# senior_board_rev1.net
KiCad netlist of a schematic drawn in Altium Designer
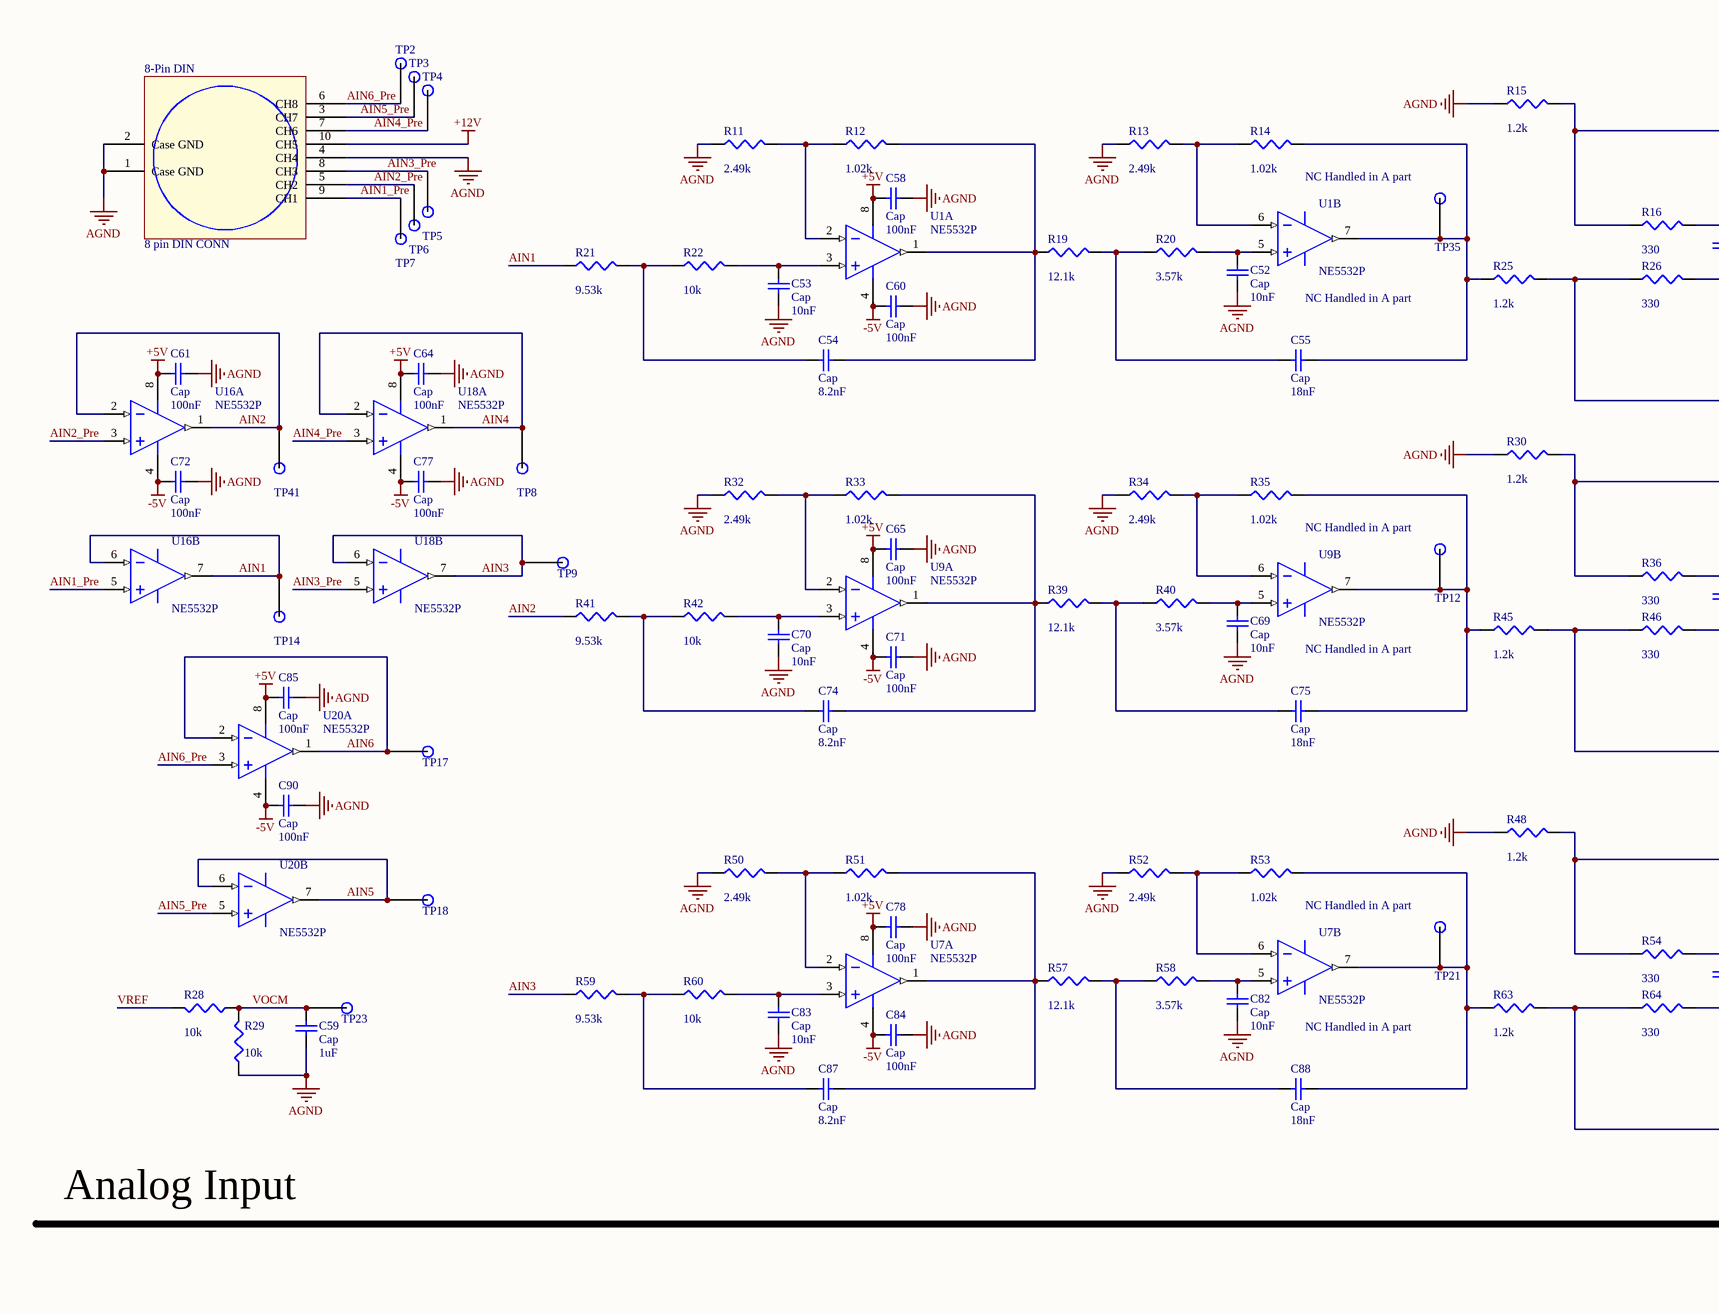
[diagram p0: senior_board_rev1.SchDoc, top left]
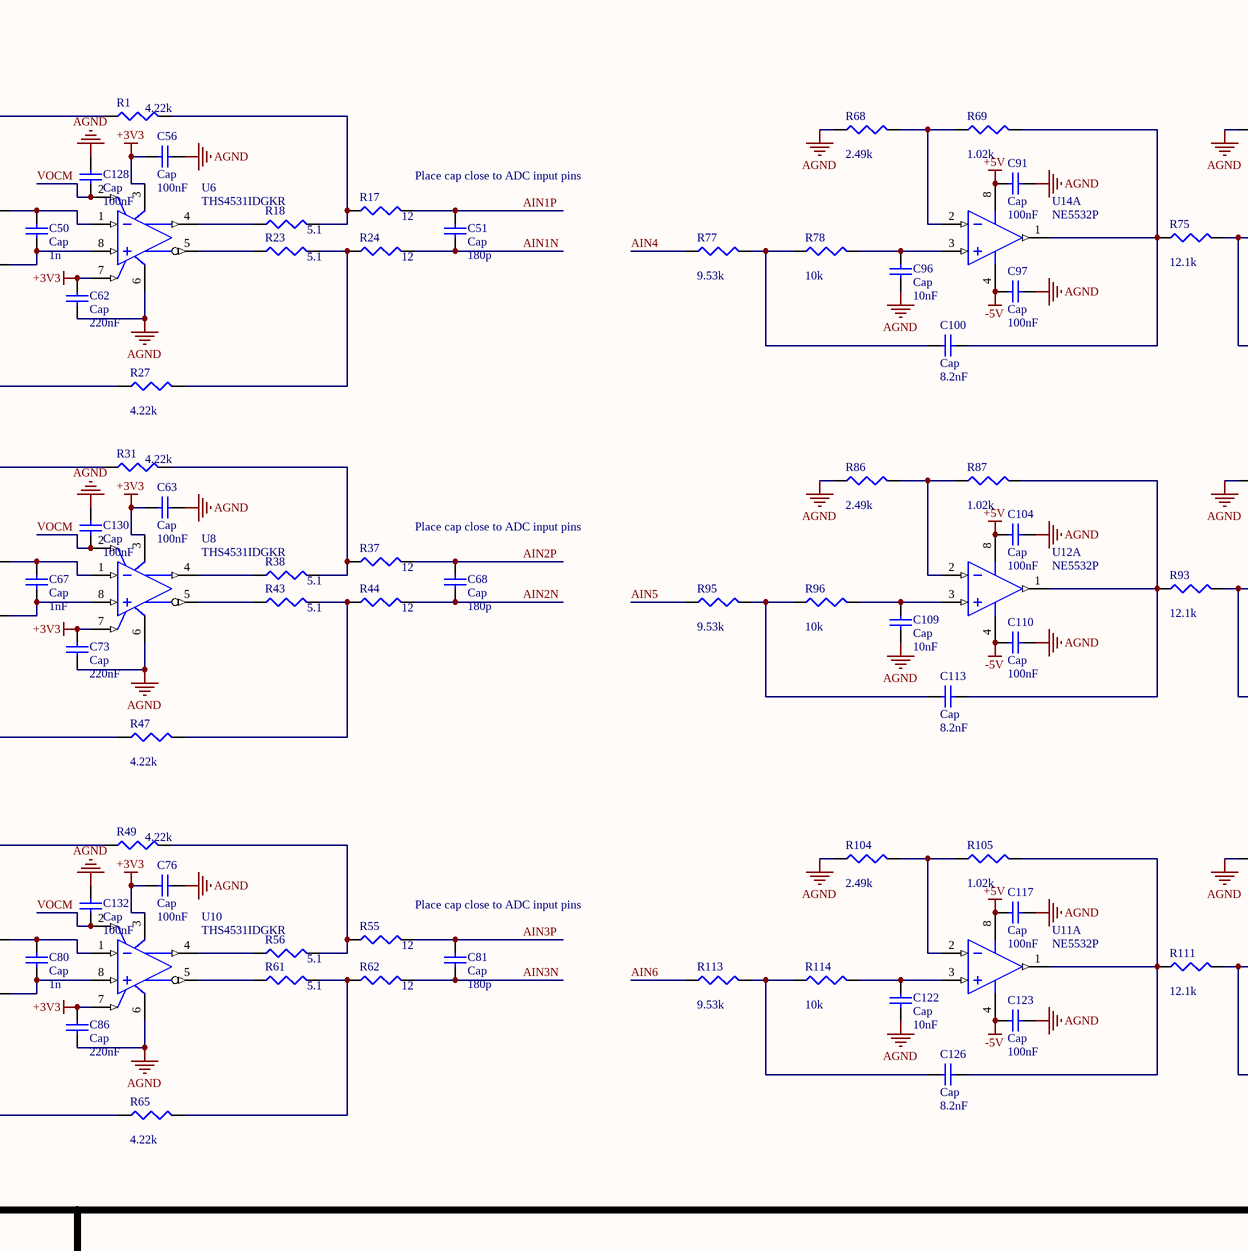
[diagram p1: senior_board_rev1.SchDoc, top middle]
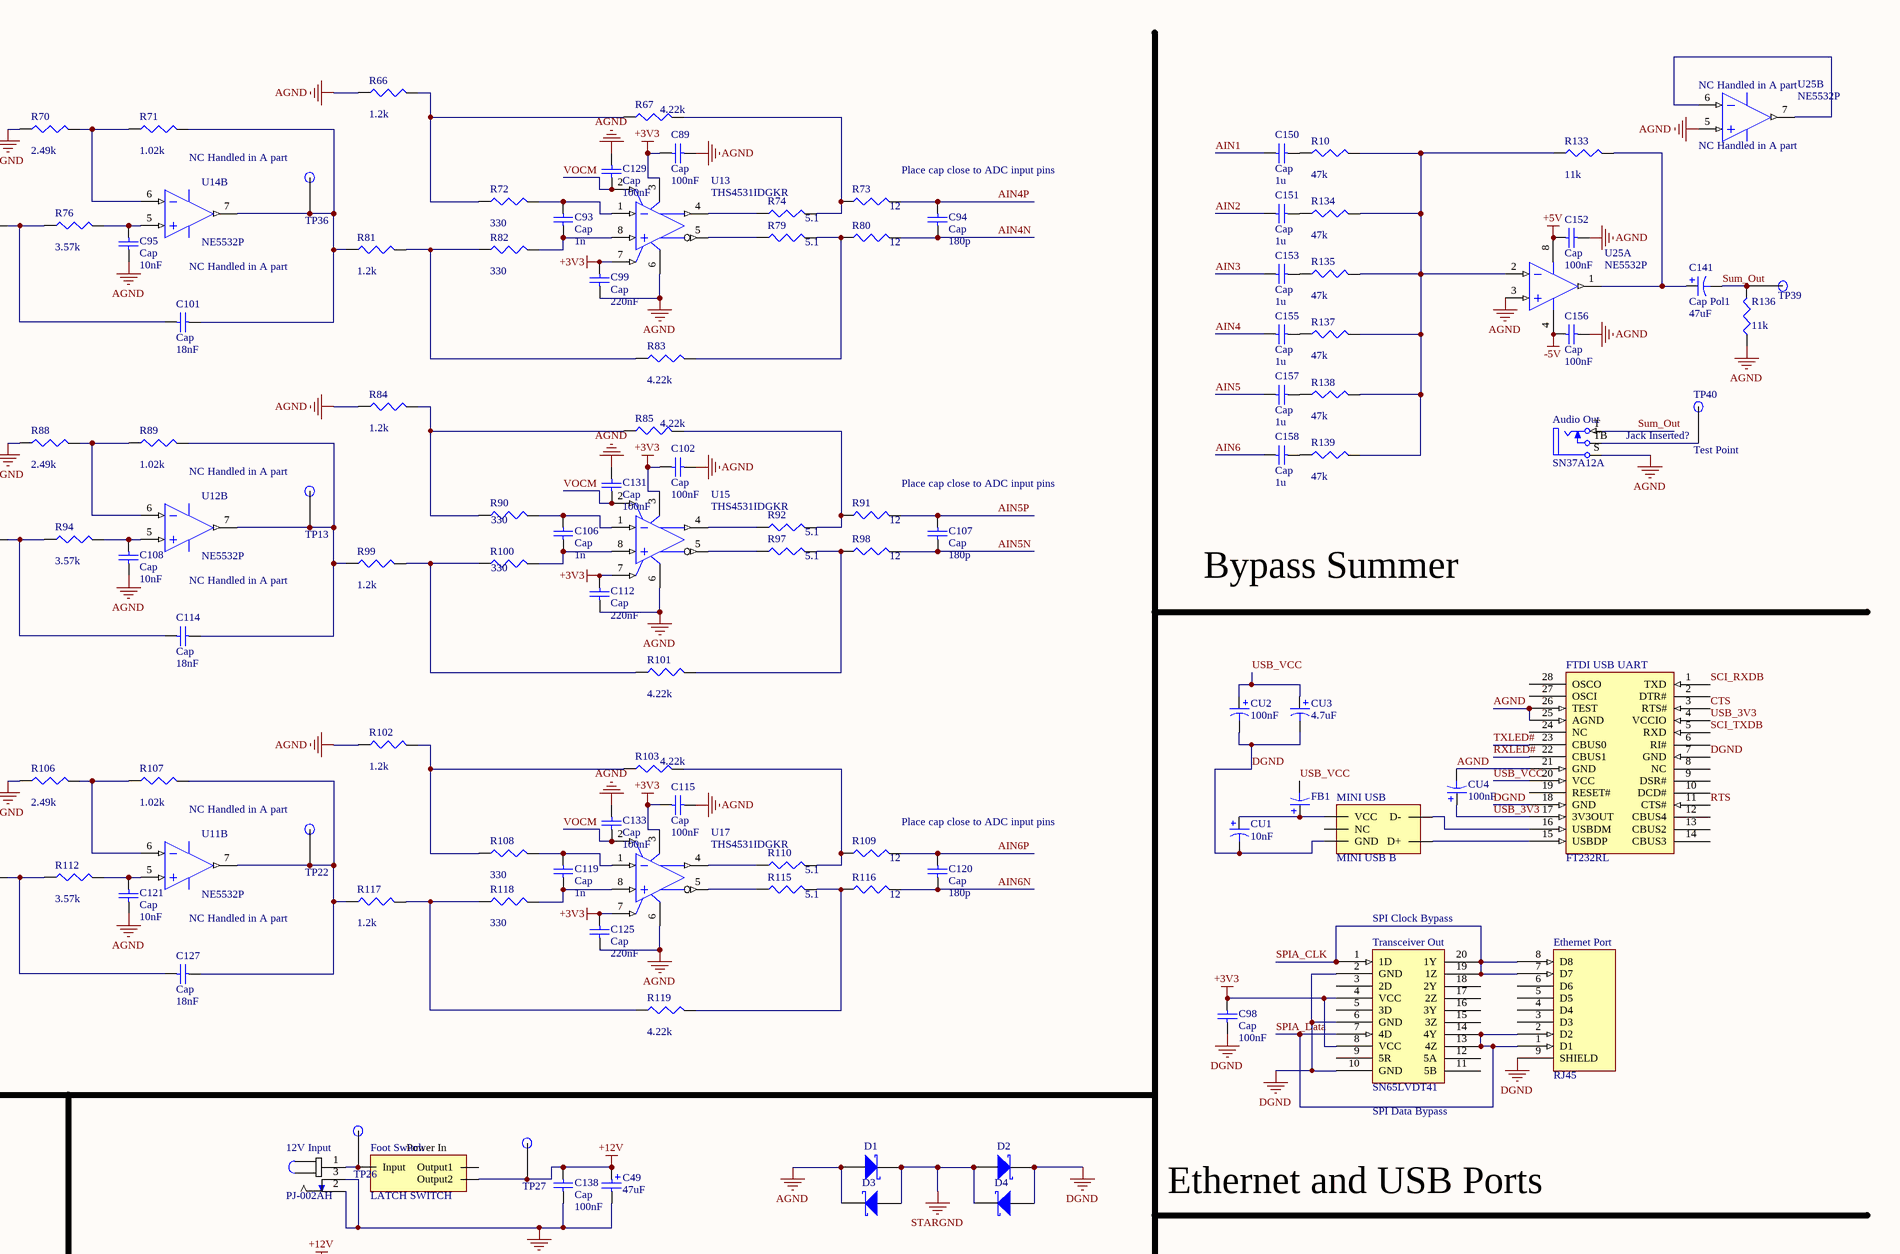
[diagram p2: senior_board_rev1.SchDoc, top right]
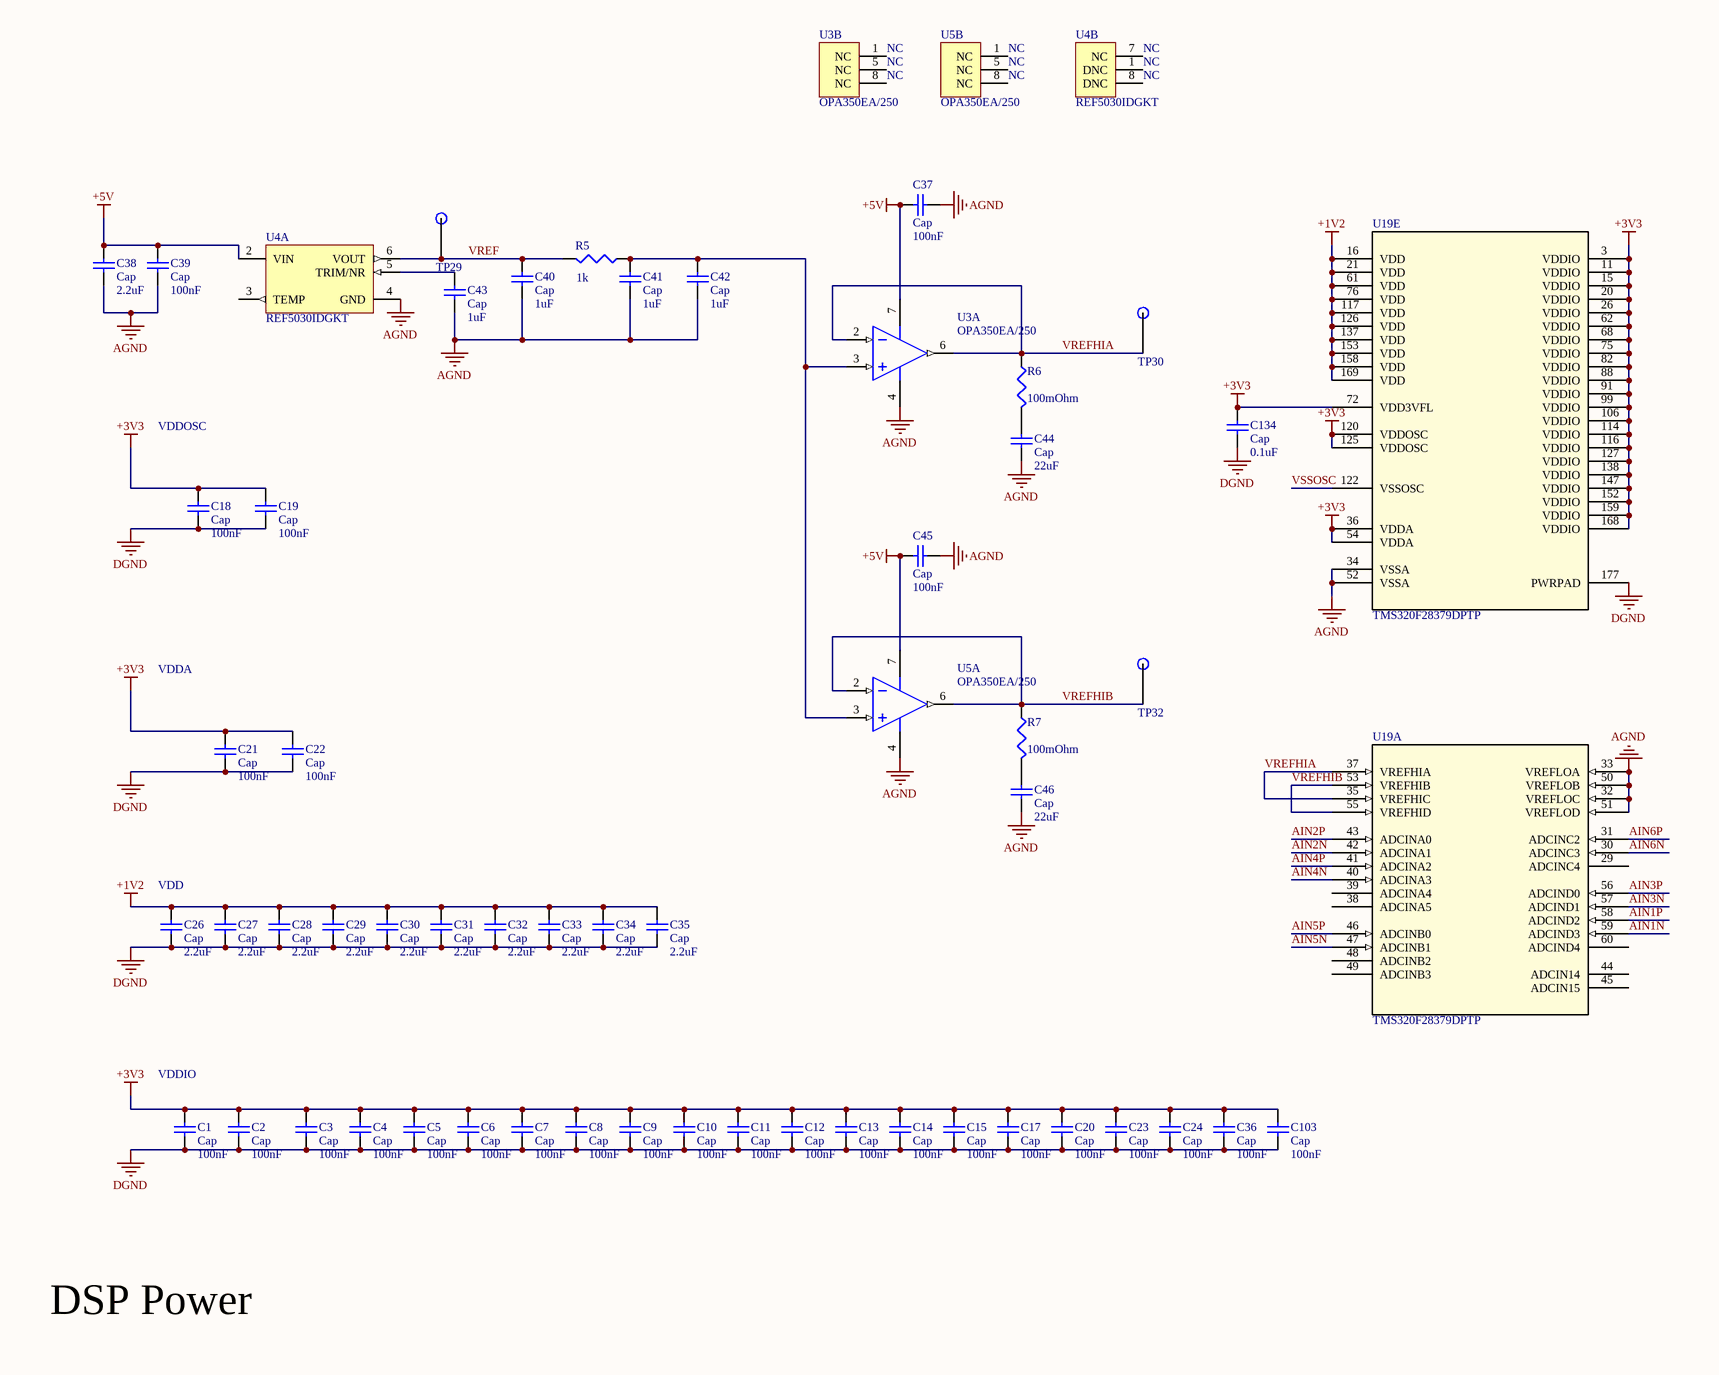
[diagram p3: senior_board_rev1.SchDoc, bottom left]
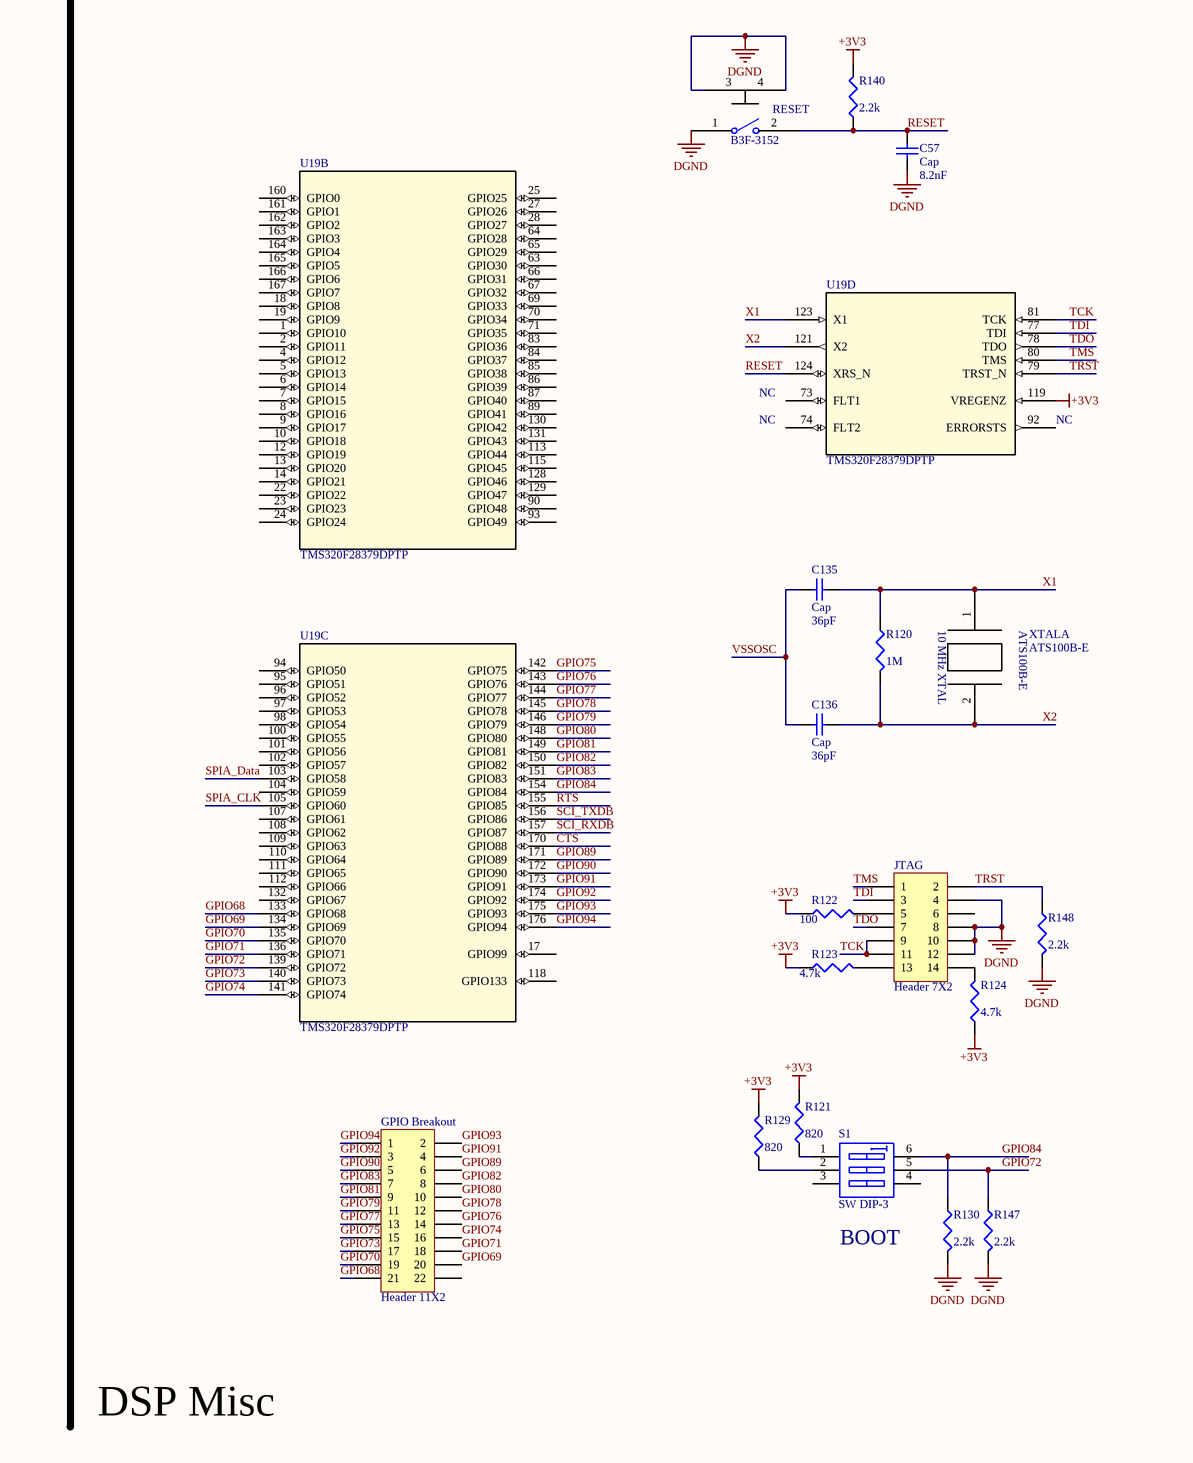
[diagram p4: senior_board_rev1.SchDoc, bottom middle]
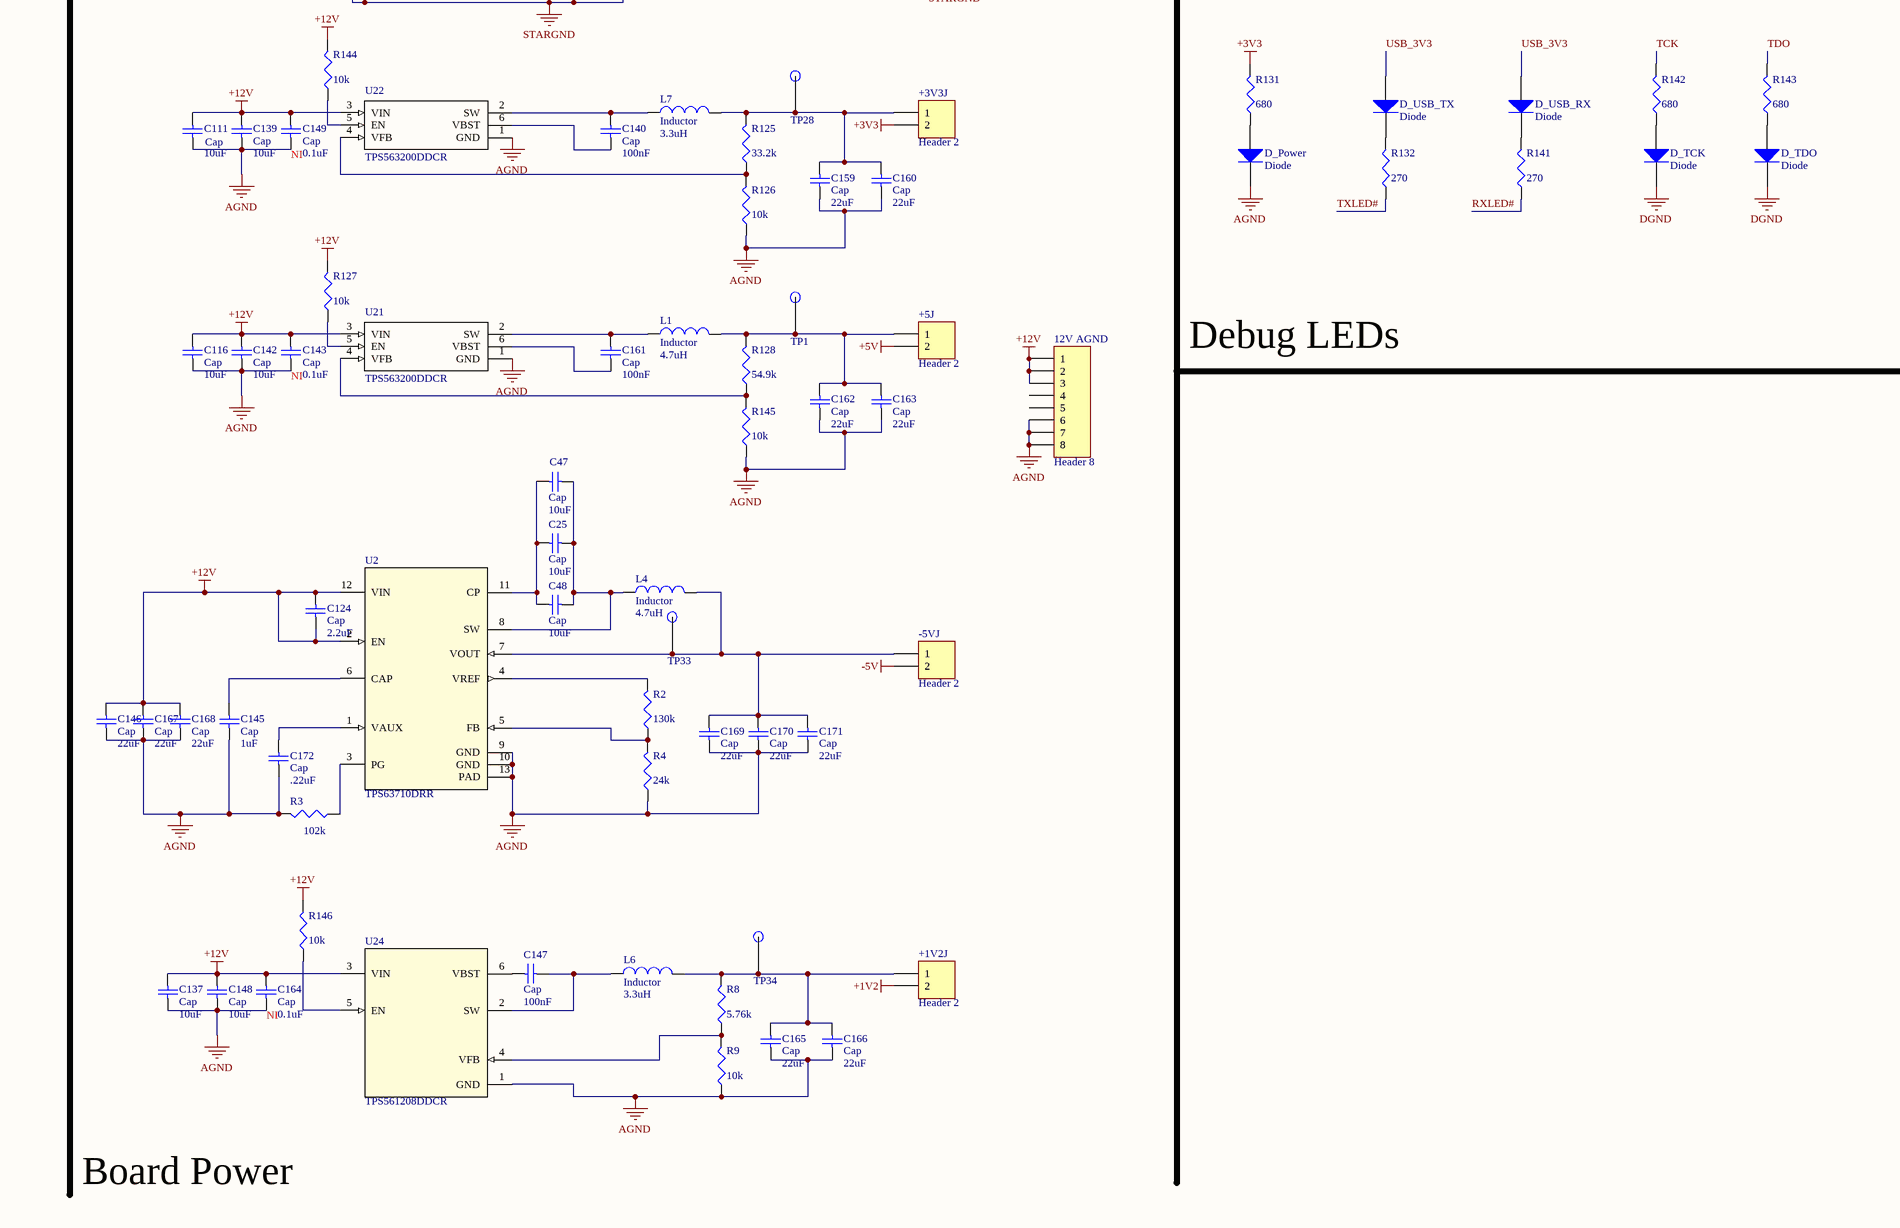
[diagram p5: senior_board_rev1.SchDoc, bottom right]

(export (version "E")
  (design (tool "Eeschema 10.0.6"))
  (components
    (comp (ref "+1V2J")
      (value "Header 2")
      (footprint "HDR1X2")
      (description "Header, 2-Pin")
      (fields (field (name "PUBLISHER") "Altium Limited"))
      (libsource (lib "Miscellaneous Connectors") (part "Header 2"))
    )
    (comp (ref "+3V3J")
      (value "Header 2")
      (footprint "HDR1X2")
      (description "Header, 2-Pin")
      (fields (field (name "PUBLISHER") "Altium Limited"))
      (libsource (lib "Miscellaneous Connectors") (part "Header 2"))
    )
    (comp (ref "+5J")
      (value "Header 2")
      (footprint "HDR1X2")
      (description "Header, 2-Pin")
      (fields (field (name "PUBLISHER") "Altium Limited"))
      (libsource (lib "Miscellaneous Connectors") (part "Header 2"))
    )
    (comp (ref "-5VJ")
      (value "Header 2")
      (footprint "HDR1X2")
      (description "Header, 2-Pin")
      (fields (field (name "PUBLISHER") "Altium Limited"))
      (libsource (lib "Miscellaneous Connectors") (part "Header 2"))
    )
    (comp (ref "8-Pin DIN")
      (value "8 pin DIN CONN")
      (footprint "8 Pin DIN Conn")
      (libsource (lib "Senior_SCH_Lib") (part "8 pin DIN CONN"))
    )
    (comp (ref "12V AGND")
      (value "Header 8")
      (footprint "HDR1X8")
      (description "Header, 8-Pin")
      (fields (field (name "PUBLISHER") "Altium Limited"))
      (libsource (lib "Miscellaneous Connectors") (part "Header 8"))
    )
    (comp (ref "12V Input")
      (value "PJ-002AH")
      (footprint "PJ-002AH")
      (libsource (lib "PJ-002AH") (part "PJ-002AH"))
    )
    (comp (ref "Audio Out")
      (value "SN37A12A")
      (footprint "SN37A12A")
      (libsource (lib "Senior_SCH_Lib") (part "SN37A12A"))
    )
    (comp (ref "C1")
      (value "Cap")
      (footprint "6-0805_N")
      (description "Capacitor")
      (fields (field (name "ALTIUM_VALUE") "100nF") (field (name "PUBLISHER") "Altium Limited"))
      (libsource (lib "Miscellaneous Devices") (part "Cap"))
    )
    (comp (ref "C2")
      (value "Cap")
      (footprint "6-0805_N")
      (description "Capacitor")
      (fields (field (name "ALTIUM_VALUE") "100nF") (field (name "PUBLISHER") "Altium Limited"))
      (libsource (lib "Miscellaneous Devices") (part "Cap"))
    )
    (comp (ref "C3")
      (value "Cap")
      (footprint "6-0805_N")
      (description "Capacitor")
      (fields (field (name "ALTIUM_VALUE") "100nF") (field (name "PUBLISHER") "Altium Limited"))
      (libsource (lib "Miscellaneous Devices") (part "Cap"))
    )
    (comp (ref "C4")
      (value "Cap")
      (footprint "6-0805_N")
      (description "Capacitor")
      (fields (field (name "ALTIUM_VALUE") "100nF") (field (name "PUBLISHER") "Altium Limited"))
      (libsource (lib "Miscellaneous Devices") (part "Cap"))
    )
    (comp (ref "C5")
      (value "Cap")
      (footprint "6-0805_N")
      (description "Capacitor")
      (fields (field (name "ALTIUM_VALUE") "100nF") (field (name "PUBLISHER") "Altium Limited"))
      (libsource (lib "Miscellaneous Devices") (part "Cap"))
    )
    (comp (ref "C6")
      (value "Cap")
      (footprint "6-0805_N")
      (description "Capacitor")
      (fields (field (name "ALTIUM_VALUE") "100nF") (field (name "PUBLISHER") "Altium Limited"))
      (libsource (lib "Miscellaneous Devices") (part "Cap"))
    )
    (comp (ref "C7")
      (value "Cap")
      (footprint "6-0805_N")
      (description "Capacitor")
      (fields (field (name "ALTIUM_VALUE") "100nF") (field (name "PUBLISHER") "Altium Limited"))
      (libsource (lib "Miscellaneous Devices") (part "Cap"))
    )
    (comp (ref "C8")
      (value "Cap")
      (footprint "6-0805_N")
      (description "Capacitor")
      (fields (field (name "ALTIUM_VALUE") "100nF") (field (name "PUBLISHER") "Altium Limited"))
      (libsource (lib "Miscellaneous Devices") (part "Cap"))
    )
    (comp (ref "C9")
      (value "Cap")
      (footprint "6-0805_N")
      (description "Capacitor")
      (fields (field (name "ALTIUM_VALUE") "100nF") (field (name "PUBLISHER") "Altium Limited"))
      (libsource (lib "Miscellaneous Devices") (part "Cap"))
    )
    (comp (ref "C10")
      (value "Cap")
      (footprint "6-0805_N")
      (description "Capacitor")
      (fields (field (name "ALTIUM_VALUE") "100nF") (field (name "PUBLISHER") "Altium Limited"))
      (libsource (lib "Miscellaneous Devices") (part "Cap"))
    )
    (comp (ref "C11")
      (value "Cap")
      (footprint "6-0805_N")
      (description "Capacitor")
      (fields (field (name "ALTIUM_VALUE") "100nF") (field (name "PUBLISHER") "Altium Limited"))
      (libsource (lib "Miscellaneous Devices") (part "Cap"))
    )
    (comp (ref "C12")
      (value "Cap")
      (footprint "6-0805_N")
      (description "Capacitor")
      (fields (field (name "ALTIUM_VALUE") "100nF") (field (name "PUBLISHER") "Altium Limited"))
      (libsource (lib "Miscellaneous Devices") (part "Cap"))
    )
    (comp (ref "C13")
      (value "Cap")
      (footprint "6-0805_N")
      (description "Capacitor")
      (fields (field (name "ALTIUM_VALUE") "100nF") (field (name "PUBLISHER") "Altium Limited"))
      (libsource (lib "Miscellaneous Devices") (part "Cap"))
    )
    (comp (ref "C14")
      (value "Cap")
      (footprint "6-0805_N")
      (description "Capacitor")
      (fields (field (name "ALTIUM_VALUE") "100nF") (field (name "PUBLISHER") "Altium Limited"))
      (libsource (lib "Miscellaneous Devices") (part "Cap"))
    )
    (comp (ref "C15")
      (value "Cap")
      (footprint "6-0805_N")
      (description "Capacitor")
      (fields (field (name "ALTIUM_VALUE") "100nF") (field (name "PUBLISHER") "Altium Limited"))
      (libsource (lib "Miscellaneous Devices") (part "Cap"))
    )
    (comp (ref "C17")
      (value "Cap")
      (footprint "6-0805_N")
      (description "Capacitor")
      (fields (field (name "ALTIUM_VALUE") "100nF") (field (name "PUBLISHER") "Altium Limited"))
      (libsource (lib "Miscellaneous Devices") (part "Cap"))
    )
    (comp (ref "C18")
      (value "Cap")
      (footprint "6-0805_N")
      (description "Capacitor")
      (fields (field (name "ALTIUM_VALUE") "100nF") (field (name "PUBLISHER") "Altium Limited"))
      (libsource (lib "Miscellaneous Devices") (part "Cap"))
    )
    (comp (ref "C19")
      (value "Cap")
      (footprint "6-0805_N")
      (description "Capacitor")
      (fields (field (name "ALTIUM_VALUE") "100nF") (field (name "PUBLISHER") "Altium Limited"))
      (libsource (lib "Miscellaneous Devices") (part "Cap"))
    )
    (comp (ref "C20")
      (value "Cap")
      (footprint "6-0805_N")
      (description "Capacitor")
      (fields (field (name "ALTIUM_VALUE") "100nF") (field (name "PUBLISHER") "Altium Limited"))
      (libsource (lib "Miscellaneous Devices") (part "Cap"))
    )
    (comp (ref "C21")
      (value "Cap")
      (footprint "6-0805_N")
      (description "Capacitor")
      (fields (field (name "ALTIUM_VALUE") "100nF") (field (name "PUBLISHER") "Altium Limited"))
      (libsource (lib "Miscellaneous Devices") (part "Cap"))
    )
    (comp (ref "C22")
      (value "Cap")
      (footprint "6-0805_N")
      (description "Capacitor")
      (fields (field (name "ALTIUM_VALUE") "100nF") (field (name "PUBLISHER") "Altium Limited"))
      (libsource (lib "Miscellaneous Devices") (part "Cap"))
    )
    (comp (ref "C23")
      (value "Cap")
      (footprint "6-0805_N")
      (description "Capacitor")
      (fields (field (name "ALTIUM_VALUE") "100nF") (field (name "PUBLISHER") "Altium Limited"))
      (libsource (lib "Miscellaneous Devices") (part "Cap"))
    )
    (comp (ref "C24")
      (value "Cap")
      (footprint "6-0805_N")
      (description "Capacitor")
      (fields (field (name "ALTIUM_VALUE") "100nF") (field (name "PUBLISHER") "Altium Limited"))
      (libsource (lib "Miscellaneous Devices") (part "Cap"))
    )
    (comp (ref "C25")
      (value "Cap")
      (footprint "6-0805_N")
      (description "Capacitor")
      (fields (field (name "ALTIUM_VALUE") "10uF") (field (name "PUBLISHER") "Altium Limited"))
      (libsource (lib "Miscellaneous Devices") (part "Cap"))
    )
    (comp (ref "C26")
      (value "Cap")
      (footprint "6-0805_N")
      (description "Capacitor")
      (fields (field (name "ALTIUM_VALUE") "2.2uF") (field (name "PUBLISHER") "Altium Limited"))
      (libsource (lib "Miscellaneous Devices") (part "Cap"))
    )
    (comp (ref "C27")
      (value "Cap")
      (footprint "6-0805_N")
      (description "Capacitor")
      (fields (field (name "ALTIUM_VALUE") "2.2uF") (field (name "PUBLISHER") "Altium Limited"))
      (libsource (lib "Miscellaneous Devices") (part "Cap"))
    )
    (comp (ref "C28")
      (value "Cap")
      (footprint "6-0805_N")
      (description "Capacitor")
      (fields (field (name "ALTIUM_VALUE") "2.2uF") (field (name "PUBLISHER") "Altium Limited"))
      (libsource (lib "Miscellaneous Devices") (part "Cap"))
    )
    (comp (ref "C29")
      (value "Cap")
      (footprint "6-0805_N")
      (description "Capacitor")
      (fields (field (name "ALTIUM_VALUE") "2.2uF") (field (name "PUBLISHER") "Altium Limited"))
      (libsource (lib "Miscellaneous Devices") (part "Cap"))
    )
    (comp (ref "C30")
      (value "Cap")
      (footprint "6-0805_N")
      (description "Capacitor")
      (fields (field (name "ALTIUM_VALUE") "2.2uF") (field (name "PUBLISHER") "Altium Limited"))
      (libsource (lib "Miscellaneous Devices") (part "Cap"))
    )
    (comp (ref "C31")
      (value "Cap")
      (footprint "6-0805_N")
      (description "Capacitor")
      (fields (field (name "ALTIUM_VALUE") "2.2uF") (field (name "PUBLISHER") "Altium Limited"))
      (libsource (lib "Miscellaneous Devices") (part "Cap"))
    )
    (comp (ref "C32")
      (value "Cap")
      (footprint "6-0805_N")
      (description "Capacitor")
      (fields (field (name "ALTIUM_VALUE") "2.2uF") (field (name "PUBLISHER") "Altium Limited"))
      (libsource (lib "Miscellaneous Devices") (part "Cap"))
    )
    (comp (ref "C33")
      (value "Cap")
      (footprint "6-0805_N")
      (description "Capacitor")
      (fields (field (name "ALTIUM_VALUE") "2.2uF") (field (name "PUBLISHER") "Altium Limited"))
      (libsource (lib "Miscellaneous Devices") (part "Cap"))
    )
    (comp (ref "C34")
      (value "Cap")
      (footprint "6-0805_N")
      (description "Capacitor")
      (fields (field (name "ALTIUM_VALUE") "2.2uF") (field (name "PUBLISHER") "Altium Limited"))
      (libsource (lib "Miscellaneous Devices") (part "Cap"))
    )
    (comp (ref "C35")
      (value "Cap")
      (footprint "6-0805_N")
      (description "Capacitor")
      (fields (field (name "ALTIUM_VALUE") "2.2uF") (field (name "PUBLISHER") "Altium Limited"))
      (libsource (lib "Miscellaneous Devices") (part "Cap"))
    )
    (comp (ref "C36")
      (value "Cap")
      (footprint "6-0805_N")
      (description "Capacitor")
      (fields (field (name "ALTIUM_VALUE") "100nF") (field (name "PUBLISHER") "Altium Limited"))
      (libsource (lib "Miscellaneous Devices") (part "Cap"))
    )
    (comp (ref "C37")
      (value "Cap")
      (footprint "6-0805_N")
      (description "Capacitor")
      (fields (field (name "ALTIUM_VALUE") "100nF") (field (name "PUBLISHER") "Altium Limited"))
      (libsource (lib "Miscellaneous Devices") (part "Cap"))
    )
    (comp (ref "C38")
      (value "Cap")
      (footprint "6-0805_N")
      (description "Capacitor")
      (fields (field (name "ALTIUM_VALUE") "2.2uF") (field (name "PUBLISHER") "Altium Limited"))
      (libsource (lib "Miscellaneous Devices") (part "Cap"))
    )
    (comp (ref "C39")
      (value "Cap")
      (footprint "6-0805_N")
      (description "Capacitor")
      (fields (field (name "ALTIUM_VALUE") "100nF") (field (name "PUBLISHER") "Altium Limited"))
      (libsource (lib "Miscellaneous Devices") (part "Cap"))
    )
    (comp (ref "C40")
      (value "Cap")
      (footprint "6-0805_N")
      (description "Capacitor")
      (fields (field (name "ALTIUM_VALUE") "1uF") (field (name "PUBLISHER") "Altium Limited"))
      (libsource (lib "Miscellaneous Devices") (part "Cap"))
    )
    (comp (ref "C41")
      (value "Cap")
      (footprint "6-0805_N")
      (description "Capacitor")
      (fields (field (name "ALTIUM_VALUE") "1uF") (field (name "PUBLISHER") "Altium Limited"))
      (libsource (lib "Miscellaneous Devices") (part "Cap"))
    )
    (comp (ref "C42")
      (value "Cap")
      (footprint "6-0805_N")
      (description "Capacitor")
      (fields (field (name "ALTIUM_VALUE") "1uF") (field (name "PUBLISHER") "Altium Limited"))
      (libsource (lib "Miscellaneous Devices") (part "Cap"))
    )
    (comp (ref "C43")
      (value "Cap")
      (footprint "6-0805_N")
      (description "Capacitor")
      (fields (field (name "ALTIUM_VALUE") "1uF") (field (name "PUBLISHER") "Altium Limited"))
      (libsource (lib "Miscellaneous Devices") (part "Cap"))
    )
    (comp (ref "C44")
      (value "Cap")
      (footprint "6-0805_N")
      (description "Capacitor")
      (fields (field (name "ALTIUM_VALUE") "22uF") (field (name "PUBLISHER") "Altium Limited"))
      (libsource (lib "Miscellaneous Devices") (part "Cap"))
    )
    (comp (ref "C45")
      (value "Cap")
      (footprint "6-0805_N")
      (description "Capacitor")
      (fields (field (name "ALTIUM_VALUE") "100nF") (field (name "PUBLISHER") "Altium Limited"))
      (libsource (lib "Miscellaneous Devices") (part "Cap"))
    )
    (comp (ref "C46")
      (value "Cap")
      (footprint "6-0805_N")
      (description "Capacitor")
      (fields (field (name "ALTIUM_VALUE") "22uF") (field (name "PUBLISHER") "Altium Limited"))
      (libsource (lib "Miscellaneous Devices") (part "Cap"))
    )
    (comp (ref "C47")
      (value "Cap")
      (footprint "6-0805_N")
      (description "Capacitor")
      (fields (field (name "ALTIUM_VALUE") "10uF") (field (name "PUBLISHER") "Altium Limited"))
      (libsource (lib "Miscellaneous Devices") (part "Cap"))
    )
    (comp (ref "C48")
      (value "Cap")
      (footprint "6-0805_N")
      (description "Capacitor")
      (fields (field (name "ALTIUM_VALUE") "10uF") (field (name "PUBLISHER") "Altium Limited"))
      (libsource (lib "Miscellaneous Devices") (part "Cap"))
    )
    (comp (ref "C49")
      (value "47uF")
      (footprint "UUQ1C470MCL1GB")
      (description "UUQ1C470MCL1GB")
      (libsource (lib "Senior_SCH_Lib") (part "UUQ1C470MCL1GB"))
    )
    (comp (ref "C50")
      (value "Cap")
      (footprint "6-0805_N")
      (description "Capacitor")
      (fields (field (name "ALTIUM_VALUE") "1n") (field (name "PUBLISHER") "Altium Limited"))
      (libsource (lib "Miscellaneous Devices") (part "Cap"))
    )
    (comp (ref "C51")
      (value "Cap")
      (footprint "6-0805_N")
      (description "Capacitor")
      (fields (field (name "ALTIUM_VALUE") "180p") (field (name "PUBLISHER") "Altium Limited"))
      (libsource (lib "Miscellaneous Devices") (part "Cap"))
    )
    (comp (ref "C52")
      (value "Cap")
      (footprint "6-0805_N")
      (description "Capacitor")
      (fields (field (name "ALTIUM_VALUE") "10nF") (field (name "PUBLISHER") "Altium Limited"))
      (libsource (lib "Miscellaneous Devices") (part "Cap"))
    )
    (comp (ref "C53")
      (value "Cap")
      (footprint "6-0805_N")
      (description "Capacitor")
      (fields (field (name "ALTIUM_VALUE") "10nF") (field (name "PUBLISHER") "Altium Limited"))
      (libsource (lib "Miscellaneous Devices") (part "Cap"))
    )
    (comp (ref "C54")
      (value "Cap")
      (footprint "6-0805_N")
      (description "Capacitor")
      (fields (field (name "ALTIUM_VALUE") "8.2nF") (field (name "PUBLISHER") "Altium Limited"))
      (libsource (lib "Miscellaneous Devices") (part "Cap"))
    )
    (comp (ref "C55")
      (value "Cap")
      (footprint "6-0805_N")
      (description "Capacitor")
      (fields (field (name "ALTIUM_VALUE") "18nF") (field (name "PUBLISHER") "Altium Limited"))
      (libsource (lib "Miscellaneous Devices") (part "Cap"))
    )
    (comp (ref "C56")
      (value "Cap")
      (footprint "6-0805_N")
      (description "Capacitor")
      (fields (field (name "ALTIUM_VALUE") "100nF") (field (name "PUBLISHER") "Altium Limited"))
      (libsource (lib "Miscellaneous Devices") (part "Cap"))
    )
    (comp (ref "C57")
      (value "Cap")
      (footprint "6-0805_N")
      (description "Capacitor")
      (fields (field (name "ALTIUM_VALUE") "8.2nF") (field (name "PUBLISHER") "Altium Limited"))
      (libsource (lib "Miscellaneous Devices") (part "Cap"))
    )
    (comp (ref "C58")
      (value "Cap")
      (footprint "6-0805_N")
      (description "Capacitor")
      (fields (field (name "ALTIUM_VALUE") "100nF") (field (name "PUBLISHER") "Altium Limited"))
      (libsource (lib "Miscellaneous Devices") (part "Cap"))
    )
    (comp (ref "C59")
      (value "Cap")
      (footprint "6-0805_N")
      (description "Capacitor")
      (fields (field (name "ALTIUM_VALUE") "1uF") (field (name "PUBLISHER") "Altium Limited"))
      (libsource (lib "Miscellaneous Devices") (part "Cap"))
    )
    (comp (ref "C60")
      (value "Cap")
      (footprint "6-0805_N")
      (description "Capacitor")
      (fields (field (name "ALTIUM_VALUE") "100nF") (field (name "PUBLISHER") "Altium Limited"))
      (libsource (lib "Miscellaneous Devices") (part "Cap"))
    )
    (comp (ref "C61")
      (value "Cap")
      (footprint "6-0805_N")
      (description "Capacitor")
      (fields (field (name "ALTIUM_VALUE") "100nF") (field (name "PUBLISHER") "Altium Limited"))
      (libsource (lib "Miscellaneous Devices") (part "Cap"))
    )
    (comp (ref "C62")
      (value "Cap")
      (footprint "6-0805_N")
      (description "Capacitor")
      (fields (field (name "ALTIUM_VALUE") "220nF") (field (name "PUBLISHER") "Altium Limited"))
      (libsource (lib "Miscellaneous Devices") (part "Cap"))
    )
    (comp (ref "C63")
      (value "Cap")
      (footprint "6-0805_N")
      (description "Capacitor")
      (fields (field (name "ALTIUM_VALUE") "100nF") (field (name "PUBLISHER") "Altium Limited"))
      (libsource (lib "Miscellaneous Devices") (part "Cap"))
    )
    (comp (ref "C64")
      (value "Cap")
      (footprint "6-0805_N")
      (description "Capacitor")
      (fields (field (name "ALTIUM_VALUE") "100nF") (field (name "PUBLISHER") "Altium Limited"))
      (libsource (lib "Miscellaneous Devices") (part "Cap"))
    )
    (comp (ref "C65")
      (value "Cap")
      (footprint "6-0805_N")
      (description "Capacitor")
      (fields (field (name "ALTIUM_VALUE") "100nF") (field (name "PUBLISHER") "Altium Limited"))
      (libsource (lib "Miscellaneous Devices") (part "Cap"))
    )
    (comp (ref "C67")
      (value "Cap")
      (footprint "6-0805_N")
      (description "Capacitor")
      (fields (field (name "ALTIUM_VALUE") "1nF") (field (name "PUBLISHER") "Altium Limited"))
      (libsource (lib "Miscellaneous Devices") (part "Cap"))
    )
    (comp (ref "C68")
      (value "Cap")
      (footprint "6-0805_N")
      (description "Capacitor")
      (fields (field (name "ALTIUM_VALUE") "180p") (field (name "PUBLISHER") "Altium Limited"))
      (libsource (lib "Miscellaneous Devices") (part "Cap"))
    )
    (comp (ref "C69")
      (value "Cap")
      (footprint "6-0805_N")
      (description "Capacitor")
      (fields (field (name "ALTIUM_VALUE") "10nF") (field (name "PUBLISHER") "Altium Limited"))
      (libsource (lib "Miscellaneous Devices") (part "Cap"))
    )
    (comp (ref "C70")
      (value "Cap")
      (footprint "6-0805_N")
      (description "Capacitor")
      (fields (field (name "ALTIUM_VALUE") "10nF") (field (name "PUBLISHER") "Altium Limited"))
      (libsource (lib "Miscellaneous Devices") (part "Cap"))
    )
    (comp (ref "C71")
      (value "Cap")
      (footprint "6-0805_N")
      (description "Capacitor")
      (fields (field (name "ALTIUM_VALUE") "100nF") (field (name "PUBLISHER") "Altium Limited"))
      (libsource (lib "Miscellaneous Devices") (part "Cap"))
    )
    (comp (ref "C72")
      (value "Cap")
      (footprint "6-0805_N")
      (description "Capacitor")
      (fields (field (name "ALTIUM_VALUE") "100nF") (field (name "PUBLISHER") "Altium Limited"))
      (libsource (lib "Miscellaneous Devices") (part "Cap"))
    )
    (comp (ref "C73")
      (value "Cap")
      (footprint "6-0805_N")
      (description "Capacitor")
      (fields (field (name "ALTIUM_VALUE") "220nF") (field (name "PUBLISHER") "Altium Limited"))
      (libsource (lib "Miscellaneous Devices") (part "Cap"))
    )
    (comp (ref "C74")
      (value "Cap")
      (footprint "6-0805_N")
      (description "Capacitor")
      (fields (field (name "ALTIUM_VALUE") "8.2nF") (field (name "PUBLISHER") "Altium Limited"))
      (libsource (lib "Miscellaneous Devices") (part "Cap"))
    )
    (comp (ref "C75")
      (value "Cap")
      (footprint "6-0805_N")
      (description "Capacitor")
      (fields (field (name "ALTIUM_VALUE") "18nF") (field (name "PUBLISHER") "Altium Limited"))
      (libsource (lib "Miscellaneous Devices") (part "Cap"))
    )
    (comp (ref "C76")
      (value "Cap")
      (footprint "6-0805_N")
      (description "Capacitor")
      (fields (field (name "ALTIUM_VALUE") "100nF") (field (name "PUBLISHER") "Altium Limited"))
      (libsource (lib "Miscellaneous Devices") (part "Cap"))
    )
    (comp (ref "C77")
      (value "Cap")
      (footprint "6-0805_N")
      (description "Capacitor")
      (fields (field (name "ALTIUM_VALUE") "100nF") (field (name "PUBLISHER") "Altium Limited"))
      (libsource (lib "Miscellaneous Devices") (part "Cap"))
    )
    (comp (ref "C78")
      (value "Cap")
      (footprint "6-0805_N")
      (description "Capacitor")
      (fields (field (name "ALTIUM_VALUE") "100nF") (field (name "PUBLISHER") "Altium Limited"))
      (libsource (lib "Miscellaneous Devices") (part "Cap"))
    )
    (comp (ref "C80")
      (value "Cap")
      (footprint "6-0805_N")
      (description "Capacitor")
      (fields (field (name "ALTIUM_VALUE") "1n") (field (name "PUBLISHER") "Altium Limited"))
      (libsource (lib "Miscellaneous Devices") (part "Cap"))
    )
    (comp (ref "C81")
      (value "Cap")
      (footprint "6-0805_N")
      (description "Capacitor")
      (fields (field (name "ALTIUM_VALUE") "180p") (field (name "PUBLISHER") "Altium Limited"))
      (libsource (lib "Miscellaneous Devices") (part "Cap"))
    )
    (comp (ref "C82")
      (value "Cap")
      (footprint "6-0805_N")
      (description "Capacitor")
      (fields (field (name "ALTIUM_VALUE") "10nF") (field (name "PUBLISHER") "Altium Limited"))
      (libsource (lib "Miscellaneous Devices") (part "Cap"))
    )
    (comp (ref "C83")
      (value "Cap")
      (footprint "6-0805_N")
      (description "Capacitor")
      (fields (field (name "ALTIUM_VALUE") "10nF") (field (name "PUBLISHER") "Altium Limited"))
      (libsource (lib "Miscellaneous Devices") (part "Cap"))
    )
    (comp (ref "C84")
      (value "Cap")
      (footprint "6-0805_N")
      (description "Capacitor")
      (fields (field (name "ALTIUM_VALUE") "100nF") (field (name "PUBLISHER") "Altium Limited"))
      (libsource (lib "Miscellaneous Devices") (part "Cap"))
    )
    (comp (ref "C85")
      (value "Cap")
      (footprint "6-0805_N")
      (description "Capacitor")
      (fields (field (name "ALTIUM_VALUE") "100nF") (field (name "PUBLISHER") "Altium Limited"))
      (libsource (lib "Miscellaneous Devices") (part "Cap"))
    )
    (comp (ref "C86")
      (value "Cap")
      (footprint "6-0805_N")
      (description "Capacitor")
      (fields (field (name "ALTIUM_VALUE") "220nF") (field (name "PUBLISHER") "Altium Limited"))
      (libsource (lib "Miscellaneous Devices") (part "Cap"))
    )
    (comp (ref "C87")
      (value "Cap")
      (footprint "6-0805_N")
      (description "Capacitor")
      (fields (field (name "ALTIUM_VALUE") "8.2nF") (field (name "PUBLISHER") "Altium Limited"))
      (libsource (lib "Miscellaneous Devices") (part "Cap"))
    )
    (comp (ref "C88")
      (value "Cap")
      (footprint "6-0805_N")
      (description "Capacitor")
      (fields (field (name "ALTIUM_VALUE") "18nF") (field (name "PUBLISHER") "Altium Limited"))
      (libsource (lib "Miscellaneous Devices") (part "Cap"))
    )
    (comp (ref "C89")
      (value "Cap")
      (footprint "6-0805_N")
      (description "Capacitor")
      (fields (field (name "ALTIUM_VALUE") "100nF") (field (name "PUBLISHER") "Altium Limited"))
      (libsource (lib "Miscellaneous Devices") (part "Cap"))
    )
    (comp (ref "C90")
      (value "Cap")
      (footprint "6-0805_N")
      (description "Capacitor")
      (fields (field (name "ALTIUM_VALUE") "100nF") (field (name "PUBLISHER") "Altium Limited"))
      (libsource (lib "Miscellaneous Devices") (part "Cap"))
    )
    (comp (ref "C91")
      (value "Cap")
      (footprint "6-0805_N")
      (description "Capacitor")
      (fields (field (name "ALTIUM_VALUE") "100nF") (field (name "PUBLISHER") "Altium Limited"))
      (libsource (lib "Miscellaneous Devices") (part "Cap"))
    )
    (comp (ref "C93")
      (value "Cap")
      (footprint "6-0805_N")
      (description "Capacitor")
      (fields (field (name "ALTIUM_VALUE") "1n") (field (name "PUBLISHER") "Altium Limited"))
      (libsource (lib "Miscellaneous Devices") (part "Cap"))
    )
    (comp (ref "C94")
      (value "Cap")
      (footprint "6-0805_N")
      (description "Capacitor")
      (fields (field (name "ALTIUM_VALUE") "180p") (field (name "PUBLISHER") "Altium Limited"))
      (libsource (lib "Miscellaneous Devices") (part "Cap"))
    )
    (comp (ref "C95")
      (value "Cap")
      (footprint "6-0805_N")
      (description "Capacitor")
      (fields (field (name "ALTIUM_VALUE") "10nF") (field (name "PUBLISHER") "Altium Limited"))
      (libsource (lib "Miscellaneous Devices") (part "Cap"))
    )
    (comp (ref "C96")
      (value "Cap")
      (footprint "6-0805_N")
      (description "Capacitor")
      (fields (field (name "ALTIUM_VALUE") "10nF") (field (name "PUBLISHER") "Altium Limited"))
      (libsource (lib "Miscellaneous Devices") (part "Cap"))
    )
    (comp (ref "C97")
      (value "Cap")
      (footprint "6-0805_N")
      (description "Capacitor")
      (fields (field (name "ALTIUM_VALUE") "100nF") (field (name "PUBLISHER") "Altium Limited"))
      (libsource (lib "Miscellaneous Devices") (part "Cap"))
    )
    (comp (ref "C98")
      (value "Cap")
      (footprint "6-0805_N")
      (description "Capacitor")
      (fields (field (name "ALTIUM_VALUE") "100nF") (field (name "PUBLISHER") "Altium Limited"))
      (libsource (lib "Miscellaneous Devices") (part "Cap"))
    )
    (comp (ref "C99")
      (value "Cap")
      (footprint "6-0805_N")
      (description "Capacitor")
      (fields (field (name "ALTIUM_VALUE") "220nF") (field (name "PUBLISHER") "Altium Limited"))
      (libsource (lib "Miscellaneous Devices") (part "Cap"))
    )
    (comp (ref "C100")
      (value "Cap")
      (footprint "6-0805_N")
      (description "Capacitor")
      (fields (field (name "ALTIUM_VALUE") "8.2nF") (field (name "PUBLISHER") "Altium Limited"))
      (libsource (lib "Miscellaneous Devices") (part "Cap"))
    )
    (comp (ref "C101")
      (value "Cap")
      (footprint "6-0805_N")
      (description "Capacitor")
      (fields (field (name "ALTIUM_VALUE") "18nF") (field (name "PUBLISHER") "Altium Limited"))
      (libsource (lib "Miscellaneous Devices") (part "Cap"))
    )
    (comp (ref "C102")
      (value "Cap")
      (footprint "6-0805_N")
      (description "Capacitor")
      (fields (field (name "ALTIUM_VALUE") "100nF") (field (name "PUBLISHER") "Altium Limited"))
      (libsource (lib "Miscellaneous Devices") (part "Cap"))
    )
    (comp (ref "C103")
      (value "Cap")
      (footprint "6-0805_N")
      (description "Capacitor")
      (fields (field (name "ALTIUM_VALUE") "100nF") (field (name "PUBLISHER") "Altium Limited"))
      (libsource (lib "Miscellaneous Devices") (part "Cap"))
    )
    (comp (ref "C104")
      (value "Cap")
      (footprint "6-0805_N")
      (description "Capacitor")
      (fields (field (name "ALTIUM_VALUE") "100nF") (field (name "PUBLISHER") "Altium Limited"))
      (libsource (lib "Miscellaneous Devices") (part "Cap"))
    )
    (comp (ref "C106")
      (value "Cap")
      (footprint "6-0805_N")
      (description "Capacitor")
      (fields (field (name "ALTIUM_VALUE") "1n") (field (name "PUBLISHER") "Altium Limited"))
      (libsource (lib "Miscellaneous Devices") (part "Cap"))
    )
    (comp (ref "C107")
      (value "Cap")
      (footprint "6-0805_N")
      (description "Capacitor")
      (fields (field (name "ALTIUM_VALUE") "180p") (field (name "PUBLISHER") "Altium Limited"))
      (libsource (lib "Miscellaneous Devices") (part "Cap"))
    )
    (comp (ref "C108")
      (value "Cap")
      (footprint "6-0805_N")
      (description "Capacitor")
      (fields (field (name "ALTIUM_VALUE") "10nF") (field (name "PUBLISHER") "Altium Limited"))
      (libsource (lib "Miscellaneous Devices") (part "Cap"))
    )
    (comp (ref "C109")
      (value "Cap")
      (footprint "6-0805_N")
      (description "Capacitor")
      (fields (field (name "ALTIUM_VALUE") "10nF") (field (name "PUBLISHER") "Altium Limited"))
      (libsource (lib "Miscellaneous Devices") (part "Cap"))
    )
    (comp (ref "C110")
      (value "Cap")
      (footprint "6-0805_N")
      (description "Capacitor")
      (fields (field (name "ALTIUM_VALUE") "100nF") (field (name "PUBLISHER") "Altium Limited"))
      (libsource (lib "Miscellaneous Devices") (part "Cap"))
    )
    (comp (ref "C111")
      (value "Cap")
      (footprint "6-0805_N")
      (description "Capacitor")
      (fields (field (name "ALTIUM_VALUE") "10uF") (field (name "PUBLISHER") "Altium Limited"))
      (libsource (lib "Miscellaneous Devices") (part "Cap"))
    )
    (comp (ref "C112")
      (value "Cap")
      (footprint "6-0805_N")
      (description "Capacitor")
      (fields (field (name "ALTIUM_VALUE") "220nF") (field (name "PUBLISHER") "Altium Limited"))
      (libsource (lib "Miscellaneous Devices") (part "Cap"))
    )
    (comp (ref "C113")
      (value "Cap")
      (footprint "6-0805_N")
      (description "Capacitor")
      (fields (field (name "ALTIUM_VALUE") "8.2nF") (field (name "PUBLISHER") "Altium Limited"))
      (libsource (lib "Miscellaneous Devices") (part "Cap"))
    )
    (comp (ref "C114")
      (value "Cap")
      (footprint "6-0805_N")
      (description "Capacitor")
      (fields (field (name "ALTIUM_VALUE") "18nF") (field (name "PUBLISHER") "Altium Limited"))
      (libsource (lib "Miscellaneous Devices") (part "Cap"))
    )
    (comp (ref "C115")
      (value "Cap")
      (footprint "6-0805_N")
      (description "Capacitor")
      (fields (field (name "ALTIUM_VALUE") "100nF") (field (name "PUBLISHER") "Altium Limited"))
      (libsource (lib "Miscellaneous Devices") (part "Cap"))
    )
    (comp (ref "C116")
      (value "Cap")
      (footprint "6-0805_N")
      (description "Capacitor")
      (fields (field (name "ALTIUM_VALUE") "10uF") (field (name "PUBLISHER") "Altium Limited"))
      (libsource (lib "Miscellaneous Devices") (part "Cap"))
    )
    (comp (ref "C117")
      (value "Cap")
      (footprint "6-0805_N")
      (description "Capacitor")
      (fields (field (name "ALTIUM_VALUE") "100nF") (field (name "PUBLISHER") "Altium Limited"))
      (libsource (lib "Miscellaneous Devices") (part "Cap"))
    )
    (comp (ref "C119")
      (value "Cap")
      (footprint "6-0805_N")
      (description "Capacitor")
      (fields (field (name "ALTIUM_VALUE") "1n") (field (name "PUBLISHER") "Altium Limited"))
      (libsource (lib "Miscellaneous Devices") (part "Cap"))
    )
    (comp (ref "C120")
      (value "Cap")
      (footprint "6-0805_N")
      (description "Capacitor")
      (fields (field (name "ALTIUM_VALUE") "180p") (field (name "PUBLISHER") "Altium Limited"))
      (libsource (lib "Miscellaneous Devices") (part "Cap"))
    )
    (comp (ref "C121")
      (value "Cap")
      (footprint "6-0805_N")
      (description "Capacitor")
      (fields (field (name "ALTIUM_VALUE") "10nF") (field (name "PUBLISHER") "Altium Limited"))
      (libsource (lib "Miscellaneous Devices") (part "Cap"))
    )
    (comp (ref "C122")
      (value "Cap")
      (footprint "6-0805_N")
      (description "Capacitor")
      (fields (field (name "ALTIUM_VALUE") "10nF") (field (name "PUBLISHER") "Altium Limited"))
      (libsource (lib "Miscellaneous Devices") (part "Cap"))
    )
    (comp (ref "C123")
      (value "Cap")
      (footprint "6-0805_N")
      (description "Capacitor")
      (fields (field (name "ALTIUM_VALUE") "100nF") (field (name "PUBLISHER") "Altium Limited"))
      (libsource (lib "Miscellaneous Devices") (part "Cap"))
    )
    (comp (ref "C124")
      (value "Cap")
      (footprint "6-0805_N")
      (description "Capacitor")
      (fields (field (name "ALTIUM_VALUE") "2.2uF") (field (name "PUBLISHER") "Altium Limited"))
      (libsource (lib "Miscellaneous Devices") (part "Cap"))
    )
    (comp (ref "C125")
      (value "Cap")
      (footprint "6-0805_N")
      (description "Capacitor")
      (fields (field (name "ALTIUM_VALUE") "220nF") (field (name "PUBLISHER") "Altium Limited"))
      (libsource (lib "Miscellaneous Devices") (part "Cap"))
    )
    (comp (ref "C126")
      (value "Cap")
      (footprint "6-0805_N")
      (description "Capacitor")
      (fields (field (name "ALTIUM_VALUE") "8.2nF") (field (name "PUBLISHER") "Altium Limited"))
      (libsource (lib "Miscellaneous Devices") (part "Cap"))
    )
    (comp (ref "C127")
      (value "Cap")
      (footprint "6-0805_N")
      (description "Capacitor")
      (fields (field (name "ALTIUM_VALUE") "18nF") (field (name "PUBLISHER") "Altium Limited"))
      (libsource (lib "Miscellaneous Devices") (part "Cap"))
    )
    (comp (ref "C128")
      (value "Cap")
      (footprint "6-0805_N")
      (description "Capacitor")
      (fields (field (name "ALTIUM_VALUE") "100nF") (field (name "PUBLISHER") "Altium Limited"))
      (libsource (lib "Miscellaneous Devices") (part "Cap"))
    )
    (comp (ref "C129")
      (value "Cap")
      (footprint "6-0805_N")
      (description "Capacitor")
      (fields (field (name "ALTIUM_VALUE") "100nF") (field (name "PUBLISHER") "Altium Limited"))
      (libsource (lib "Miscellaneous Devices") (part "Cap"))
    )
    (comp (ref "C130")
      (value "Cap")
      (footprint "6-0805_N")
      (description "Capacitor")
      (fields (field (name "ALTIUM_VALUE") "100nF") (field (name "PUBLISHER") "Altium Limited"))
      (libsource (lib "Miscellaneous Devices") (part "Cap"))
    )
    (comp (ref "C131")
      (value "Cap")
      (footprint "6-0805_N")
      (description "Capacitor")
      (fields (field (name "ALTIUM_VALUE") "100nF") (field (name "PUBLISHER") "Altium Limited"))
      (libsource (lib "Miscellaneous Devices") (part "Cap"))
    )
    (comp (ref "C132")
      (value "Cap")
      (footprint "6-0805_N")
      (description "Capacitor")
      (fields (field (name "ALTIUM_VALUE") "100nF") (field (name "PUBLISHER") "Altium Limited"))
      (libsource (lib "Miscellaneous Devices") (part "Cap"))
    )
    (comp (ref "C133")
      (value "Cap")
      (footprint "6-0805_N")
      (description "Capacitor")
      (fields (field (name "ALTIUM_VALUE") "100nF") (field (name "PUBLISHER") "Altium Limited"))
      (libsource (lib "Miscellaneous Devices") (part "Cap"))
    )
    (comp (ref "C134")
      (value "Cap")
      (footprint "6-0805_N")
      (description "Capacitor")
      (fields (field (name "ALTIUM_VALUE") "0.1uF") (field (name "PUBLISHER") "Altium Limited"))
      (libsource (lib "Miscellaneous Devices") (part "Cap"))
    )
    (comp (ref "C135")
      (value "Cap")
      (footprint "6-0805_N")
      (description "Capacitor")
      (fields (field (name "ALTIUM_VALUE") "36pF") (field (name "PUBLISHER") "Altium Limited"))
      (libsource (lib "Miscellaneous Devices") (part "Cap"))
    )
    (comp (ref "C136")
      (value "Cap")
      (footprint "6-0805_N")
      (description "Capacitor")
      (fields (field (name "ALTIUM_VALUE") "36pF") (field (name "PUBLISHER") "Altium Limited"))
      (libsource (lib "Miscellaneous Devices") (part "Cap"))
    )
    (comp (ref "C137")
      (value "Cap")
      (footprint "6-0805_N")
      (description "Capacitor")
      (fields (field (name "ALTIUM_VALUE") "10uF") (field (name "PUBLISHER") "Altium Limited"))
      (libsource (lib "Miscellaneous Devices") (part "Cap"))
    )
    (comp (ref "C138")
      (value "Cap")
      (footprint "6-0805_N")
      (description "Capacitor")
      (fields (field (name "ALTIUM_VALUE") "100nF") (field (name "PUBLISHER") "Altium Limited"))
      (libsource (lib "Miscellaneous Devices") (part "Cap"))
    )
    (comp (ref "C139")
      (value "Cap")
      (footprint "6-0805_N")
      (description "Capacitor")
      (fields (field (name "ALTIUM_VALUE") "10uF") (field (name "PUBLISHER") "Altium Limited"))
      (libsource (lib "Miscellaneous Devices") (part "Cap"))
    )
    (comp (ref "C140")
      (value "Cap")
      (footprint "6-0805_N")
      (description "Capacitor")
      (fields (field (name "ALTIUM_VALUE") "100nF") (field (name "PUBLISHER") "Altium Limited"))
      (libsource (lib "Miscellaneous Devices") (part "Cap"))
    )
    (comp (ref "C141")
      (value "Cap Pol1")
      (footprint "UUQ1C470MCL1GB")
      (description "Polarized Capacitor (Radial)")
      (fields (field (name "ALTIUM_VALUE") "47uF") (field (name "PUBLISHER") "Altium Limited"))
      (libsource (lib "Miscellaneous Devices") (part "Cap Pol1"))
    )
    (comp (ref "C142")
      (value "Cap")
      (footprint "6-0805_N")
      (description "Capacitor")
      (fields (field (name "ALTIUM_VALUE") "10uF") (field (name "PUBLISHER") "Altium Limited"))
      (libsource (lib "Miscellaneous Devices") (part "Cap"))
    )
    (comp (ref "C143")
      (value "Cap")
      (footprint "6-0805_N")
      (description "Capacitor")
      (fields (field (name "ALTIUM_VALUE") "0.1uF") (field (name "PUBLISHER") "Altium Limited"))
      (libsource (lib "Miscellaneous Devices") (part "Cap"))
    )
    (comp (ref "C145")
      (value "Cap")
      (footprint "6-0805_N")
      (description "Capacitor")
      (fields (field (name "ALTIUM_VALUE") "1uF") (field (name "PUBLISHER") "Altium Limited"))
      (libsource (lib "Miscellaneous Devices") (part "Cap"))
    )
    (comp (ref "C146")
      (value "Cap")
      (footprint "6-0805_N")
      (description "Capacitor")
      (fields (field (name "ALTIUM_VALUE") "22uF") (field (name "PUBLISHER") "Altium Limited"))
      (libsource (lib "Miscellaneous Devices") (part "Cap"))
    )
    (comp (ref "C147")
      (value "Cap")
      (footprint "6-0805_N")
      (description "Capacitor")
      (fields (field (name "ALTIUM_VALUE") "100nF") (field (name "PUBLISHER") "Altium Limited"))
      (libsource (lib "Miscellaneous Devices") (part "Cap"))
    )
    (comp (ref "C148")
      (value "Cap")
      (footprint "6-0805_N")
      (description "Capacitor")
      (fields (field (name "ALTIUM_VALUE") "10uF") (field (name "PUBLISHER") "Altium Limited"))
      (libsource (lib "Miscellaneous Devices") (part "Cap"))
    )
    (comp (ref "C149")
      (value "Cap")
      (footprint "6-0805_N")
      (description "Capacitor")
      (fields (field (name "ALTIUM_VALUE") "0.1uF") (field (name "PUBLISHER") "Altium Limited"))
      (libsource (lib "Miscellaneous Devices") (part "Cap"))
    )
    (comp (ref "C150")
      (value "Cap")
      (footprint "6-0805_N")
      (description "Capacitor")
      (fields (field (name "ALTIUM_VALUE") "1u") (field (name "PUBLISHER") "Altium Limited"))
      (libsource (lib "Miscellaneous Devices") (part "Cap"))
    )
    (comp (ref "C151")
      (value "Cap")
      (footprint "6-0805_N")
      (description "Capacitor")
      (fields (field (name "ALTIUM_VALUE") "1u") (field (name "PUBLISHER") "Altium Limited"))
      (libsource (lib "Miscellaneous Devices") (part "Cap"))
    )
    (comp (ref "C152")
      (value "Cap")
      (footprint "6-0805_N")
      (description "Capacitor")
      (fields (field (name "ALTIUM_VALUE") "100nF") (field (name "PUBLISHER") "Altium Limited"))
      (libsource (lib "Miscellaneous Devices") (part "Cap"))
    )
    (comp (ref "C153")
      (value "Cap")
      (footprint "6-0805_N")
      (description "Capacitor")
      (fields (field (name "ALTIUM_VALUE") "1u") (field (name "PUBLISHER") "Altium Limited"))
      (libsource (lib "Miscellaneous Devices") (part "Cap"))
    )
    (comp (ref "C155")
      (value "Cap")
      (footprint "6-0805_N")
      (description "Capacitor")
      (fields (field (name "ALTIUM_VALUE") "1u") (field (name "PUBLISHER") "Altium Limited"))
      (libsource (lib "Miscellaneous Devices") (part "Cap"))
    )
    (comp (ref "C156")
      (value "Cap")
      (footprint "6-0805_N")
      (description "Capacitor")
      (fields (field (name "ALTIUM_VALUE") "100nF") (field (name "PUBLISHER") "Altium Limited"))
      (libsource (lib "Miscellaneous Devices") (part "Cap"))
    )
    (comp (ref "C157")
      (value "Cap")
      (footprint "6-0805_N")
      (description "Capacitor")
      (fields (field (name "ALTIUM_VALUE") "1u") (field (name "PUBLISHER") "Altium Limited"))
      (libsource (lib "Miscellaneous Devices") (part "Cap"))
    )
    (comp (ref "C158")
      (value "Cap")
      (footprint "6-0805_N")
      (description "Capacitor")
      (fields (field (name "ALTIUM_VALUE") "1u") (field (name "PUBLISHER") "Altium Limited"))
      (libsource (lib "Miscellaneous Devices") (part "Cap"))
    )
    (comp (ref "C159")
      (value "Cap")
      (footprint "6-0805_N")
      (description "Capacitor")
      (fields (field (name "ALTIUM_VALUE") "22uF") (field (name "PUBLISHER") "Altium Limited"))
      (libsource (lib "Miscellaneous Devices") (part "Cap"))
    )
    (comp (ref "C160")
      (value "Cap")
      (footprint "6-0805_N")
      (description "Capacitor")
      (fields (field (name "ALTIUM_VALUE") "22uF") (field (name "PUBLISHER") "Altium Limited"))
      (libsource (lib "Miscellaneous Devices") (part "Cap"))
    )
    (comp (ref "C161")
      (value "Cap")
      (footprint "6-0805_N")
      (description "Capacitor")
      (fields (field (name "ALTIUM_VALUE") "100nF") (field (name "PUBLISHER") "Altium Limited"))
      (libsource (lib "Miscellaneous Devices") (part "Cap"))
    )
    (comp (ref "C162")
      (value "Cap")
      (footprint "6-0805_N")
      (description "Capacitor")
      (fields (field (name "ALTIUM_VALUE") "22uF") (field (name "PUBLISHER") "Altium Limited"))
      (libsource (lib "Miscellaneous Devices") (part "Cap"))
    )
    (comp (ref "C163")
      (value "Cap")
      (footprint "6-0805_N")
      (description "Capacitor")
      (fields (field (name "ALTIUM_VALUE") "22uF") (field (name "PUBLISHER") "Altium Limited"))
      (libsource (lib "Miscellaneous Devices") (part "Cap"))
    )
    (comp (ref "C164")
      (value "Cap")
      (footprint "6-0805_N")
      (description "Capacitor")
      (fields (field (name "ALTIUM_VALUE") "0.1uF") (field (name "PUBLISHER") "Altium Limited"))
      (libsource (lib "Miscellaneous Devices") (part "Cap"))
    )
    (comp (ref "C165")
      (value "Cap")
      (footprint "6-0805_N")
      (description "Capacitor")
      (fields (field (name "ALTIUM_VALUE") "22uF") (field (name "PUBLISHER") "Altium Limited"))
      (libsource (lib "Miscellaneous Devices") (part "Cap"))
    )
    (comp (ref "C166")
      (value "Cap")
      (footprint "6-0805_N")
      (description "Capacitor")
      (fields (field (name "ALTIUM_VALUE") "22uF") (field (name "PUBLISHER") "Altium Limited"))
      (libsource (lib "Miscellaneous Devices") (part "Cap"))
    )
    (comp (ref "C167")
      (value "Cap")
      (footprint "6-0805_N")
      (description "Capacitor")
      (fields (field (name "ALTIUM_VALUE") "22uF") (field (name "PUBLISHER") "Altium Limited"))
      (libsource (lib "Miscellaneous Devices") (part "Cap"))
    )
    (comp (ref "C168")
      (value "Cap")
      (footprint "6-0805_N")
      (description "Capacitor")
      (fields (field (name "ALTIUM_VALUE") "22uF") (field (name "PUBLISHER") "Altium Limited"))
      (libsource (lib "Miscellaneous Devices") (part "Cap"))
    )
    (comp (ref "C169")
      (value "Cap")
      (footprint "6-0805_N")
      (description "Capacitor")
      (fields (field (name "ALTIUM_VALUE") "22uF") (field (name "PUBLISHER") "Altium Limited"))
      (libsource (lib "Miscellaneous Devices") (part "Cap"))
    )
    (comp (ref "C170")
      (value "Cap")
      (footprint "6-0805_N")
      (description "Capacitor")
      (fields (field (name "ALTIUM_VALUE") "22uF") (field (name "PUBLISHER") "Altium Limited"))
      (libsource (lib "Miscellaneous Devices") (part "Cap"))
    )
    (comp (ref "C171")
      (value "Cap")
      (footprint "6-0805_N")
      (description "Capacitor")
      (fields (field (name "ALTIUM_VALUE") "22uF") (field (name "PUBLISHER") "Altium Limited"))
      (libsource (lib "Miscellaneous Devices") (part "Cap"))
    )
    (comp (ref "C172")
      (value "Cap")
      (footprint "6-0805_N")
      (description "Capacitor")
      (fields (field (name "ALTIUM_VALUE") ".22uF") (field (name "PUBLISHER") "Altium Limited"))
      (libsource (lib "Miscellaneous Devices") (part "Cap"))
    )
    (comp (ref "CU1")
      (value "10nF")
      (footprint "C0805")
      (description "Polarized Capacitor (Surface Mount)")
      (fields (field (name "Comment") "Cap Pol3") (field (name "PUBLISHER") "Altium Limited"))
      (libsource (lib "") (part "Cap Pol3_1"))
    )
    (comp (ref "CU2")
      (value "100nF")
      (footprint "C0805")
      (description "Polarized Capacitor (Surface Mount)")
      (fields (field (name "Comment") "Cap Pol3") (field (name "PUBLISHER") "Altium Limited"))
      (libsource (lib "Miscellaneous Devices") (part "Cap Pol3"))
    )
    (comp (ref "CU3")
      (value "4.7uF")
      (footprint "C0805")
      (description "Polarized Capacitor (Surface Mount)")
      (fields (field (name "Comment") "Cap Pol3") (field (name "PUBLISHER") "Altium Limited"))
      (libsource (lib "Miscellaneous Devices") (part "Cap Pol3"))
    )
    (comp (ref "CU4")
      (value "100nF")
      (footprint "C0805")
      (description "Polarized Capacitor (Surface Mount)")
      (fields (field (name "Comment") "Cap Pol3") (field (name "PUBLISHER") "Altium Limited"))
      (libsource (lib "Miscellaneous Devices") (part "Cap Pol3"))
    )
    (comp (ref "D1")
      (value "Diode BAT17")
      (footprint "Shotky")
      (description "Schottky Rectifier")
      (fields (field (name "PUBLISHER") "Altium Limited"))
      (libsource (lib "Miscellaneous Devices") (part "Diode 11DQ03"))
    )
    (comp (ref "D2")
      (value "Diode BAT17")
      (footprint "Shotky")
      (description "Schottky Rectifier")
      (fields (field (name "PUBLISHER") "Altium Limited"))
      (libsource (lib "Miscellaneous Devices") (part "Diode 11DQ03"))
    )
    (comp (ref "D3")
      (value "Diode BAT17")
      (footprint "Shotky")
      (description "Schottky Rectifier")
      (fields (field (name "PUBLISHER") "Altium Limited"))
      (libsource (lib "Miscellaneous Devices") (part "Diode 11DQ03"))
    )
    (comp (ref "D4")
      (value "Diode BAT17")
      (footprint "Shotky")
      (description "Schottky Rectifier")
      (fields (field (name "PUBLISHER") "Altium Limited"))
      (libsource (lib "Miscellaneous Devices") (part "Diode 11DQ03"))
    )
    (comp (ref "D_Power")
      (value "Diode")
      (footprint "C1206")
      (description "Default Diode")
      (fields (field (name "PUBLISHER") "Altium Limited"))
      (libsource (lib "Miscellaneous Devices") (part "Diode"))
    )
    (comp (ref "D_TCK")
      (value "Diode")
      (footprint "C1206")
      (description "Default Diode")
      (fields (field (name "PUBLISHER") "Altium Limited"))
      (libsource (lib "Miscellaneous Devices") (part "Diode"))
    )
    (comp (ref "D_TDO")
      (value "Diode")
      (footprint "C1206")
      (description "Default Diode")
      (fields (field (name "PUBLISHER") "Altium Limited"))
      (libsource (lib "Miscellaneous Devices") (part "Diode"))
    )
    (comp (ref "D_USB_RX")
      (value "Diode")
      (footprint "C1206")
      (description "Default Diode")
      (fields (field (name "PUBLISHER") "Altium Limited"))
      (libsource (lib "Miscellaneous Devices") (part "Diode"))
    )
    (comp (ref "D_USB_TX")
      (value "Diode")
      (footprint "C1206")
      (description "Default Diode")
      (fields (field (name "PUBLISHER") "Altium Limited"))
      (libsource (lib "Miscellaneous Devices") (part "Diode"))
    )
    (comp (ref "Ethernet Port")
      (value "RJ45")
      (footprint "RJ45")
      (libsource (lib "Senior_SCH_Lib") (part "RJ45"))
    )
    (comp (ref "FB1")
      (value "~")
      (footprint "C0805")
      (description "Ferrite Bead - 0805")
      (fields (field (name "PUBLISHER") "Altium Limited"))
      (libsource (lib "Miscellaneous Devices") (part "Cap Pol3"))
    )
    (comp (ref "Foot Switch")
      (value "LATCH SWITCH")
      (footprint "FOOTSWITCH")
      (libsource (lib "Senior_SCH_Lib") (part "LATCH SWITCH"))
    )
    (comp (ref "FTDI USB UART")
      (value "FT232RL")
      (footprint "FT232R")
      (libsource (lib "Senior_SCH_Lib") (part "FT232RL"))
    )
    (comp (ref "GPIO Breakout")
      (value "Header 11X2")
      (footprint "HDR2X11")
      (description "Header, 11-Pin, Dual row")
      (fields (field (name "PUBLISHER") "Altium Limited"))
      (libsource (lib "Miscellaneous Connectors") (part "Header 11X2"))
    )
    (comp (ref "JTAG")
      (value "Header 7X2")
      (footprint "HDR2X7")
      (description "Header, 7-Pin, Dual row")
      (fields (field (name "PUBLISHER") "Altium Limited"))
      (libsource (lib "Miscellaneous Connectors") (part "Header 7X2"))
    )
    (comp (ref "L1")
      (value "Inductor")
      (footprint "FIXED IND 4.7UH")
      (fields (field (name "ALTIUM_VALUE") "4.7uH") (field (name "PUBLISHER") "Altium Limited"))
      (libsource (lib "Miscellaneous Devices") (part "Inductor"))
    )
    (comp (ref "L4")
      (value "Inductor")
      (footprint "FIXED IND 4.7UH")
      (fields (field (name "ALTIUM_VALUE") "4.7uH") (field (name "PUBLISHER") "Altium Limited"))
      (libsource (lib "Miscellaneous Devices") (part "Inductor"))
    )
    (comp (ref "L6")
      (value "Inductor")
      (footprint "FIXED IND 4.7UH")
      (fields (field (name "ALTIUM_VALUE") "3.3uH") (field (name "PUBLISHER") "Altium Limited"))
      (libsource (lib "Miscellaneous Devices") (part "Inductor"))
    )
    (comp (ref "L7")
      (value "Inductor")
      (footprint "FIXED IND 4.7UH")
      (fields (field (name "ALTIUM_VALUE") "3.3uH") (field (name "PUBLISHER") "Altium Limited"))
      (libsource (lib "Miscellaneous Devices") (part "Inductor"))
    )
    (comp (ref "MINI USB")
      (value "MINI USB B")
      (footprint "MINI USB B")
      (libsource (lib "Senior_SCH_Lib") (part "MINI USB B"))
    )
    (comp (ref "R1")
      (value "4.22k")
      (footprint "6-0805_N")
      (description "Resistor")
      (fields (field (name "PUBLISHER") "Altium Limited"))
      (libsource (lib "Miscellaneous Devices") (part "Res3"))
    )
    (comp (ref "R2")
      (value "130k")
      (footprint "6-0805_N")
      (description "Resistor")
      (fields (field (name "PUBLISHER") "Altium Limited"))
      (libsource (lib "Miscellaneous Devices") (part "Res3"))
    )
    (comp (ref "R3")
      (value "102k")
      (footprint "6-0805_N")
      (description "Resistor")
      (fields (field (name "PUBLISHER") "Altium Limited"))
      (libsource (lib "Miscellaneous Devices") (part "Res3"))
    )
    (comp (ref "R4")
      (value "24k")
      (footprint "6-0805_N")
      (description "Resistor")
      (fields (field (name "PUBLISHER") "Altium Limited"))
      (libsource (lib "Miscellaneous Devices") (part "Res3"))
    )
    (comp (ref "R5")
      (value "1k")
      (footprint "6-0805_N")
      (description "Resistor")
      (fields (field (name "PUBLISHER") "Altium Limited"))
      (libsource (lib "Miscellaneous Devices") (part "Res3"))
    )
    (comp (ref "R6")
      (value "100mOhm")
      (footprint "6-0805_N")
      (description "Resistor")
      (fields (field (name "PUBLISHER") "Altium Limited"))
      (libsource (lib "Miscellaneous Devices") (part "Res3"))
    )
    (comp (ref "R7")
      (value "100mOhm")
      (footprint "6-0805_N")
      (description "Resistor")
      (fields (field (name "PUBLISHER") "Altium Limited"))
      (libsource (lib "Miscellaneous Devices") (part "Res3"))
    )
    (comp (ref "R8")
      (value "5.76k")
      (footprint "6-0805_N")
      (description "Resistor")
      (fields (field (name "PUBLISHER") "Altium Limited"))
      (libsource (lib "Miscellaneous Devices") (part "Res3"))
    )
    (comp (ref "R9")
      (value "10k")
      (footprint "6-0805_N")
      (description "Resistor")
      (fields (field (name "PUBLISHER") "Altium Limited"))
      (libsource (lib "Miscellaneous Devices") (part "Res3"))
    )
    (comp (ref "R10")
      (value "47k")
      (footprint "6-0805_N")
      (description "Resistor")
      (fields (field (name "PUBLISHER") "Altium Limited"))
      (libsource (lib "Miscellaneous Devices") (part "Res3"))
    )
    (comp (ref "R11")
      (value "2.49k")
      (footprint "6-0805_N")
      (description "Resistor")
      (fields (field (name "PUBLISHER") "Altium Limited"))
      (libsource (lib "Miscellaneous Devices") (part "Res3"))
    )
    (comp (ref "R12")
      (value "1.02k")
      (footprint "6-0805_N")
      (description "Resistor")
      (fields (field (name "PUBLISHER") "Altium Limited"))
      (libsource (lib "Miscellaneous Devices") (part "Res3"))
    )
    (comp (ref "R13")
      (value "2.49k")
      (footprint "6-0805_N")
      (description "Resistor")
      (fields (field (name "PUBLISHER") "Altium Limited"))
      (libsource (lib "Miscellaneous Devices") (part "Res3"))
    )
    (comp (ref "R14")
      (value "1.02k")
      (footprint "6-0805_N")
      (description "Resistor")
      (fields (field (name "PUBLISHER") "Altium Limited"))
      (libsource (lib "Miscellaneous Devices") (part "Res3"))
    )
    (comp (ref "R15")
      (value "1.2k")
      (footprint "6-0805_N")
      (description "Resistor")
      (fields (field (name "PUBLISHER") "Altium Limited"))
      (libsource (lib "Miscellaneous Devices") (part "Res3"))
    )
    (comp (ref "R16")
      (value "330")
      (footprint "6-0805_N")
      (description "Resistor")
      (fields (field (name "PUBLISHER") "Altium Limited"))
      (libsource (lib "Miscellaneous Devices") (part "Res3"))
    )
    (comp (ref "R17")
      (value "12")
      (footprint "6-0805_N")
      (description "Resistor")
      (fields (field (name "PUBLISHER") "Altium Limited"))
      (libsource (lib "Miscellaneous Devices") (part "Res3"))
    )
    (comp (ref "R18")
      (value "5.1")
      (footprint "6-0805_N")
      (description "Resistor")
      (fields (field (name "PUBLISHER") "Altium Limited"))
      (libsource (lib "Miscellaneous Devices") (part "Res3"))
    )
    (comp (ref "R19")
      (value "12.1k")
      (footprint "6-0805_N")
      (description "Resistor")
      (fields (field (name "PUBLISHER") "Altium Limited"))
      (libsource (lib "Miscellaneous Devices") (part "Res3"))
    )
    (comp (ref "R20")
      (value "3.57k")
      (footprint "6-0805_N")
      (description "Resistor")
      (fields (field (name "PUBLISHER") "Altium Limited"))
      (libsource (lib "Miscellaneous Devices") (part "Res3"))
    )
    (comp (ref "R21")
      (value "9.53k")
      (footprint "6-0805_N")
      (description "Resistor")
      (fields (field (name "PUBLISHER") "Altium Limited"))
      (libsource (lib "Miscellaneous Devices") (part "Res3"))
    )
    (comp (ref "R22")
      (value "10k")
      (footprint "6-0805_N")
      (description "Resistor")
      (fields (field (name "PUBLISHER") "Altium Limited"))
      (libsource (lib "Miscellaneous Devices") (part "Res3"))
    )
    (comp (ref "R23")
      (value "5.1")
      (footprint "6-0805_N")
      (description "Resistor")
      (fields (field (name "PUBLISHER") "Altium Limited"))
      (libsource (lib "Miscellaneous Devices") (part "Res3"))
    )
    (comp (ref "R24")
      (value "12")
      (footprint "6-0805_N")
      (description "Resistor")
      (fields (field (name "PUBLISHER") "Altium Limited"))
      (libsource (lib "Miscellaneous Devices") (part "Res3"))
    )
    (comp (ref "R25")
      (value "1.2k")
      (footprint "6-0805_N")
      (description "Resistor")
      (fields (field (name "PUBLISHER") "Altium Limited"))
      (libsource (lib "Miscellaneous Devices") (part "Res3"))
    )
    (comp (ref "R26")
      (value "330")
      (footprint "6-0805_N")
      (description "Resistor")
      (fields (field (name "PUBLISHER") "Altium Limited"))
      (libsource (lib "Miscellaneous Devices") (part "Res3"))
    )
    (comp (ref "R27")
      (value "4.22k")
      (footprint "6-0805_N")
      (description "Resistor")
      (fields (field (name "PUBLISHER") "Altium Limited"))
      (libsource (lib "Miscellaneous Devices") (part "Res3"))
    )
    (comp (ref "R28")
      (value "10k")
      (footprint "6-0805_N")
      (description "Resistor")
      (fields (field (name "PUBLISHER") "Altium Limited"))
      (libsource (lib "Miscellaneous Devices") (part "Res3"))
    )
    (comp (ref "R29")
      (value "10k")
      (footprint "6-0805_N")
      (description "Resistor")
      (fields (field (name "PUBLISHER") "Altium Limited"))
      (libsource (lib "Miscellaneous Devices") (part "Res3"))
    )
    (comp (ref "R30")
      (value "1.2k")
      (footprint "6-0805_N")
      (description "Resistor")
      (fields (field (name "PUBLISHER") "Altium Limited"))
      (libsource (lib "Miscellaneous Devices") (part "Res3"))
    )
    (comp (ref "R31")
      (value "4.22k")
      (footprint "6-0805_N")
      (description "Resistor")
      (fields (field (name "PUBLISHER") "Altium Limited"))
      (libsource (lib "Miscellaneous Devices") (part "Res3"))
    )
    (comp (ref "R32")
      (value "2.49k")
      (footprint "6-0805_N")
      (description "Resistor")
      (fields (field (name "PUBLISHER") "Altium Limited"))
      (libsource (lib "Miscellaneous Devices") (part "Res3"))
    )
    (comp (ref "R33")
      (value "1.02k")
      (footprint "6-0805_N")
      (description "Resistor")
      (fields (field (name "PUBLISHER") "Altium Limited"))
      (libsource (lib "Miscellaneous Devices") (part "Res3"))
    )
    (comp (ref "R34")
      (value "2.49k")
      (footprint "6-0805_N")
      (description "Resistor")
      (fields (field (name "PUBLISHER") "Altium Limited"))
      (libsource (lib "Miscellaneous Devices") (part "Res3"))
    )
    (comp (ref "R35")
      (value "1.02k")
      (footprint "6-0805_N")
      (description "Resistor")
      (fields (field (name "PUBLISHER") "Altium Limited"))
      (libsource (lib "Miscellaneous Devices") (part "Res3"))
    )
    (comp (ref "R36")
      (value "330")
      (footprint "6-0805_N")
      (description "Resistor")
      (fields (field (name "PUBLISHER") "Altium Limited"))
      (libsource (lib "Miscellaneous Devices") (part "Res3"))
    )
    (comp (ref "R37")
      (value "12")
      (footprint "6-0805_N")
      (description "Resistor")
      (fields (field (name "PUBLISHER") "Altium Limited"))
      (libsource (lib "Miscellaneous Devices") (part "Res3"))
    )
    (comp (ref "R38")
      (value "5.1")
      (footprint "6-0805_N")
      (description "Resistor")
      (fields (field (name "PUBLISHER") "Altium Limited"))
      (libsource (lib "Miscellaneous Devices") (part "Res3"))
    )
    (comp (ref "R39")
      (value "12.1k")
      (footprint "6-0805_N")
      (description "Resistor")
      (fields (field (name "PUBLISHER") "Altium Limited"))
      (libsource (lib "Miscellaneous Devices") (part "Res3"))
    )
    (comp (ref "R40")
      (value "3.57k")
      (footprint "6-0805_N")
      (description "Resistor")
      (fields (field (name "PUBLISHER") "Altium Limited"))
      (libsource (lib "Miscellaneous Devices") (part "Res3"))
    )
    (comp (ref "R41")
      (value "9.53k")
      (footprint "6-0805_N")
      (description "Resistor")
      (fields (field (name "PUBLISHER") "Altium Limited"))
      (libsource (lib "Miscellaneous Devices") (part "Res3"))
    )
    (comp (ref "R42")
      (value "10k")
      (footprint "6-0805_N")
      (description "Resistor")
      (fields (field (name "PUBLISHER") "Altium Limited"))
      (libsource (lib "Miscellaneous Devices") (part "Res3"))
    )
    (comp (ref "R43")
      (value "5.1")
      (footprint "6-0805_N")
      (description "Resistor")
      (fields (field (name "PUBLISHER") "Altium Limited"))
      (libsource (lib "Miscellaneous Devices") (part "Res3"))
    )
    (comp (ref "R44")
      (value "12")
      (footprint "6-0805_N")
      (description "Resistor")
      (fields (field (name "PUBLISHER") "Altium Limited"))
      (libsource (lib "Miscellaneous Devices") (part "Res3"))
    )
    (comp (ref "R45")
      (value "1.2k")
      (footprint "6-0805_N")
      (description "Resistor")
      (fields (field (name "PUBLISHER") "Altium Limited"))
      (libsource (lib "Miscellaneous Devices") (part "Res3"))
    )
    (comp (ref "R46")
      (value "330")
      (footprint "6-0805_N")
      (description "Resistor")
      (fields (field (name "PUBLISHER") "Altium Limited"))
      (libsource (lib "Miscellaneous Devices") (part "Res3"))
    )
    (comp (ref "R47")
      (value "4.22k")
      (footprint "6-0805_N")
      (description "Resistor")
      (fields (field (name "PUBLISHER") "Altium Limited"))
      (libsource (lib "Miscellaneous Devices") (part "Res3"))
    )
    (comp (ref "R48")
      (value "1.2k")
      (footprint "6-0805_N")
      (description "Resistor")
      (fields (field (name "PUBLISHER") "Altium Limited"))
      (libsource (lib "Miscellaneous Devices") (part "Res3"))
    )
    (comp (ref "R49")
      (value "4.22k")
      (footprint "6-0805_N")
      (description "Resistor")
      (fields (field (name "PUBLISHER") "Altium Limited"))
      (libsource (lib "Miscellaneous Devices") (part "Res3"))
    )
    (comp (ref "R50")
      (value "2.49k")
      (footprint "6-0805_N")
      (description "Resistor")
      (fields (field (name "PUBLISHER") "Altium Limited"))
      (libsource (lib "Miscellaneous Devices") (part "Res3"))
    )
    (comp (ref "R51")
      (value "1.02k")
      (footprint "6-0805_N")
      (description "Resistor")
      (fields (field (name "PUBLISHER") "Altium Limited"))
      (libsource (lib "Miscellaneous Devices") (part "Res3"))
    )
    (comp (ref "R52")
      (value "2.49k")
      (footprint "6-0805_N")
      (description "Resistor")
      (fields (field (name "PUBLISHER") "Altium Limited"))
      (libsource (lib "Miscellaneous Devices") (part "Res3"))
    )
    (comp (ref "R53")
      (value "1.02k")
      (footprint "6-0805_N")
      (description "Resistor")
      (fields (field (name "PUBLISHER") "Altium Limited"))
      (libsource (lib "Miscellaneous Devices") (part "Res3"))
    )
    (comp (ref "R54")
      (value "330")
      (footprint "6-0805_N")
      (description "Resistor")
      (fields (field (name "PUBLISHER") "Altium Limited"))
      (libsource (lib "Miscellaneous Devices") (part "Res3"))
    )
    (comp (ref "R55")
      (value "12")
      (footprint "6-0805_N")
      (description "Resistor")
      (fields (field (name "PUBLISHER") "Altium Limited"))
      (libsource (lib "Miscellaneous Devices") (part "Res3"))
    )
    (comp (ref "R56")
      (value "5.1")
      (footprint "6-0805_N")
      (description "Resistor")
      (fields (field (name "PUBLISHER") "Altium Limited"))
      (libsource (lib "Miscellaneous Devices") (part "Res3"))
    )
    (comp (ref "R57")
      (value "12.1k")
      (footprint "6-0805_N")
      (description "Resistor")
      (fields (field (name "PUBLISHER") "Altium Limited"))
      (libsource (lib "Miscellaneous Devices") (part "Res3"))
    )
    (comp (ref "R58")
      (value "3.57k")
      (footprint "6-0805_N")
      (description "Resistor")
      (fields (field (name "PUBLISHER") "Altium Limited"))
      (libsource (lib "Miscellaneous Devices") (part "Res3"))
    )
    (comp (ref "R59")
      (value "9.53k")
      (footprint "6-0805_N")
      (description "Resistor")
      (fields (field (name "PUBLISHER") "Altium Limited"))
      (libsource (lib "Miscellaneous Devices") (part "Res3"))
    )
    (comp (ref "R60")
      (value "10k")
      (footprint "6-0805_N")
      (description "Resistor")
      (fields (field (name "PUBLISHER") "Altium Limited"))
      (libsource (lib "Miscellaneous Devices") (part "Res3"))
    )
    (comp (ref "R61")
      (value "5.1")
      (footprint "6-0805_N")
      (description "Resistor")
      (fields (field (name "PUBLISHER") "Altium Limited"))
      (libsource (lib "Miscellaneous Devices") (part "Res3"))
    )
    (comp (ref "R62")
      (value "12")
      (footprint "6-0805_N")
      (description "Resistor")
      (fields (field (name "PUBLISHER") "Altium Limited"))
      (libsource (lib "Miscellaneous Devices") (part "Res3"))
    )
    (comp (ref "R63")
      (value "1.2k")
      (footprint "6-0805_N")
      (description "Resistor")
      (fields (field (name "PUBLISHER") "Altium Limited"))
      (libsource (lib "Miscellaneous Devices") (part "Res3"))
    )
    (comp (ref "R64")
      (value "330")
      (footprint "6-0805_N")
      (description "Resistor")
      (fields (field (name "PUBLISHER") "Altium Limited"))
      (libsource (lib "Miscellaneous Devices") (part "Res3"))
    )
    (comp (ref "R65")
      (value "4.22k")
      (footprint "6-0805_N")
      (description "Resistor")
      (fields (field (name "PUBLISHER") "Altium Limited"))
      (libsource (lib "Miscellaneous Devices") (part "Res3"))
    )
    (comp (ref "R66")
      (value "1.2k")
      (footprint "6-0805_N")
      (description "Resistor")
      (fields (field (name "PUBLISHER") "Altium Limited"))
      (libsource (lib "Miscellaneous Devices") (part "Res3"))
    )
    (comp (ref "R67")
      (value "4.22k")
      (footprint "6-0805_N")
      (description "Resistor")
      (fields (field (name "PUBLISHER") "Altium Limited"))
      (libsource (lib "Miscellaneous Devices") (part "Res3"))
    )
    (comp (ref "R68")
      (value "2.49k")
      (footprint "6-0805_N")
      (description "Resistor")
      (fields (field (name "PUBLISHER") "Altium Limited"))
      (libsource (lib "Miscellaneous Devices") (part "Res3"))
    )
    (comp (ref "R69")
      (value "1.02k")
      (footprint "6-0805_N")
      (description "Resistor")
      (fields (field (name "PUBLISHER") "Altium Limited"))
      (libsource (lib "Miscellaneous Devices") (part "Res3"))
    )
    (comp (ref "R70")
      (value "2.49k")
      (footprint "6-0805_N")
      (description "Resistor")
      (fields (field (name "PUBLISHER") "Altium Limited"))
      (libsource (lib "Miscellaneous Devices") (part "Res3"))
    )
    (comp (ref "R71")
      (value "1.02k")
      (footprint "6-0805_N")
      (description "Resistor")
      (fields (field (name "PUBLISHER") "Altium Limited"))
      (libsource (lib "Miscellaneous Devices") (part "Res3"))
    )
    (comp (ref "R72")
      (value "330")
      (footprint "6-0805_N")
      (description "Resistor")
      (fields (field (name "PUBLISHER") "Altium Limited"))
      (libsource (lib "Miscellaneous Devices") (part "Res3"))
    )
    (comp (ref "R73")
      (value "12")
      (footprint "6-0805_N")
      (description "Resistor")
      (fields (field (name "PUBLISHER") "Altium Limited"))
      (libsource (lib "Miscellaneous Devices") (part "Res3"))
    )
    (comp (ref "R74")
      (value "5.1")
      (footprint "6-0805_N")
      (description "Resistor")
      (fields (field (name "PUBLISHER") "Altium Limited"))
      (libsource (lib "Miscellaneous Devices") (part "Res3"))
    )
    (comp (ref "R75")
      (value "12.1k")
      (footprint "6-0805_N")
      (description "Resistor")
      (fields (field (name "PUBLISHER") "Altium Limited"))
      (libsource (lib "Miscellaneous Devices") (part "Res3"))
    )
    (comp (ref "R76")
      (value "3.57k")
      (footprint "6-0805_N")
      (description "Resistor")
      (fields (field (name "PUBLISHER") "Altium Limited"))
      (libsource (lib "Miscellaneous Devices") (part "Res3"))
    )
    (comp (ref "R77")
      (value "9.53k")
      (footprint "6-0805_N")
      (description "Resistor")
      (fields (field (name "PUBLISHER") "Altium Limited"))
      (libsource (lib "Miscellaneous Devices") (part "Res3"))
    )
    (comp (ref "R78")
      (value "10k")
      (footprint "6-0805_N")
      (description "Resistor")
      (fields (field (name "PUBLISHER") "Altium Limited"))
      (libsource (lib "Miscellaneous Devices") (part "Res3"))
    )
    (comp (ref "R79")
      (value "5.1")
      (footprint "6-0805_N")
      (description "Resistor")
      (fields (field (name "PUBLISHER") "Altium Limited"))
      (libsource (lib "Miscellaneous Devices") (part "Res3"))
    )
    (comp (ref "R80")
      (value "12")
      (footprint "6-0805_N")
      (description "Resistor")
      (fields (field (name "PUBLISHER") "Altium Limited"))
      (libsource (lib "Miscellaneous Devices") (part "Res3"))
    )
    (comp (ref "R81")
      (value "1.2k")
      (footprint "6-0805_N")
      (description "Resistor")
      (fields (field (name "PUBLISHER") "Altium Limited"))
      (libsource (lib "Miscellaneous Devices") (part "Res3"))
    )
    (comp (ref "R82")
      (value "330")
      (footprint "6-0805_N")
      (description "Resistor")
      (fields (field (name "PUBLISHER") "Altium Limited"))
      (libsource (lib "Miscellaneous Devices") (part "Res3"))
    )
    (comp (ref "R83")
      (value "4.22k")
      (footprint "6-0805_N")
      (description "Resistor")
      (fields (field (name "PUBLISHER") "Altium Limited"))
      (libsource (lib "Miscellaneous Devices") (part "Res3"))
    )
    (comp (ref "R84")
      (value "1.2k")
      (footprint "6-0805_N")
      (description "Resistor")
      (fields (field (name "PUBLISHER") "Altium Limited"))
      (libsource (lib "Miscellaneous Devices") (part "Res3"))
    )
    (comp (ref "R85")
      (value "4.22k")
      (footprint "6-0805_N")
      (description "Resistor")
      (fields (field (name "PUBLISHER") "Altium Limited"))
      (libsource (lib "Miscellaneous Devices") (part "Res3"))
    )
    (comp (ref "R86")
      (value "2.49k")
      (footprint "6-0805_N")
      (description "Resistor")
      (fields (field (name "PUBLISHER") "Altium Limited"))
      (libsource (lib "Miscellaneous Devices") (part "Res3"))
    )
    (comp (ref "R87")
      (value "1.02k")
      (footprint "6-0805_N")
      (description "Resistor")
      (fields (field (name "PUBLISHER") "Altium Limited"))
      (libsource (lib "Miscellaneous Devices") (part "Res3"))
    )
    (comp (ref "R88")
      (value "2.49k")
      (footprint "6-0805_N")
      (description "Resistor")
      (fields (field (name "PUBLISHER") "Altium Limited"))
      (libsource (lib "Miscellaneous Devices") (part "Res3"))
    )
    (comp (ref "R89")
      (value "1.02k")
      (footprint "6-0805_N")
      (description "Resistor")
      (fields (field (name "PUBLISHER") "Altium Limited"))
      (libsource (lib "Miscellaneous Devices") (part "Res3"))
    )
    (comp (ref "R90")
      (value "330")
      (footprint "6-0805_N")
      (description "Resistor")
      (fields (field (name "PUBLISHER") "Altium Limited"))
      (libsource (lib "Miscellaneous Devices") (part "Res3"))
    )
    (comp (ref "R91")
      (value "12")
      (footprint "6-0805_N")
      (description "Resistor")
      (fields (field (name "PUBLISHER") "Altium Limited"))
      (libsource (lib "Miscellaneous Devices") (part "Res3"))
    )
    (comp (ref "R92")
      (value "5.1")
      (footprint "6-0805_N")
      (description "Resistor")
      (fields (field (name "PUBLISHER") "Altium Limited"))
      (libsource (lib "Miscellaneous Devices") (part "Res3"))
    )
    (comp (ref "R93")
      (value "12.1k")
      (footprint "6-0805_N")
      (description "Resistor")
      (fields (field (name "PUBLISHER") "Altium Limited"))
      (libsource (lib "Miscellaneous Devices") (part "Res3"))
    )
    (comp (ref "R94")
      (value "3.57k")
      (footprint "6-0805_N")
      (description "Resistor")
      (fields (field (name "PUBLISHER") "Altium Limited"))
      (libsource (lib "Miscellaneous Devices") (part "Res3"))
    )
    (comp (ref "R95")
      (value "9.53k")
      (footprint "6-0805_N")
      (description "Resistor")
      (fields (field (name "PUBLISHER") "Altium Limited"))
      (libsource (lib "Miscellaneous Devices") (part "Res3"))
    )
    (comp (ref "R96")
      (value "10k")
      (footprint "6-0805_N")
      (description "Resistor")
      (fields (field (name "PUBLISHER") "Altium Limited"))
      (libsource (lib "Miscellaneous Devices") (part "Res3"))
    )
    (comp (ref "R97")
      (value "5.1")
      (footprint "6-0805_N")
      (description "Resistor")
      (fields (field (name "PUBLISHER") "Altium Limited"))
      (libsource (lib "Miscellaneous Devices") (part "Res3"))
    )
    (comp (ref "R98")
      (value "12")
      (footprint "6-0805_N")
      (description "Resistor")
      (fields (field (name "PUBLISHER") "Altium Limited"))
      (libsource (lib "Miscellaneous Devices") (part "Res3"))
    )
    (comp (ref "R99")
      (value "1.2k")
      (footprint "6-0805_N")
      (description "Resistor")
      (fields (field (name "PUBLISHER") "Altium Limited"))
      (libsource (lib "Miscellaneous Devices") (part "Res3"))
    )
    (comp (ref "R100")
      (value "330")
      (footprint "6-0805_N")
      (description "Resistor")
      (fields (field (name "PUBLISHER") "Altium Limited"))
      (libsource (lib "Miscellaneous Devices") (part "Res3"))
    )
    (comp (ref "R101")
      (value "4.22k")
      (footprint "6-0805_N")
      (description "Resistor")
      (fields (field (name "PUBLISHER") "Altium Limited"))
      (libsource (lib "Miscellaneous Devices") (part "Res3"))
    )
    (comp (ref "R102")
      (value "1.2k")
      (footprint "6-0805_N")
      (description "Resistor")
      (fields (field (name "PUBLISHER") "Altium Limited"))
      (libsource (lib "Miscellaneous Devices") (part "Res3"))
    )
    (comp (ref "R103")
      (value "4.22k")
      (footprint "6-0805_N")
      (description "Resistor")
      (fields (field (name "PUBLISHER") "Altium Limited"))
      (libsource (lib "Miscellaneous Devices") (part "Res3"))
    )
    (comp (ref "R104")
      (value "2.49k")
      (footprint "6-0805_N")
      (description "Resistor")
      (fields (field (name "PUBLISHER") "Altium Limited"))
      (libsource (lib "Miscellaneous Devices") (part "Res3"))
    )
    (comp (ref "R105")
      (value "1.02k")
      (footprint "6-0805_N")
      (description "Resistor")
      (fields (field (name "PUBLISHER") "Altium Limited"))
      (libsource (lib "Miscellaneous Devices") (part "Res3"))
    )
    (comp (ref "R106")
      (value "2.49k")
      (footprint "6-0805_N")
      (description "Resistor")
      (fields (field (name "PUBLISHER") "Altium Limited"))
      (libsource (lib "Miscellaneous Devices") (part "Res3"))
    )
    (comp (ref "R107")
      (value "1.02k")
      (footprint "6-0805_N")
      (description "Resistor")
      (fields (field (name "PUBLISHER") "Altium Limited"))
      (libsource (lib "Miscellaneous Devices") (part "Res3"))
    )
    (comp (ref "R108")
      (value "330")
      (footprint "6-0805_N")
      (description "Resistor")
      (fields (field (name "PUBLISHER") "Altium Limited"))
      (libsource (lib "Miscellaneous Devices") (part "Res3"))
    )
    (comp (ref "R109")
      (value "12")
      (footprint "6-0805_N")
      (description "Resistor")
      (fields (field (name "PUBLISHER") "Altium Limited"))
      (libsource (lib "Miscellaneous Devices") (part "Res3"))
    )
    (comp (ref "R110")
      (value "5.1")
      (footprint "6-0805_N")
      (description "Resistor")
      (fields (field (name "PUBLISHER") "Altium Limited"))
      (libsource (lib "Miscellaneous Devices") (part "Res3"))
    )
    (comp (ref "R111")
      (value "12.1k")
      (footprint "6-0805_N")
      (description "Resistor")
      (fields (field (name "PUBLISHER") "Altium Limited"))
      (libsource (lib "Miscellaneous Devices") (part "Res3"))
    )
    (comp (ref "R112")
      (value "3.57k")
      (footprint "6-0805_N")
      (description "Resistor")
      (fields (field (name "PUBLISHER") "Altium Limited"))
      (libsource (lib "Miscellaneous Devices") (part "Res3"))
    )
    (comp (ref "R113")
      (value "9.53k")
      (footprint "6-0805_N")
      (description "Resistor")
      (fields (field (name "PUBLISHER") "Altium Limited"))
      (libsource (lib "Miscellaneous Devices") (part "Res3"))
    )
    (comp (ref "R114")
      (value "10k")
      (footprint "6-0805_N")
      (description "Resistor")
      (fields (field (name "PUBLISHER") "Altium Limited"))
      (libsource (lib "Miscellaneous Devices") (part "Res3"))
    )
    (comp (ref "R115")
      (value "5.1")
      (footprint "6-0805_N")
      (description "Resistor")
      (fields (field (name "PUBLISHER") "Altium Limited"))
      (libsource (lib "Miscellaneous Devices") (part "Res3"))
    )
    (comp (ref "R116")
      (value "12")
      (footprint "6-0805_N")
      (description "Resistor")
      (fields (field (name "PUBLISHER") "Altium Limited"))
      (libsource (lib "Miscellaneous Devices") (part "Res3"))
    )
    (comp (ref "R117")
      (value "1.2k")
      (footprint "6-0805_N")
      (description "Resistor")
      (fields (field (name "PUBLISHER") "Altium Limited"))
      (libsource (lib "Miscellaneous Devices") (part "Res3"))
    )
    (comp (ref "R118")
      (value "330")
      (footprint "6-0805_N")
      (description "Resistor")
      (fields (field (name "PUBLISHER") "Altium Limited"))
      (libsource (lib "Miscellaneous Devices") (part "Res3"))
    )
    (comp (ref "R119")
      (value "4.22k")
      (footprint "6-0805_N")
      (description "Resistor")
      (fields (field (name "PUBLISHER") "Altium Limited"))
      (libsource (lib "Miscellaneous Devices") (part "Res3"))
    )
    (comp (ref "R120")
      (value "1M")
      (footprint "6-0805_N")
      (description "Resistor")
      (fields (field (name "PUBLISHER") "Altium Limited"))
      (libsource (lib "Miscellaneous Devices") (part "Res3"))
    )
    (comp (ref "R121")
      (value "820")
      (footprint "6-0805_N")
      (description "Resistor")
      (fields (field (name "PUBLISHER") "Altium Limited"))
      (libsource (lib "Miscellaneous Devices") (part "Res3"))
    )
    (comp (ref "R122")
      (value "100")
      (footprint "6-0805_N")
      (description "Resistor")
      (fields (field (name "PUBLISHER") "Altium Limited"))
      (libsource (lib "Miscellaneous Devices") (part "Res3"))
    )
    (comp (ref "R123")
      (value "4.7k")
      (footprint "6-0805_N")
      (description "Resistor")
      (fields (field (name "PUBLISHER") "Altium Limited"))
      (libsource (lib "Miscellaneous Devices") (part "Res3"))
    )
    (comp (ref "R124")
      (value "4.7k")
      (footprint "6-0805_N")
      (description "Resistor")
      (fields (field (name "PUBLISHER") "Altium Limited"))
      (libsource (lib "Miscellaneous Devices") (part "Res3"))
    )
    (comp (ref "R125")
      (value "33.2k")
      (footprint "6-0805_N")
      (description "Resistor")
      (fields (field (name "PUBLISHER") "Altium Limited"))
      (libsource (lib "Miscellaneous Devices") (part "Res3"))
    )
    (comp (ref "R126")
      (value "10k")
      (footprint "6-0805_N")
      (description "Resistor")
      (fields (field (name "PUBLISHER") "Altium Limited"))
      (libsource (lib "Miscellaneous Devices") (part "Res3"))
    )
    (comp (ref "R127")
      (value "10k")
      (footprint "6-0805_N")
      (description "Resistor")
      (fields (field (name "PUBLISHER") "Altium Limited"))
      (libsource (lib "Miscellaneous Devices") (part "Res3"))
    )
    (comp (ref "R128")
      (value "54.9k")
      (footprint "6-0805_N")
      (description "Resistor")
      (fields (field (name "PUBLISHER") "Altium Limited"))
      (libsource (lib "Miscellaneous Devices") (part "Res3"))
    )
    (comp (ref "R129")
      (value "820")
      (footprint "6-0805_N")
      (description "Resistor")
      (fields (field (name "PUBLISHER") "Altium Limited"))
      (libsource (lib "Miscellaneous Devices") (part "Res3"))
    )
    (comp (ref "R130")
      (value "2.2k")
      (footprint "6-0805_N")
      (description "Resistor")
      (fields (field (name "PUBLISHER") "Altium Limited"))
      (libsource (lib "Miscellaneous Devices") (part "Res3"))
    )
    (comp (ref "R131")
      (value "680")
      (footprint "6-0805_N")
      (description "Resistor")
      (fields (field (name "PUBLISHER") "Altium Limited"))
      (libsource (lib "Miscellaneous Devices") (part "Res3"))
    )
    (comp (ref "R132")
      (value "270")
      (footprint "6-0805_N")
      (description "Resistor")
      (fields (field (name "PUBLISHER") "Altium Limited"))
      (libsource (lib "Miscellaneous Devices") (part "Res3"))
    )
    (comp (ref "R133")
      (value "11k")
      (footprint "AXIAL-0.3")
      (description "Resistor")
      (fields (field (name "PUBLISHER") "Altium Limited"))
      (libsource (lib "Miscellaneous Devices") (part "Res3"))
    )
    (comp (ref "R134")
      (value "47k")
      (footprint "6-0805_N")
      (description "Resistor")
      (fields (field (name "PUBLISHER") "Altium Limited"))
      (libsource (lib "Miscellaneous Devices") (part "Res3"))
    )
    (comp (ref "R135")
      (value "47k")
      (footprint "6-0805_N")
      (description "Resistor")
      (fields (field (name "PUBLISHER") "Altium Limited"))
      (libsource (lib "Miscellaneous Devices") (part "Res3"))
    )
    (comp (ref "R136")
      (value "11k")
      (footprint "AXIAL-0.3")
      (description "Resistor")
      (fields (field (name "PUBLISHER") "Altium Limited"))
      (libsource (lib "Miscellaneous Devices") (part "Res3"))
    )
    (comp (ref "R137")
      (value "47k")
      (footprint "6-0805_N")
      (description "Resistor")
      (fields (field (name "PUBLISHER") "Altium Limited"))
      (libsource (lib "Miscellaneous Devices") (part "Res3"))
    )
    (comp (ref "R138")
      (value "47k")
      (footprint "6-0805_N")
      (description "Resistor")
      (fields (field (name "PUBLISHER") "Altium Limited"))
      (libsource (lib "Miscellaneous Devices") (part "Res3"))
    )
    (comp (ref "R139")
      (value "47k")
      (footprint "6-0805_N")
      (description "Resistor")
      (fields (field (name "PUBLISHER") "Altium Limited"))
      (libsource (lib "Miscellaneous Devices") (part "Res3"))
    )
    (comp (ref "R140")
      (value "2.2k")
      (footprint "6-0805_N")
      (description "Resistor")
      (fields (field (name "PUBLISHER") "Altium Limited"))
      (libsource (lib "Miscellaneous Devices") (part "Res3"))
    )
    (comp (ref "R141")
      (value "270")
      (footprint "6-0805_N")
      (description "Resistor")
      (fields (field (name "PUBLISHER") "Altium Limited"))
      (libsource (lib "Miscellaneous Devices") (part "Res3"))
    )
    (comp (ref "R142")
      (value "680")
      (footprint "6-0805_N")
      (description "Resistor")
      (fields (field (name "PUBLISHER") "Altium Limited"))
      (libsource (lib "Miscellaneous Devices") (part "Res3"))
    )
    (comp (ref "R143")
      (value "680")
      (footprint "6-0805_N")
      (description "Resistor")
      (fields (field (name "PUBLISHER") "Altium Limited"))
      (libsource (lib "Miscellaneous Devices") (part "Res3"))
    )
    (comp (ref "R144")
      (value "10k")
      (footprint "6-0805_N")
      (description "Resistor")
      (fields (field (name "PUBLISHER") "Altium Limited"))
      (libsource (lib "Miscellaneous Devices") (part "Res3"))
    )
    (comp (ref "R145")
      (value "10k")
      (footprint "6-0805_N")
      (description "Resistor")
      (fields (field (name "PUBLISHER") "Altium Limited"))
      (libsource (lib "Miscellaneous Devices") (part "Res3"))
    )
    (comp (ref "R146")
      (value "10k")
      (footprint "6-0805_N")
      (description "Resistor")
      (fields (field (name "PUBLISHER") "Altium Limited"))
      (libsource (lib "Miscellaneous Devices") (part "Res3"))
    )
    (comp (ref "R147")
      (value "2.2k")
      (footprint "6-0805_N")
      (description "Resistor")
      (fields (field (name "PUBLISHER") "Altium Limited"))
      (libsource (lib "Miscellaneous Devices") (part "Res3"))
    )
    (comp (ref "R148")
      (value "2.2k")
      (footprint "6-0805_N")
      (description "Resistor")
      (fields (field (name "PUBLISHER") "Altium Limited"))
      (libsource (lib "Miscellaneous Devices") (part "Res3"))
    )
    (comp (ref "RESET")
      (value "B3F-3152")
      (footprint "B3F-3152")
      (libsource (lib "Senior_SCH_Lib") (part "B3F-3152"))
    )
    (comp (ref "S1")
      (value "SW DIP-3")
      (footprint "Gull Wing Switch")
      (description "DIP Switch, 3 Position, SPST")
      (fields (field (name "PUBLISHER") "Altium Limited"))
      (libsource (lib "Miscellaneous Devices") (part "SW DIP-3"))
    )
    (comp (ref "TP1")
      (value "Test Point")
      (footprint "Test Point")
      (libsource (lib "Senior_SCH_Lib") (part "Test Point"))
    )
    (comp (ref "TP2")
      (value "Test Point")
      (footprint "Test Point")
      (libsource (lib "Senior_SCH_Lib") (part "Test Point"))
    )
    (comp (ref "TP3")
      (value "Test Point")
      (footprint "Test Point")
      (libsource (lib "Senior_SCH_Lib") (part "Test Point"))
    )
    (comp (ref "TP4")
      (value "Test Point")
      (footprint "Test Point")
      (libsource (lib "Senior_SCH_Lib") (part "Test Point"))
    )
    (comp (ref "TP5")
      (value "Test Point")
      (footprint "Test Point")
      (libsource (lib "Senior_SCH_Lib") (part "Test Point"))
    )
    (comp (ref "TP6")
      (value "Test Point")
      (footprint "Test Point")
      (libsource (lib "Senior_SCH_Lib") (part "Test Point"))
    )
    (comp (ref "TP7")
      (value "Test Point")
      (footprint "Test Point")
      (libsource (lib "Senior_SCH_Lib") (part "Test Point"))
    )
    (comp (ref "TP8")
      (value "Test Point")
      (footprint "Test Point")
      (libsource (lib "Senior_SCH_Lib") (part "Test Point"))
    )
    (comp (ref "TP9")
      (value "Test Point")
      (footprint "Test Point")
      (libsource (lib "Senior_SCH_Lib") (part "Test Point"))
    )
    (comp (ref "TP12")
      (value "Test Point")
      (footprint "Test Point")
      (libsource (lib "Senior_SCH_Lib") (part "Test Point"))
    )
    (comp (ref "TP13")
      (value "Test Point")
      (footprint "Test Point")
      (libsource (lib "Senior_SCH_Lib") (part "Test Point"))
    )
    (comp (ref "TP14")
      (value "Test Point")
      (footprint "Test Point")
      (libsource (lib "Senior_SCH_Lib") (part "Test Point"))
    )
    (comp (ref "TP17")
      (value "Test Point")
      (footprint "Test Point")
      (libsource (lib "Senior_SCH_Lib") (part "Test Point"))
    )
    (comp (ref "TP18")
      (value "Test Point")
      (footprint "Test Point")
      (libsource (lib "Senior_SCH_Lib") (part "Test Point"))
    )
    (comp (ref "TP21")
      (value "Test Point")
      (footprint "Test Point")
      (libsource (lib "Senior_SCH_Lib") (part "Test Point"))
    )
    (comp (ref "TP22")
      (value "Test Point")
      (footprint "Test Point")
      (libsource (lib "Senior_SCH_Lib") (part "Test Point"))
    )
    (comp (ref "TP23")
      (value "Test Point")
      (footprint "Test Point")
      (libsource (lib "Senior_SCH_Lib") (part "Test Point"))
    )
    (comp (ref "TP26")
      (value "Test Point")
      (footprint "Test Point")
      (libsource (lib "Senior_SCH_Lib") (part "Test Point"))
    )
    (comp (ref "TP27")
      (value "Test Point")
      (footprint "Test Point")
      (libsource (lib "Senior_SCH_Lib") (part "Test Point"))
    )
    (comp (ref "TP28")
      (value "Test Point")
      (footprint "Test Point")
      (libsource (lib "Senior_SCH_Lib") (part "Test Point"))
    )
    (comp (ref "TP29")
      (value "Test Point")
      (footprint "Test Point")
      (libsource (lib "Senior_SCH_Lib") (part "Test Point"))
    )
    (comp (ref "TP30")
      (value "Test Point")
      (footprint "Test Point")
      (libsource (lib "Senior_SCH_Lib") (part "Test Point"))
    )
    (comp (ref "TP32")
      (value "Test Point")
      (footprint "Test Point")
      (libsource (lib "Senior_SCH_Lib") (part "Test Point"))
    )
    (comp (ref "TP33")
      (value "Test Point")
      (footprint "Test Point")
      (libsource (lib "Senior_SCH_Lib") (part "Test Point"))
    )
    (comp (ref "TP34")
      (value "Test Point")
      (footprint "Test Point")
      (libsource (lib "Senior_SCH_Lib") (part "Test Point"))
    )
    (comp (ref "TP35")
      (value "Test Point")
      (footprint "Test Point")
      (libsource (lib "Senior_SCH_Lib") (part "Test Point"))
    )
    (comp (ref "TP36")
      (value "Test Point")
      (footprint "Test Point")
      (libsource (lib "Senior_SCH_Lib") (part "Test Point"))
    )
    (comp (ref "TP39")
      (value "Test Point")
      (footprint "Test Point")
      (libsource (lib "Senior_SCH_Lib") (part "Test Point"))
    )
    (comp (ref "TP40")
      (value "Test Point")
      (footprint "Test Point")
      (libsource (lib "Senior_SCH_Lib") (part "Test Point"))
    )
    (comp (ref "TP41")
      (value "Test Point")
      (footprint "Test Point")
      (libsource (lib "Senior_SCH_Lib") (part "Test Point"))
    )
    (comp (ref "Transceiver Out")
      (value "SN65LVDT41")
      (footprint "SN65LVDT41")
      (libsource (lib "Senior_SCH_Lib") (part "SN65LVDT41"))
    )
    (comp (ref "U1")
      (value "NE5532P")
      (footprint "TI-P8")
      (fields (field (name "MANUFACTURER") "Texas Instruments"))
      (libsource (lib "TI Amplifiers and Linear Operational Amplifier General Purpose") (part "NE5532P"))
    )
    (comp (ref "U2")
      (value "TPS63710DRR")
      (footprint "DRR0012C")
      (description "Imported")
      (fields (field (name "MANUFACTURER") "Texas Instruments"))
      (libsource (lib "Senior_SCH_Lib") (part "TPS63710DRR"))
    )
    (comp (ref "U3")
      (value "OPA350EA/250")
      (footprint "TI-DGK8_N")
      (fields (field (name "MANUFACTURER") "Texas Instruments"))
      (libsource (lib "TI Amplifiers and Linear Operational Amplifier Precision Amplifier Part One") (part "OPA350EA/250"))
    )
    (comp (ref "U4")
      (value "REF5030IDGKT")
      (footprint "TI-DGK8_N")
      (fields (field (name "MANUFACTURER") "Texas Instruments"))
      (libsource (lib "TI Power Management Series Voltage Reference") (part "REF5030IDGKT"))
    )
    (comp (ref "U5")
      (value "OPA350EA/250")
      (footprint "TI-DGK8_N")
      (fields (field (name "MANUFACTURER") "Texas Instruments"))
      (libsource (lib "TI Amplifiers and Linear Operational Amplifier Precision Amplifier Part One") (part "OPA350EA/250"))
    )
    (comp (ref "U6")
      (value "THS4531IDGKR")
      (footprint "TI-DGK8_N")
      (fields (field (name "MANUFACTURER") "Texas Instruments"))
      (libsource (lib "TI Amplifiers and Linear Operational Amplifier Fully Differential Amplifier") (part "THS4531IDGKR"))
    )
    (comp (ref "U7")
      (value "NE5532P")
      (footprint "TI-P8")
      (fields (field (name "MANUFACTURER") "Texas Instruments"))
      (libsource (lib "TI Amplifiers and Linear Operational Amplifier General Purpose") (part "NE5532P"))
    )
    (comp (ref "U8")
      (value "THS4531IDGKR")
      (footprint "TI-DGK8_N")
      (fields (field (name "MANUFACTURER") "Texas Instruments"))
      (libsource (lib "TI Amplifiers and Linear Operational Amplifier Fully Differential Amplifier") (part "THS4531IDGKR"))
    )
    (comp (ref "U9")
      (value "NE5532P")
      (footprint "TI-P8")
      (fields (field (name "MANUFACTURER") "Texas Instruments"))
      (libsource (lib "") (part "NE5532P_1"))
    )
    (comp (ref "U10")
      (value "THS4531IDGKR")
      (footprint "TI-DGK8_N")
      (fields (field (name "MANUFACTURER") "Texas Instruments"))
      (libsource (lib "TI Amplifiers and Linear Operational Amplifier Fully Differential Amplifier") (part "THS4531IDGKR"))
    )
    (comp (ref "U11")
      (value "NE5532P")
      (footprint "TI-P8")
      (fields (field (name "MANUFACTURER") "Texas Instruments"))
      (libsource (lib "TI Amplifiers and Linear Operational Amplifier General Purpose") (part "NE5532P"))
    )
    (comp (ref "U12")
      (value "NE5532P")
      (footprint "TI-P8")
      (fields (field (name "MANUFACTURER") "Texas Instruments"))
      (libsource (lib "TI Amplifiers and Linear Operational Amplifier General Purpose") (part "NE5532P"))
    )
    (comp (ref "U13")
      (value "THS4531IDGKR")
      (footprint "TI-DGK8_N")
      (fields (field (name "MANUFACTURER") "Texas Instruments"))
      (libsource (lib "TI Amplifiers and Linear Operational Amplifier Fully Differential Amplifier") (part "THS4531IDGKR"))
    )
    (comp (ref "U14")
      (value "NE5532P")
      (footprint "TI-P8")
      (fields (field (name "MANUFACTURER") "Texas Instruments"))
      (libsource (lib "") (part "NE5532P_1"))
    )
    (comp (ref "U15")
      (value "THS4531IDGKR")
      (footprint "TI-DGK8_N")
      (fields (field (name "MANUFACTURER") "Texas Instruments"))
      (libsource (lib "TI Amplifiers and Linear Operational Amplifier Fully Differential Amplifier") (part "THS4531IDGKR"))
    )
    (comp (ref "U16")
      (value "NE5532P")
      (footprint "TI-P8")
      (fields (field (name "MANUFACTURER") "Texas Instruments"))
      (libsource (lib "TI Amplifiers and Linear Operational Amplifier General Purpose") (part "NE5532P"))
    )
    (comp (ref "U17")
      (value "THS4531IDGKR")
      (footprint "TI-DGK8_N")
      (fields (field (name "MANUFACTURER") "Texas Instruments"))
      (libsource (lib "TI Amplifiers and Linear Operational Amplifier Fully Differential Amplifier") (part "THS4531IDGKR"))
    )
    (comp (ref "U18")
      (value "NE5532P")
      (footprint "TI-P8")
      (fields (field (name "MANUFACTURER") "Texas Instruments"))
      (libsource (lib "TI Amplifiers and Linear Operational Amplifier General Purpose") (part "NE5532P"))
    )
    (comp (ref "U19")
      (value "TMS320F28379DPTP")
      (footprint "PTP0176F_N")
      (description "Imported")
      (fields
        (field (name "PARTNUMBER") "TMS320F28379DPTPS")
        (field (name "MANUFACTURER") "Texas Instruments")
      )
      (libsource (lib "Senior_SCH_Lib") (part "TMS320F28379DPTP"))
    )
    (comp (ref "U20")
      (value "NE5532P")
      (footprint "TI-P8")
      (fields (field (name "MANUFACTURER") "Texas Instruments"))
      (libsource (lib "TI Amplifiers and Linear Operational Amplifier General Purpose") (part "NE5532P"))
    )
    (comp (ref "U21")
      (value "TPS563200DDCR")
      (footprint "DDC0006A")
      (description "17 V Input, 3A Synchronous Step-Down Regulator in SOT-23 with Advanced Eco-mode? 6-SOT -40 to 85")
      (fields (field (name "DIGI-KEY_PART_NUMBER") "296-43663-1-ND") (field (name "MF") "Texas Instruments"))
      (libsource (lib "TPS563200DDCR") (part "TPS563200DDCR"))
    )
    (comp (ref "U22")
      (value "TPS563200DDCR")
      (footprint "DDC0006A")
      (description "17 V Input, 3A Synchronous Step-Down Regulator in SOT-23 with Advanced Eco-mode? 6-SOT -40 to 85")
      (fields (field (name "DIGI-KEY_PART_NUMBER") "296-43663-1-ND") (field (name "MF") "Texas Instruments"))
      (libsource (lib "TPS563200DDCR") (part "TPS563200DDCR"))
    )
    (comp (ref "U24")
      (value "TPS561208DDCR")
      (footprint "DDC0006A")
      (description "Imported")
      (fields (field (name "MANUFACTURER") "Texas Instruments"))
      (libsource (lib "1_2V_Supply") (part "TPS561208DDCR"))
    )
    (comp (ref "U25")
      (value "NE5532P")
      (footprint "TI-P8")
      (fields (field (name "MANUFACTURER") "Texas Instruments"))
      (libsource (lib "") (part "NE5532P_2"))
    )
    (comp (ref "XTALA")
      (value "ATS100B-E")
      (footprint "ATS XTAL")
      (libsource (lib "Senior_SCH_Lib") (part "ATS100B-E"))
    )
  )
  (nets
    (net (code "1") (name "+1V2") (class "Default")
      (node (ref "+1V2J") (pin "2") (pinfunction "2_2") (pintype "passive"))
      (node (ref "C26") (pin "1") (pinfunction "1_1") (pintype "passive"))
      (node (ref "C27") (pin "1") (pinfunction "1_1") (pintype "passive"))
      (node (ref "C28") (pin "1") (pinfunction "1_1") (pintype "passive"))
      (node (ref "C29") (pin "1") (pinfunction "1_1") (pintype "passive"))
      (node (ref "C30") (pin "1") (pinfunction "1_1") (pintype "passive"))
      (node (ref "C31") (pin "1") (pinfunction "1_1") (pintype "passive"))
      (node (ref "C32") (pin "1") (pinfunction "1_1") (pintype "passive"))
      (node (ref "C33") (pin "1") (pinfunction "1_1") (pintype "passive"))
      (node (ref "C34") (pin "1") (pinfunction "1_1") (pintype "passive"))
      (node (ref "C35") (pin "1") (pinfunction "1_1") (pintype "passive"))
      (node (ref "U19") (pin "117") (pinfunction "VDD_117") (pintype "power_in"))
      (node (ref "U19") (pin "126") (pinfunction "VDD_126") (pintype "power_in"))
      (node (ref "U19") (pin "137") (pinfunction "VDD_137") (pintype "power_in"))
      (node (ref "U19") (pin "153") (pinfunction "VDD_153") (pintype "power_in"))
      (node (ref "U19") (pin "158") (pinfunction "VDD_158") (pintype "power_in"))
      (node (ref "U19") (pin "16") (pinfunction "VDD_16") (pintype "power_in"))
      (node (ref "U19") (pin "169") (pinfunction "VDD_169") (pintype "power_in"))
      (node (ref "U19") (pin "21") (pinfunction "VDD_21") (pintype "power_in"))
      (node (ref "U19") (pin "61") (pinfunction "VDD_61") (pintype "power_in"))
      (node (ref "U19") (pin "76") (pinfunction "VDD_76") (pintype "power_in"))
    )
    (net (code "2") (name "+3V3") (class "Default")
      (node (ref "+3V3J") (pin "2") (pinfunction "2_2") (pintype "passive"))
      (node (ref "C1") (pin "1") (pinfunction "1_1") (pintype "passive"))
      (node (ref "C10") (pin "1") (pinfunction "1_1") (pintype "passive"))
      (node (ref "C102") (pin "1") (pinfunction "1_1") (pintype "passive"))
      (node (ref "C103") (pin "1") (pinfunction "1_1") (pintype "passive"))
      (node (ref "C11") (pin "1") (pinfunction "1_1") (pintype "passive"))
      (node (ref "C112") (pin "1") (pinfunction "1_1") (pintype "passive"))
      (node (ref "C115") (pin "1") (pinfunction "1_1") (pintype "passive"))
      (node (ref "C12") (pin "1") (pinfunction "1_1") (pintype "passive"))
      (node (ref "C125") (pin "1") (pinfunction "1_1") (pintype "passive"))
      (node (ref "C13") (pin "1") (pinfunction "1_1") (pintype "passive"))
      (node (ref "C134") (pin "2") (pinfunction "2_2") (pintype "passive"))
      (node (ref "C14") (pin "1") (pinfunction "1_1") (pintype "passive"))
      (node (ref "C15") (pin "1") (pinfunction "1_1") (pintype "passive"))
      (node (ref "C17") (pin "1") (pinfunction "1_1") (pintype "passive"))
      (node (ref "C18") (pin "1") (pinfunction "1_1") (pintype "passive"))
      (node (ref "C19") (pin "1") (pinfunction "1_1") (pintype "passive"))
      (node (ref "C2") (pin "1") (pinfunction "1_1") (pintype "passive"))
      (node (ref "C20") (pin "1") (pinfunction "1_1") (pintype "passive"))
      (node (ref "C21") (pin "1") (pinfunction "1_1") (pintype "passive"))
      (node (ref "C22") (pin "1") (pinfunction "1_1") (pintype "passive"))
      (node (ref "C23") (pin "1") (pinfunction "1_1") (pintype "passive"))
      (node (ref "C24") (pin "1") (pinfunction "1_1") (pintype "passive"))
      (node (ref "C3") (pin "1") (pinfunction "1_1") (pintype "passive"))
      (node (ref "C36") (pin "1") (pinfunction "1_1") (pintype "passive"))
      (node (ref "C4") (pin "1") (pinfunction "1_1") (pintype "passive"))
      (node (ref "C5") (pin "1") (pinfunction "1_1") (pintype "passive"))
      (node (ref "C56") (pin "1") (pinfunction "1_1") (pintype "passive"))
      (node (ref "C6") (pin "1") (pinfunction "1_1") (pintype "passive"))
      (node (ref "C62") (pin "1") (pinfunction "1_1") (pintype "passive"))
      (node (ref "C63") (pin "1") (pinfunction "1_1") (pintype "passive"))
      (node (ref "C7") (pin "1") (pinfunction "1_1") (pintype "passive"))
      (node (ref "C73") (pin "1") (pinfunction "1_1") (pintype "passive"))
      (node (ref "C76") (pin "1") (pinfunction "1_1") (pintype "passive"))
      (node (ref "C8") (pin "1") (pinfunction "1_1") (pintype "passive"))
      (node (ref "C86") (pin "1") (pinfunction "1_1") (pintype "passive"))
      (node (ref "C89") (pin "1") (pinfunction "1_1") (pintype "passive"))
      (node (ref "C9") (pin "1") (pinfunction "1_1") (pintype "passive"))
      (node (ref "C98") (pin "1") (pinfunction "1_1") (pintype "passive"))
      (node (ref "C99") (pin "1") (pinfunction "1_1") (pintype "passive"))
      (node (ref "R121") (pin "2") (pinfunction "2_2") (pintype "passive"))
      (node (ref "R122") (pin "1") (pinfunction "1_1") (pintype "passive"))
      (node (ref "R123") (pin "1") (pinfunction "1_1") (pintype "passive"))
      (node (ref "R124") (pin "1") (pinfunction "1_1") (pintype "passive"))
      (node (ref "R129") (pin "2") (pinfunction "2_2") (pintype "passive"))
      (node (ref "R131") (pin "2") (pinfunction "2_2") (pintype "passive"))
      (node (ref "R140") (pin "2") (pinfunction "2_2") (pintype "passive"))
      (node (ref "Transceiver Out") (pin "4") (pinfunction "VCC_4") (pintype "power_in"))
      (node (ref "Transceiver Out") (pin "8") (pinfunction "VCC_8") (pintype "power_in"))
      (node (ref "U10") (pin "3") (pinfunction "VS+_3") (pintype "power_in"))
      (node (ref "U10") (pin "7") (pinfunction "~{PD}_7") (pintype "input"))
      (node (ref "U13") (pin "3") (pinfunction "VS+_3") (pintype "power_in"))
      (node (ref "U13") (pin "7") (pinfunction "~{PD}_7") (pintype "input"))
      (node (ref "U15") (pin "3") (pinfunction "VS+_3") (pintype "power_in"))
      (node (ref "U15") (pin "7") (pinfunction "~{PD}_7") (pintype "input"))
      (node (ref "U17") (pin "3") (pinfunction "VS+_3") (pintype "power_in"))
      (node (ref "U17") (pin "7") (pinfunction "~{PD}_7") (pintype "input"))
      (node (ref "U19") (pin "106") (pinfunction "VDDIO_106") (pintype "power_in"))
      (node (ref "U19") (pin "11") (pinfunction "VDDIO_11") (pintype "power_in"))
      (node (ref "U19") (pin "114") (pinfunction "VDDIO_114") (pintype "power_in"))
      (node (ref "U19") (pin "116") (pinfunction "VDDIO_116") (pintype "power_in"))
      (node (ref "U19") (pin "119") (pinfunction "VREGENZ_119") (pintype "input"))
      (node (ref "U19") (pin "120") (pinfunction "VDDOSC_120") (pintype "power_in"))
      (node (ref "U19") (pin "125") (pinfunction "VDDOSC_125") (pintype "power_in"))
      (node (ref "U19") (pin "127") (pinfunction "VDDIO_127") (pintype "power_in"))
      (node (ref "U19") (pin "138") (pinfunction "VDDIO_138") (pintype "power_in"))
      (node (ref "U19") (pin "147") (pinfunction "VDDIO_147") (pintype "power_in"))
      (node (ref "U19") (pin "15") (pinfunction "VDDIO_15") (pintype "power_in"))
      (node (ref "U19") (pin "152") (pinfunction "VDDIO_152") (pintype "power_in"))
      (node (ref "U19") (pin "159") (pinfunction "VDDIO_159") (pintype "power_in"))
      (node (ref "U19") (pin "168") (pinfunction "VDDIO_168") (pintype "power_in"))
      (node (ref "U19") (pin "20") (pinfunction "VDDIO_20") (pintype "power_in"))
      (node (ref "U19") (pin "26") (pinfunction "VDDIO_26") (pintype "power_in"))
      (node (ref "U19") (pin "3") (pinfunction "VDDIO_3") (pintype "power_in"))
      (node (ref "U19") (pin "36") (pinfunction "VDDA_36") (pintype "power_in"))
      (node (ref "U19") (pin "54") (pinfunction "VDDA_54") (pintype "power_in"))
      (node (ref "U19") (pin "62") (pinfunction "VDDIO_62") (pintype "power_in"))
      (node (ref "U19") (pin "68") (pinfunction "VDDIO_68") (pintype "power_in"))
      (node (ref "U19") (pin "72") (pinfunction "VDD3VFL_72") (pintype "power_in"))
      (node (ref "U19") (pin "75") (pinfunction "VDDIO_75") (pintype "power_in"))
      (node (ref "U19") (pin "82") (pinfunction "VDDIO_82") (pintype "power_in"))
      (node (ref "U19") (pin "88") (pinfunction "VDDIO_88") (pintype "power_in"))
      (node (ref "U19") (pin "91") (pinfunction "VDDIO_91") (pintype "power_in"))
      (node (ref "U19") (pin "99") (pinfunction "VDDIO_99") (pintype "power_in"))
      (node (ref "U6") (pin "3") (pinfunction "VS+_3") (pintype "power_in"))
      (node (ref "U6") (pin "7") (pinfunction "~{PD}_7") (pintype "input"))
      (node (ref "U8") (pin "3") (pinfunction "VS+_3") (pintype "power_in"))
      (node (ref "U8") (pin "7") (pinfunction "~{PD}_7") (pintype "input"))
    )
    (net (code "3") (name "+5V") (class "Default")
      (node (ref "+5J") (pin "2") (pinfunction "2_2") (pintype "passive"))
      (node (ref "C104") (pin "1") (pinfunction "1_1") (pintype "passive"))
      (node (ref "C117") (pin "1") (pinfunction "1_1") (pintype "passive"))
      (node (ref "C152") (pin "1") (pinfunction "1_1") (pintype "passive"))
      (node (ref "C37") (pin "1") (pinfunction "1_1") (pintype "passive"))
      (node (ref "C38") (pin "1") (pinfunction "1_1") (pintype "passive"))
      (node (ref "C39") (pin "1") (pinfunction "1_1") (pintype "passive"))
      (node (ref "C45") (pin "1") (pinfunction "1_1") (pintype "passive"))
      (node (ref "C58") (pin "1") (pinfunction "1_1") (pintype "passive"))
      (node (ref "C61") (pin "1") (pinfunction "1_1") (pintype "passive"))
      (node (ref "C64") (pin "1") (pinfunction "1_1") (pintype "passive"))
      (node (ref "C65") (pin "1") (pinfunction "1_1") (pintype "passive"))
      (node (ref "C78") (pin "1") (pinfunction "1_1") (pintype "passive"))
      (node (ref "C85") (pin "1") (pinfunction "1_1") (pintype "passive"))
      (node (ref "C91") (pin "1") (pinfunction "1_1") (pintype "passive"))
      (node (ref "U1") (pin "8") (pinfunction "VCC+_8") (pintype "power_in"))
      (node (ref "U11") (pin "8") (pinfunction "VCC+_8") (pintype "power_in"))
      (node (ref "U12") (pin "8") (pinfunction "VCC+_8") (pintype "power_in"))
      (node (ref "U14") (pin "8") (pinfunction "VCC+_8") (pintype "power_in"))
      (node (ref "U16") (pin "8") (pinfunction "VCC+_8") (pintype "power_in"))
      (node (ref "U18") (pin "8") (pinfunction "VCC+_8") (pintype "power_in"))
      (node (ref "U20") (pin "8") (pinfunction "VCC+_8") (pintype "power_in"))
      (node (ref "U25") (pin "8") (pinfunction "VCC+_8") (pintype "power_in"))
      (node (ref "U3") (pin "7") (pinfunction "V+_7") (pintype "power_in"))
      (node (ref "U4") (pin "2") (pinfunction "VIN_2") (pintype "power_in"))
      (node (ref "U5") (pin "7") (pinfunction "V+_7") (pintype "power_in"))
      (node (ref "U7") (pin "8") (pinfunction "VCC+_8") (pintype "power_in"))
      (node (ref "U9") (pin "8") (pinfunction "VCC+_8") (pintype "power_in"))
    )
    (net (code "4") (name "+12V") (class "Default")
      (node (ref "12V AGND") (pin "1") (pinfunction "1_1") (pintype "passive"))
      (node (ref "12V AGND") (pin "2") (pinfunction "2_2") (pintype "passive"))
      (node (ref "12V AGND") (pin "3") (pinfunction "3_3") (pintype "passive"))
      (node (ref "8-Pin DIN") (pin "10") (pinfunction "CH5_10") (pintype "passive"))
      (node (ref "C111") (pin "2") (pinfunction "2_2") (pintype "passive"))
      (node (ref "C116") (pin "2") (pinfunction "2_2") (pintype "passive"))
      (node (ref "C124") (pin "1") (pinfunction "1_1") (pintype "passive"))
      (node (ref "C124") (pin "2") (pinfunction "2_2") (pintype "passive"))
      (node (ref "C137") (pin "2") (pinfunction "2_2") (pintype "passive"))
      (node (ref "C138") (pin "2") (pinfunction "2_2") (pintype "passive"))
      (node (ref "C139") (pin "2") (pinfunction "2_2") (pintype "passive"))
      (node (ref "C142") (pin "2") (pinfunction "2_2") (pintype "passive"))
      (node (ref "C143") (pin "2") (pinfunction "2_2") (pintype "passive"))
      (node (ref "C146") (pin "2") (pinfunction "2_2") (pintype "passive"))
      (node (ref "C148") (pin "2") (pinfunction "2_2") (pintype "passive"))
      (node (ref "C149") (pin "2") (pinfunction "2_2") (pintype "passive"))
      (node (ref "C164") (pin "2") (pinfunction "2_2") (pintype "passive"))
      (node (ref "C167") (pin "2") (pinfunction "2_2") (pintype "passive"))
      (node (ref "C168") (pin "2") (pinfunction "2_2") (pintype "passive"))
      (node (ref "C49") (pin "1") (pinfunction "1_1") (pintype "passive"))
      (node (ref "Foot Switch") (pin "3") (pinfunction "Output2_3") (pintype "passive"))
      (node (ref "R127") (pin "2") (pinfunction "2_2") (pintype "passive"))
      (node (ref "R144") (pin "2") (pinfunction "2_2") (pintype "passive"))
      (node (ref "R146") (pin "2") (pinfunction "2_2") (pintype "passive"))
      (node (ref "TP27") (pin "TP") (pinfunction "Test_Point_TP") (pintype "passive"))
      (node (ref "U2") (pin "12") (pinfunction "VIN_12") (pintype "power_in"))
      (node (ref "U2") (pin "2") (pinfunction "EN_2") (pintype "input"))
      (node (ref "U21") (pin "3") (pinfunction "VIN_3") (pintype "input"))
      (node (ref "U22") (pin "3") (pinfunction "VIN_3") (pintype "input"))
      (node (ref "U24") (pin "3") (pinfunction "VIN_3") (pintype "power_in"))
    )
    (net (code "5") (name "-5V") (class "Default")
      (node (ref "-5VJ") (pin "2") (pinfunction "2_2") (pintype "passive"))
      (node (ref "C110") (pin "1") (pinfunction "1_1") (pintype "passive"))
      (node (ref "C123") (pin "1") (pinfunction "1_1") (pintype "passive"))
      (node (ref "C156") (pin "1") (pinfunction "1_1") (pintype "passive"))
      (node (ref "C60") (pin "1") (pinfunction "1_1") (pintype "passive"))
      (node (ref "C71") (pin "1") (pinfunction "1_1") (pintype "passive"))
      (node (ref "C72") (pin "1") (pinfunction "1_1") (pintype "passive"))
      (node (ref "C77") (pin "1") (pinfunction "1_1") (pintype "passive"))
      (node (ref "C84") (pin "1") (pinfunction "1_1") (pintype "passive"))
      (node (ref "C90") (pin "1") (pinfunction "1_1") (pintype "passive"))
      (node (ref "C97") (pin "1") (pinfunction "1_1") (pintype "passive"))
      (node (ref "U1") (pin "4") (pinfunction "VCC-_4") (pintype "power_in"))
      (node (ref "U11") (pin "4") (pinfunction "VCC-_4") (pintype "power_in"))
      (node (ref "U12") (pin "4") (pinfunction "VCC-_4") (pintype "power_in"))
      (node (ref "U14") (pin "4") (pinfunction "VCC-_4") (pintype "power_in"))
      (node (ref "U16") (pin "4") (pinfunction "VCC-_4") (pintype "power_in"))
      (node (ref "U18") (pin "4") (pinfunction "VCC-_4") (pintype "power_in"))
      (node (ref "U20") (pin "4") (pinfunction "VCC-_4") (pintype "power_in"))
      (node (ref "U25") (pin "4") (pinfunction "VCC-_4") (pintype "power_in"))
      (node (ref "U7") (pin "4") (pinfunction "VCC-_4") (pintype "power_in"))
      (node (ref "U9") (pin "4") (pinfunction "VCC-_4") (pintype "power_in"))
    )
    (net (code "6") (name "/AIN1") (class "Default")
      (node (ref "C150") (pin "1") (pinfunction "1_1") (pintype "passive"))
      (node (ref "R21") (pin "1") (pinfunction "1_1") (pintype "passive"))
      (node (ref "TP14") (pin "TP") (pinfunction "Test_Point_TP") (pintype "passive"))
      (node (ref "U16") (pin "6") (pinfunction "IN2-_6") (pintype "input"))
      (node (ref "U16") (pin "7") (pinfunction "OUT2_7") (pintype "output"))
    )
    (net (code "7") (name "/AIN1N") (class "Default")
      (node (ref "C51") (pin "2") (pinfunction "2_2") (pintype "passive"))
      (node (ref "R24") (pin "2") (pinfunction "2_2") (pintype "passive"))
      (node (ref "U19") (pin "59") (pinfunction "ADCIND3_59") (pintype "input"))
    )
    (net (code "8") (name "/AIN1P") (class "Default")
      (node (ref "C51") (pin "1") (pinfunction "1_1") (pintype "passive"))
      (node (ref "R17") (pin "2") (pinfunction "2_2") (pintype "passive"))
      (node (ref "U19") (pin "58") (pinfunction "ADCIND2_58") (pintype "input"))
    )
    (net (code "9") (name "/AIN1_Pre") (class "Default")
      (node (ref "8-Pin DIN") (pin "9") (pinfunction "CH1_9") (pintype "passive"))
      (node (ref "TP7") (pin "TP") (pinfunction "Test_Point_TP") (pintype "passive"))
      (node (ref "U16") (pin "5") (pinfunction "IN2+_5") (pintype "input"))
    )
    (net (code "10") (name "/AIN2") (class "Default")
      (node (ref "C151") (pin "1") (pinfunction "1_1") (pintype "passive"))
      (node (ref "R41") (pin "1") (pinfunction "1_1") (pintype "passive"))
      (node (ref "TP41") (pin "TP") (pinfunction "Test_Point_TP") (pintype "passive"))
      (node (ref "U16") (pin "1") (pinfunction "OUT1_1") (pintype "output"))
      (node (ref "U16") (pin "2") (pinfunction "IN1-_2") (pintype "input"))
    )
    (net (code "11") (name "/AIN2N") (class "Default")
      (node (ref "C68") (pin "2") (pinfunction "2_2") (pintype "passive"))
      (node (ref "R44") (pin "2") (pinfunction "2_2") (pintype "passive"))
      (node (ref "U19") (pin "42") (pinfunction "ADCINA1_42") (pintype "input"))
    )
    (net (code "12") (name "/AIN2P") (class "Default")
      (node (ref "C68") (pin "1") (pinfunction "1_1") (pintype "passive"))
      (node (ref "R37") (pin "2") (pinfunction "2_2") (pintype "passive"))
      (node (ref "U19") (pin "43") (pinfunction "ADCINA0_43") (pintype "input"))
    )
    (net (code "13") (name "/AIN2_Pre") (class "Default")
      (node (ref "8-Pin DIN") (pin "5") (pinfunction "CH2_5") (pintype "passive"))
      (node (ref "TP6") (pin "TP") (pinfunction "Test_Point_TP") (pintype "passive"))
      (node (ref "U16") (pin "3") (pinfunction "IN1+_3") (pintype "input"))
    )
    (net (code "14") (name "/AIN3") (class "Default")
      (node (ref "C153") (pin "1") (pinfunction "1_1") (pintype "passive"))
      (node (ref "R59") (pin "1") (pinfunction "1_1") (pintype "passive"))
      (node (ref "TP9") (pin "TP") (pinfunction "Test_Point_TP") (pintype "passive"))
      (node (ref "U18") (pin "6") (pinfunction "IN2-_6") (pintype "input"))
      (node (ref "U18") (pin "7") (pinfunction "OUT2_7") (pintype "output"))
    )
    (net (code "15") (name "/AIN3N") (class "Default")
      (node (ref "C81") (pin "2") (pinfunction "2_2") (pintype "passive"))
      (node (ref "R62") (pin "2") (pinfunction "2_2") (pintype "passive"))
      (node (ref "U19") (pin "57") (pinfunction "ADCIND1_57") (pintype "input"))
    )
    (net (code "16") (name "/AIN3P") (class "Default")
      (node (ref "C81") (pin "1") (pinfunction "1_1") (pintype "passive"))
      (node (ref "R55") (pin "2") (pinfunction "2_2") (pintype "passive"))
      (node (ref "U19") (pin "56") (pinfunction "ADCIND0_56") (pintype "input"))
    )
    (net (code "17") (name "/AIN3_Pre") (class "Default")
      (node (ref "8-Pin DIN") (pin "8") (pinfunction "CH3_8") (pintype "passive"))
      (node (ref "TP5") (pin "TP") (pinfunction "Test_Point_TP") (pintype "passive"))
      (node (ref "U18") (pin "5") (pinfunction "IN2+_5") (pintype "input"))
    )
    (net (code "18") (name "/AIN4") (class "Default")
      (node (ref "C155") (pin "1") (pinfunction "1_1") (pintype "passive"))
      (node (ref "R77") (pin "1") (pinfunction "1_1") (pintype "passive"))
      (node (ref "TP8") (pin "TP") (pinfunction "Test_Point_TP") (pintype "passive"))
      (node (ref "U18") (pin "1") (pinfunction "OUT1_1") (pintype "output"))
      (node (ref "U18") (pin "2") (pinfunction "IN1-_2") (pintype "input"))
    )
    (net (code "19") (name "/AIN4N") (class "Default")
      (node (ref "C94") (pin "2") (pinfunction "2_2") (pintype "passive"))
      (node (ref "R80") (pin "2") (pinfunction "2_2") (pintype "passive"))
      (node (ref "U19") (pin "40") (pinfunction "ADCINA3_40") (pintype "input"))
    )
    (net (code "20") (name "/AIN4P") (class "Default")
      (node (ref "C94") (pin "1") (pinfunction "1_1") (pintype "passive"))
      (node (ref "R73") (pin "2") (pinfunction "2_2") (pintype "passive"))
      (node (ref "U19") (pin "41") (pinfunction "ADCINA2_41") (pintype "input"))
    )
    (net (code "21") (name "/AIN4_Pre") (class "Default")
      (node (ref "8-Pin DIN") (pin "7") (pinfunction "CH6_7") (pintype "passive"))
      (node (ref "TP4") (pin "TP") (pinfunction "Test_Point_TP") (pintype "passive"))
      (node (ref "U18") (pin "3") (pinfunction "IN1+_3") (pintype "input"))
    )
    (net (code "22") (name "/AIN5") (class "Default")
      (node (ref "C157") (pin "1") (pinfunction "1_1") (pintype "passive"))
      (node (ref "R95") (pin "1") (pinfunction "1_1") (pintype "passive"))
      (node (ref "TP18") (pin "TP") (pinfunction "Test_Point_TP") (pintype "passive"))
      (node (ref "U20") (pin "6") (pinfunction "IN2-_6") (pintype "input"))
      (node (ref "U20") (pin "7") (pinfunction "OUT2_7") (pintype "output"))
    )
    (net (code "23") (name "/AIN5N") (class "Default")
      (node (ref "C107") (pin "2") (pinfunction "2_2") (pintype "passive"))
      (node (ref "R98") (pin "2") (pinfunction "2_2") (pintype "passive"))
      (node (ref "U19") (pin "47") (pinfunction "ADCINB1_47") (pintype "input"))
    )
    (net (code "24") (name "/AIN5P") (class "Default")
      (node (ref "C107") (pin "1") (pinfunction "1_1") (pintype "passive"))
      (node (ref "R91") (pin "2") (pinfunction "2_2") (pintype "passive"))
      (node (ref "U19") (pin "46") (pinfunction "ADCINB0_46") (pintype "input"))
    )
    (net (code "25") (name "/AIN5_Pre") (class "Default")
      (node (ref "8-Pin DIN") (pin "3") (pinfunction "CH7_3") (pintype "passive"))
      (node (ref "TP3") (pin "TP") (pinfunction "Test_Point_TP") (pintype "passive"))
      (node (ref "U20") (pin "5") (pinfunction "IN2+_5") (pintype "input"))
    )
    (net (code "26") (name "/AIN6") (class "Default")
      (node (ref "C158") (pin "1") (pinfunction "1_1") (pintype "passive"))
      (node (ref "R113") (pin "1") (pinfunction "1_1") (pintype "passive"))
      (node (ref "TP17") (pin "TP") (pinfunction "Test_Point_TP") (pintype "passive"))
      (node (ref "U20") (pin "1") (pinfunction "OUT1_1") (pintype "output"))
      (node (ref "U20") (pin "2") (pinfunction "IN1-_2") (pintype "input"))
    )
    (net (code "27") (name "/AIN6N") (class "Default")
      (node (ref "C120") (pin "2") (pinfunction "2_2") (pintype "passive"))
      (node (ref "R116") (pin "2") (pinfunction "2_2") (pintype "passive"))
      (node (ref "U19") (pin "30") (pinfunction "ADCINC3_30") (pintype "input"))
    )
    (net (code "28") (name "/AIN6P") (class "Default")
      (node (ref "C120") (pin "1") (pinfunction "1_1") (pintype "passive"))
      (node (ref "R109") (pin "2") (pinfunction "2_2") (pintype "passive"))
      (node (ref "U19") (pin "31") (pinfunction "ADCINC2_31") (pintype "input"))
    )
    (net (code "29") (name "/AIN6_Pre") (class "Default")
      (node (ref "8-Pin DIN") (pin "6") (pinfunction "CH8_6") (pintype "passive"))
      (node (ref "TP2") (pin "TP") (pinfunction "Test_Point_TP") (pintype "passive"))
      (node (ref "U20") (pin "3") (pinfunction "IN1+_3") (pintype "input"))
    )
    (net (code "30") (name "/CTS") (class "Default")
      (node (ref "FTDI USB UART") (pin "3") (pinfunction "RTS#_3") (pintype "input"))
      (node (ref "U19") (pin "170") (pinfunction "GPIO88_170") (pintype "bidirectional"))
    )
    (net (code "31") (name "/GPIO68") (class "Default")
      (node (ref "GPIO Breakout") (pin "21") (pinfunction "21_21") (pintype "passive"))
      (node (ref "U19") (pin "133") (pinfunction "GPIO68_133") (pintype "bidirectional"))
    )
    (net (code "32") (name "/GPIO69") (class "Default")
      (node (ref "GPIO Breakout") (pin "20") (pinfunction "20_20") (pintype "passive"))
      (node (ref "U19") (pin "134") (pinfunction "GPIO69_134") (pintype "bidirectional"))
    )
    (net (code "33") (name "/GPIO70") (class "Default")
      (node (ref "GPIO Breakout") (pin "19") (pinfunction "19_19") (pintype "passive"))
      (node (ref "U19") (pin "135") (pinfunction "GPIO70_135") (pintype "bidirectional"))
    )
    (net (code "34") (name "/GPIO71") (class "Default")
      (node (ref "GPIO Breakout") (pin "18") (pinfunction "18_18") (pintype "passive"))
      (node (ref "U19") (pin "136") (pinfunction "GPIO71_136") (pintype "bidirectional"))
    )
    (net (code "35") (name "/GPIO72") (class "Default")
      (node (ref "R147") (pin "2") (pinfunction "2_2") (pintype "passive"))
      (node (ref "S1") (pin "5") (pinfunction "B2_5") (pintype "passive"))
      (node (ref "U19") (pin "139") (pinfunction "GPIO72_139") (pintype "bidirectional"))
    )
    (net (code "36") (name "/GPIO73") (class "Default")
      (node (ref "GPIO Breakout") (pin "17") (pinfunction "17_17") (pintype "passive"))
      (node (ref "U19") (pin "140") (pinfunction "GPIO73_140") (pintype "bidirectional"))
    )
    (net (code "37") (name "/GPIO74") (class "Default")
      (node (ref "GPIO Breakout") (pin "16") (pinfunction "16_16") (pintype "passive"))
      (node (ref "U19") (pin "141") (pinfunction "GPIO74_141") (pintype "bidirectional"))
    )
    (net (code "38") (name "/GPIO75") (class "Default")
      (node (ref "GPIO Breakout") (pin "15") (pinfunction "15_15") (pintype "passive"))
      (node (ref "U19") (pin "142") (pinfunction "GPIO75_142") (pintype "bidirectional"))
    )
    (net (code "39") (name "/GPIO76") (class "Default")
      (node (ref "GPIO Breakout") (pin "14") (pinfunction "14_14") (pintype "passive"))
      (node (ref "U19") (pin "143") (pinfunction "GPIO76_143") (pintype "bidirectional"))
    )
    (net (code "40") (name "/GPIO77") (class "Default")
      (node (ref "GPIO Breakout") (pin "13") (pinfunction "13_13") (pintype "passive"))
      (node (ref "U19") (pin "144") (pinfunction "GPIO77_144") (pintype "bidirectional"))
    )
    (net (code "41") (name "/GPIO78") (class "Default")
      (node (ref "GPIO Breakout") (pin "12") (pinfunction "12_12") (pintype "passive"))
      (node (ref "U19") (pin "145") (pinfunction "GPIO78_145") (pintype "bidirectional"))
    )
    (net (code "42") (name "/GPIO79") (class "Default")
      (node (ref "GPIO Breakout") (pin "11") (pinfunction "11_11") (pintype "passive"))
      (node (ref "U19") (pin "146") (pinfunction "GPIO79_146") (pintype "bidirectional"))
    )
    (net (code "43") (name "/GPIO80") (class "Default")
      (node (ref "GPIO Breakout") (pin "10") (pinfunction "10_10") (pintype "passive"))
      (node (ref "U19") (pin "148") (pinfunction "GPIO80_148") (pintype "bidirectional"))
    )
    (net (code "44") (name "/GPIO81") (class "Default")
      (node (ref "GPIO Breakout") (pin "9") (pinfunction "9_9") (pintype "passive"))
      (node (ref "U19") (pin "149") (pinfunction "GPIO81_149") (pintype "bidirectional"))
    )
    (net (code "45") (name "/GPIO82") (class "Default")
      (node (ref "GPIO Breakout") (pin "8") (pinfunction "8_8") (pintype "passive"))
      (node (ref "U19") (pin "150") (pinfunction "GPIO82_150") (pintype "bidirectional"))
    )
    (net (code "46") (name "/GPIO83") (class "Default")
      (node (ref "GPIO Breakout") (pin "7") (pinfunction "7_7") (pintype "passive"))
      (node (ref "U19") (pin "151") (pinfunction "GPIO83_151") (pintype "bidirectional"))
    )
    (net (code "47") (name "/GPIO84") (class "Default")
      (node (ref "R130") (pin "2") (pinfunction "2_2") (pintype "passive"))
      (node (ref "S1") (pin "6") (pinfunction "B1_6") (pintype "passive"))
      (node (ref "U19") (pin "154") (pinfunction "GPIO84_154") (pintype "bidirectional"))
    )
    (net (code "48") (name "/GPIO89") (class "Default")
      (node (ref "GPIO Breakout") (pin "6") (pinfunction "6_6") (pintype "passive"))
      (node (ref "U19") (pin "171") (pinfunction "GPIO89_171") (pintype "bidirectional"))
    )
    (net (code "49") (name "/GPIO90") (class "Default")
      (node (ref "GPIO Breakout") (pin "5") (pinfunction "5_5") (pintype "passive"))
      (node (ref "U19") (pin "172") (pinfunction "GPIO90_172") (pintype "bidirectional"))
    )
    (net (code "50") (name "/GPIO91") (class "Default")
      (node (ref "GPIO Breakout") (pin "4") (pinfunction "4_4") (pintype "passive"))
      (node (ref "U19") (pin "173") (pinfunction "GPIO91_173") (pintype "bidirectional"))
    )
    (net (code "51") (name "/GPIO92") (class "Default")
      (node (ref "GPIO Breakout") (pin "3") (pinfunction "3_3") (pintype "passive"))
      (node (ref "U19") (pin "174") (pinfunction "GPIO92_174") (pintype "bidirectional"))
    )
    (net (code "52") (name "/GPIO93") (class "Default")
      (node (ref "GPIO Breakout") (pin "2") (pinfunction "2_2") (pintype "passive"))
      (node (ref "U19") (pin "175") (pinfunction "GPIO93_175") (pintype "bidirectional"))
    )
    (net (code "53") (name "/GPIO94") (class "Default")
      (node (ref "GPIO Breakout") (pin "1") (pinfunction "1_1") (pintype "passive"))
      (node (ref "U19") (pin "176") (pinfunction "GPIO94_176") (pintype "bidirectional"))
    )
    (net (code "54") (name "/RESET") (class "Default")
      (node (ref "C57") (pin "2") (pinfunction "2_2") (pintype "passive"))
      (node (ref "R140") (pin "1") (pinfunction "1_1") (pintype "passive"))
      (node (ref "RESET") (pin "2") (pinfunction "4_2") (pintype "passive"))
      (node (ref "U19") (pin "124") (pinfunction "XRS_N_124") (pintype "bidirectional"))
    )
    (net (code "55") (name "/RTS") (class "Default")
      (node (ref "FTDI USB UART") (pin "11") (pinfunction "CTS#_11") (pintype "input"))
      (node (ref "U19") (pin "155") (pinfunction "GPIO85_155") (pintype "bidirectional"))
    )
    (net (code "56") (name "/RXLED#") (class "Default")
      (node (ref "FTDI USB UART") (pin "22") (pinfunction "CBUS1_22") (pintype "passive"))
      (node (ref "R141") (pin "1") (pinfunction "1_1") (pintype "passive"))
    )
    (net (code "57") (name "/SCI_RXDB") (class "Default")
      (node (ref "FTDI USB UART") (pin "1") (pinfunction "TXD_1") (pintype "input"))
      (node (ref "U19") (pin "157") (pinfunction "GPIO87_157") (pintype "bidirectional"))
    )
    (net (code "58") (name "/SCI_TXDB") (class "Default")
      (node (ref "FTDI USB UART") (pin "5") (pinfunction "RXD_5") (pintype "input"))
      (node (ref "U19") (pin "156") (pinfunction "GPIO86_156") (pintype "bidirectional"))
    )
    (net (code "59") (name "/SPIA_CLK") (class "Default")
      (node (ref "Ethernet Port") (pin "7") (pinfunction "D7_7") (pintype "input"))
      (node (ref "Ethernet Port") (pin "8") (pinfunction "D8_8") (pintype "input"))
      (node (ref "Transceiver Out") (pin "1") (pinfunction "1D_1") (pintype "input"))
      (node (ref "Transceiver Out") (pin "19") (pinfunction "1Z_19") (pintype "passive"))
      (node (ref "Transceiver Out") (pin "20") (pinfunction "1Y_20") (pintype "passive"))
      (node (ref "U19") (pin "105") (pinfunction "GPIO60_105") (pintype "bidirectional"))
    )
    (net (code "60") (name "/SPIA_Data") (class "Default")
      (node (ref "Ethernet Port") (pin "1") (pinfunction "D1_1") (pintype "input"))
      (node (ref "Ethernet Port") (pin "2") (pinfunction "D2_2") (pintype "input"))
      (node (ref "Transceiver Out") (pin "13") (pinfunction "4Z_13") (pintype "passive"))
      (node (ref "Transceiver Out") (pin "14") (pinfunction "4Y_14") (pintype "passive"))
      (node (ref "Transceiver Out") (pin "7") (pinfunction "4D_7") (pintype "input"))
      (node (ref "U19") (pin "103") (pinfunction "GPIO58_103") (pintype "bidirectional"))
    )
    (net (code "61") (name "/Sum_Out") (class "Default")
      (node (ref "Audio Out") (pin "T") (pinfunction "T_T") (pintype "input"))
      (node (ref "C141") (pin "2") (pinfunction "2_2") (pintype "passive"))
      (node (ref "R136") (pin "2") (pinfunction "2_2") (pintype "passive"))
      (node (ref "TP39") (pin "TP") (pinfunction "Test_Point_TP") (pintype "passive"))
    )
    (net (code "62") (name "/TCK") (class "Default")
      (node (ref "JTAG") (pin "11") (pinfunction "11_11") (pintype "passive"))
      (node (ref "JTAG") (pin "9") (pinfunction "9_9") (pintype "passive"))
      (node (ref "R142") (pin "2") (pinfunction "2_2") (pintype "passive"))
      (node (ref "U19") (pin "81") (pinfunction "TCK_81") (pintype "input"))
    )
    (net (code "63") (name "/TDI") (class "Default")
      (node (ref "JTAG") (pin "3") (pinfunction "3_3") (pintype "passive"))
      (node (ref "U19") (pin "77") (pinfunction "TDI_77") (pintype "input"))
    )
    (net (code "64") (name "/TDO") (class "Default")
      (node (ref "JTAG") (pin "7") (pinfunction "7_7") (pintype "passive"))
      (node (ref "R143") (pin "2") (pinfunction "2_2") (pintype "passive"))
      (node (ref "U19") (pin "78") (pinfunction "TDO_78") (pintype "output"))
    )
    (net (code "65") (name "/TMS") (class "Default")
      (node (ref "JTAG") (pin "1") (pinfunction "1_1") (pintype "passive"))
      (node (ref "U19") (pin "80") (pinfunction "TMS_80") (pintype "input"))
    )
    (net (code "66") (name "/TRST") (class "Default")
      (node (ref "JTAG") (pin "2") (pinfunction "2_2") (pintype "passive"))
      (node (ref "R148") (pin "2") (pinfunction "2_2") (pintype "passive"))
      (node (ref "U19") (pin "79") (pinfunction "TRST_N_79") (pintype "input"))
    )
    (net (code "67") (name "/TXLED#") (class "Default")
      (node (ref "FTDI USB UART") (pin "23") (pinfunction "CBUS0_23") (pintype "passive"))
      (node (ref "R132") (pin "1") (pinfunction "1_1") (pintype "passive"))
    )
    (net (code "68") (name "/USB_3V3") (class "Default")
      (node (ref "CU4") (pin "1") (pinfunction "1_1") (pintype "passive"))
      (node (ref "D_USB_RX") (pin "1") (pinfunction "A_1") (pintype "passive"))
      (node (ref "D_USB_TX") (pin "1") (pinfunction "A_1") (pintype "passive"))
      (node (ref "FTDI USB UART") (pin "17") (pinfunction "3V3OUT_17") (pintype "input"))
      (node (ref "FTDI USB UART") (pin "4") (pinfunction "VCCIO_4") (pintype "input"))
    )
    (net (code "69") (name "/USB_VCC") (class "Default")
      (node (ref "CU2") (pin "1") (pinfunction "1_1") (pintype "passive"))
      (node (ref "CU3") (pin "1") (pinfunction "1_1") (pintype "passive"))
      (node (ref "FB1") (pin "2") (pinfunction "2_2") (pintype "passive"))
      (node (ref "FTDI USB UART") (pin "20") (pinfunction "VCC_20") (pintype "input"))
    )
    (net (code "70") (name "/VOCM") (class "Default")
      (node (ref "C128") (pin "1") (pinfunction "1_1") (pintype "passive"))
      (node (ref "C129") (pin "1") (pinfunction "1_1") (pintype "passive"))
      (node (ref "C130") (pin "1") (pinfunction "1_1") (pintype "passive"))
      (node (ref "C131") (pin "1") (pinfunction "1_1") (pintype "passive"))
      (node (ref "C132") (pin "1") (pinfunction "1_1") (pintype "passive"))
      (node (ref "C133") (pin "1") (pinfunction "1_1") (pintype "passive"))
      (node (ref "C59") (pin "1") (pinfunction "1_1") (pintype "passive"))
      (node (ref "R28") (pin "1") (pinfunction "1_1") (pintype "passive"))
      (node (ref "R29") (pin "2") (pinfunction "2_2") (pintype "passive"))
      (node (ref "TP23") (pin "TP") (pinfunction "Test_Point_TP") (pintype "passive"))
      (node (ref "U10") (pin "2") (pinfunction "VOCM_2") (pintype "input"))
      (node (ref "U13") (pin "2") (pinfunction "VOCM_2") (pintype "input"))
      (node (ref "U15") (pin "2") (pinfunction "VOCM_2") (pintype "input"))
      (node (ref "U17") (pin "2") (pinfunction "VOCM_2") (pintype "input"))
      (node (ref "U6") (pin "2") (pinfunction "VOCM_2") (pintype "input"))
      (node (ref "U8") (pin "2") (pinfunction "VOCM_2") (pintype "input"))
    )
    (net (code "71") (name "/VREF") (class "Default")
      (node (ref "C40") (pin "1") (pinfunction "1_1") (pintype "passive"))
      (node (ref "R28") (pin "2") (pinfunction "2_2") (pintype "passive"))
      (node (ref "R5") (pin "2") (pinfunction "2_2") (pintype "passive"))
      (node (ref "TP29") (pin "TP") (pinfunction "Test_Point_TP") (pintype "passive"))
      (node (ref "U4") (pin "6") (pinfunction "VOUT_6") (pintype "output"))
    )
    (net (code "72") (name "/VREFHIA") (class "Default")
      (node (ref "R6") (pin "1") (pinfunction "1_1") (pintype "passive"))
      (node (ref "TP30") (pin "TP") (pinfunction "Test_Point_TP") (pintype "passive"))
      (node (ref "U19") (pin "35") (pinfunction "VREFHIC_35") (pintype "input"))
      (node (ref "U19") (pin "37") (pinfunction "VREFHIA_37") (pintype "input"))
      (node (ref "U3") (pin "2") (pinfunction "IN-_2") (pintype "input"))
      (node (ref "U3") (pin "6") (pinfunction "OUT_6") (pintype "output"))
    )
    (net (code "73") (name "/VREFHIB") (class "Default")
      (node (ref "R7") (pin "1") (pinfunction "1_1") (pintype "passive"))
      (node (ref "TP32") (pin "TP") (pinfunction "Test_Point_TP") (pintype "passive"))
      (node (ref "U19") (pin "53") (pinfunction "VREFHIB_53") (pintype "input"))
      (node (ref "U19") (pin "55") (pinfunction "VREFHID_55") (pintype "input"))
      (node (ref "U5") (pin "2") (pinfunction "IN-_2") (pintype "input"))
      (node (ref "U5") (pin "6") (pinfunction "OUT_6") (pintype "output"))
    )
    (net (code "74") (name "/VSSOSC") (class "Default")
      (node (ref "C135") (pin "1") (pinfunction "1_1") (pintype "passive"))
      (node (ref "C136") (pin "1") (pinfunction "1_1") (pintype "passive"))
      (node (ref "U19") (pin "122") (pinfunction "VSSOSC_122") (pintype "power_in"))
    )
    (net (code "75") (name "/X1") (class "Default")
      (node (ref "C135") (pin "2") (pinfunction "2_2") (pintype "passive"))
      (node (ref "R120") (pin "1") (pinfunction "1_1") (pintype "passive"))
      (node (ref "U19") (pin "123") (pinfunction "X1_123") (pintype "input"))
      (node (ref "XTALA") (pin "1") (pinfunction "51_1") (pintype "passive"))
    )
    (net (code "76") (name "/X2") (class "Default")
      (node (ref "C136") (pin "2") (pinfunction "2_2") (pintype "passive"))
      (node (ref "R120") (pin "2") (pinfunction "2_2") (pintype "passive"))
      (node (ref "U19") (pin "121") (pinfunction "X2_121") (pintype "output"))
      (node (ref "XTALA") (pin "2") (pinfunction "52_2") (pintype "passive"))
    )
    (net (code "77") (name "AGND") (class "Default")
      (node (ref "12V AGND") (pin "6") (pinfunction "6_6") (pintype "passive"))
      (node (ref "12V AGND") (pin "7") (pinfunction "7_7") (pintype "passive"))
      (node (ref "12V AGND") (pin "8") (pinfunction "8_8") (pintype "passive"))
      (node (ref "8-Pin DIN") (pin "1") (pinfunction "Case_GND_1") (pintype "passive"))
      (node (ref "8-Pin DIN") (pin "2") (pinfunction "Case_GND_2") (pintype "passive"))
      (node (ref "8-Pin DIN") (pin "4") (pinfunction "CH4_4") (pintype "passive"))
      (node (ref "Audio Out") (pin "S") (pinfunction "S_S") (pintype "power_in"))
      (node (ref "C102") (pin "2") (pinfunction "2_2") (pintype "passive"))
      (node (ref "C104") (pin "2") (pinfunction "2_2") (pintype "passive"))
      (node (ref "C108") (pin "2") (pinfunction "2_2") (pintype "passive"))
      (node (ref "C109") (pin "2") (pinfunction "2_2") (pintype "passive"))
      (node (ref "C110") (pin "2") (pinfunction "2_2") (pintype "passive"))
      (node (ref "C111") (pin "1") (pinfunction "1_1") (pintype "passive"))
      (node (ref "C112") (pin "2") (pinfunction "2_2") (pintype "passive"))
      (node (ref "C115") (pin "2") (pinfunction "2_2") (pintype "passive"))
      (node (ref "C116") (pin "1") (pinfunction "1_1") (pintype "passive"))
      (node (ref "C117") (pin "2") (pinfunction "2_2") (pintype "passive"))
      (node (ref "C121") (pin "2") (pinfunction "2_2") (pintype "passive"))
      (node (ref "C122") (pin "2") (pinfunction "2_2") (pintype "passive"))
      (node (ref "C123") (pin "2") (pinfunction "2_2") (pintype "passive"))
      (node (ref "C125") (pin "2") (pinfunction "2_2") (pintype "passive"))
      (node (ref "C128") (pin "2") (pinfunction "2_2") (pintype "passive"))
      (node (ref "C129") (pin "2") (pinfunction "2_2") (pintype "passive"))
      (node (ref "C130") (pin "2") (pinfunction "2_2") (pintype "passive"))
      (node (ref "C131") (pin "2") (pinfunction "2_2") (pintype "passive"))
      (node (ref "C132") (pin "2") (pinfunction "2_2") (pintype "passive"))
      (node (ref "C133") (pin "2") (pinfunction "2_2") (pintype "passive"))
      (node (ref "C137") (pin "1") (pinfunction "1_1") (pintype "passive"))
      (node (ref "C139") (pin "1") (pinfunction "1_1") (pintype "passive"))
      (node (ref "C142") (pin "1") (pinfunction "1_1") (pintype "passive"))
      (node (ref "C143") (pin "1") (pinfunction "1_1") (pintype "passive"))
      (node (ref "C145") (pin "1") (pinfunction "1_1") (pintype "passive"))
      (node (ref "C146") (pin "1") (pinfunction "1_1") (pintype "passive"))
      (node (ref "C148") (pin "1") (pinfunction "1_1") (pintype "passive"))
      (node (ref "C149") (pin "1") (pinfunction "1_1") (pintype "passive"))
      (node (ref "C152") (pin "2") (pinfunction "2_2") (pintype "passive"))
      (node (ref "C156") (pin "2") (pinfunction "2_2") (pintype "passive"))
      (node (ref "C159") (pin "1") (pinfunction "1_1") (pintype "passive"))
      (node (ref "C160") (pin "1") (pinfunction "1_1") (pintype "passive"))
      (node (ref "C162") (pin "1") (pinfunction "1_1") (pintype "passive"))
      (node (ref "C163") (pin "1") (pinfunction "1_1") (pintype "passive"))
      (node (ref "C164") (pin "1") (pinfunction "1_1") (pintype "passive"))
      (node (ref "C165") (pin "1") (pinfunction "1_1") (pintype "passive"))
      (node (ref "C166") (pin "1") (pinfunction "1_1") (pintype "passive"))
      (node (ref "C167") (pin "1") (pinfunction "1_1") (pintype "passive"))
      (node (ref "C168") (pin "1") (pinfunction "1_1") (pintype "passive"))
      (node (ref "C169") (pin "1") (pinfunction "1_1") (pintype "passive"))
      (node (ref "C170") (pin "1") (pinfunction "1_1") (pintype "passive"))
      (node (ref "C171") (pin "1") (pinfunction "1_1") (pintype "passive"))
      (node (ref "C172") (pin "1") (pinfunction "1_1") (pintype "passive"))
      (node (ref "C37") (pin "2") (pinfunction "2_2") (pintype "passive"))
      (node (ref "C38") (pin "2") (pinfunction "2_2") (pintype "passive"))
      (node (ref "C39") (pin "2") (pinfunction "2_2") (pintype "passive"))
      (node (ref "C40") (pin "2") (pinfunction "2_2") (pintype "passive"))
      (node (ref "C41") (pin "2") (pinfunction "2_2") (pintype "passive"))
      (node (ref "C42") (pin "2") (pinfunction "2_2") (pintype "passive"))
      (node (ref "C43") (pin "2") (pinfunction "2_2") (pintype "passive"))
      (node (ref "C44") (pin "2") (pinfunction "2_2") (pintype "passive"))
      (node (ref "C45") (pin "2") (pinfunction "2_2") (pintype "passive"))
      (node (ref "C46") (pin "2") (pinfunction "2_2") (pintype "passive"))
      (node (ref "C52") (pin "2") (pinfunction "2_2") (pintype "passive"))
      (node (ref "C53") (pin "2") (pinfunction "2_2") (pintype "passive"))
      (node (ref "C56") (pin "2") (pinfunction "2_2") (pintype "passive"))
      (node (ref "C58") (pin "2") (pinfunction "2_2") (pintype "passive"))
      (node (ref "C59") (pin "2") (pinfunction "2_2") (pintype "passive"))
      (node (ref "C60") (pin "2") (pinfunction "2_2") (pintype "passive"))
      (node (ref "C61") (pin "2") (pinfunction "2_2") (pintype "passive"))
      (node (ref "C62") (pin "2") (pinfunction "2_2") (pintype "passive"))
      (node (ref "C63") (pin "2") (pinfunction "2_2") (pintype "passive"))
      (node (ref "C64") (pin "2") (pinfunction "2_2") (pintype "passive"))
      (node (ref "C65") (pin "2") (pinfunction "2_2") (pintype "passive"))
      (node (ref "C69") (pin "2") (pinfunction "2_2") (pintype "passive"))
      (node (ref "C70") (pin "2") (pinfunction "2_2") (pintype "passive"))
      (node (ref "C71") (pin "2") (pinfunction "2_2") (pintype "passive"))
      (node (ref "C72") (pin "2") (pinfunction "2_2") (pintype "passive"))
      (node (ref "C73") (pin "2") (pinfunction "2_2") (pintype "passive"))
      (node (ref "C76") (pin "2") (pinfunction "2_2") (pintype "passive"))
      (node (ref "C77") (pin "2") (pinfunction "2_2") (pintype "passive"))
      (node (ref "C78") (pin "2") (pinfunction "2_2") (pintype "passive"))
      (node (ref "C82") (pin "2") (pinfunction "2_2") (pintype "passive"))
      (node (ref "C83") (pin "2") (pinfunction "2_2") (pintype "passive"))
      (node (ref "C84") (pin "2") (pinfunction "2_2") (pintype "passive"))
      (node (ref "C85") (pin "2") (pinfunction "2_2") (pintype "passive"))
      (node (ref "C86") (pin "2") (pinfunction "2_2") (pintype "passive"))
      (node (ref "C89") (pin "2") (pinfunction "2_2") (pintype "passive"))
      (node (ref "C90") (pin "2") (pinfunction "2_2") (pintype "passive"))
      (node (ref "C91") (pin "2") (pinfunction "2_2") (pintype "passive"))
      (node (ref "C95") (pin "2") (pinfunction "2_2") (pintype "passive"))
      (node (ref "C96") (pin "2") (pinfunction "2_2") (pintype "passive"))
      (node (ref "C97") (pin "2") (pinfunction "2_2") (pintype "passive"))
      (node (ref "C99") (pin "2") (pinfunction "2_2") (pintype "passive"))
      (node (ref "CU4") (pin "2") (pinfunction "2_2") (pintype "passive"))
      (node (ref "D1") (pin "1") (pinfunction "A_1") (pintype "passive"))
      (node (ref "D3") (pin "2") (pinfunction "K_2") (pintype "passive"))
      (node (ref "D_Power") (pin "2") (pinfunction "K_2") (pintype "passive"))
      (node (ref "FTDI USB UART") (pin "21") (pinfunction "GND_21") (pintype "input"))
      (node (ref "FTDI USB UART") (pin "25") (pinfunction "AGND_25") (pintype "input"))
      (node (ref "FTDI USB UART") (pin "26") (pinfunction "TEST_26") (pintype "input"))
      (node (ref "R102") (pin "1") (pinfunction "1_1") (pintype "passive"))
      (node (ref "R104") (pin "1") (pinfunction "1_1") (pintype "passive"))
      (node (ref "R106") (pin "1") (pinfunction "1_1") (pintype "passive"))
      (node (ref "R11") (pin "1") (pinfunction "1_1") (pintype "passive"))
      (node (ref "R126") (pin "1") (pinfunction "1_1") (pintype "passive"))
      (node (ref "R13") (pin "1") (pinfunction "1_1") (pintype "passive"))
      (node (ref "R136") (pin "1") (pinfunction "1_1") (pintype "passive"))
      (node (ref "R145") (pin "1") (pinfunction "1_1") (pintype "passive"))
      (node (ref "R15") (pin "1") (pinfunction "1_1") (pintype "passive"))
      (node (ref "R29") (pin "1") (pinfunction "1_1") (pintype "passive"))
      (node (ref "R3") (pin "2") (pinfunction "2_2") (pintype "passive"))
      (node (ref "R30") (pin "1") (pinfunction "1_1") (pintype "passive"))
      (node (ref "R32") (pin "1") (pinfunction "1_1") (pintype "passive"))
      (node (ref "R34") (pin "1") (pinfunction "1_1") (pintype "passive"))
      (node (ref "R4") (pin "1") (pinfunction "1_1") (pintype "passive"))
      (node (ref "R48") (pin "1") (pinfunction "1_1") (pintype "passive"))
      (node (ref "R50") (pin "1") (pinfunction "1_1") (pintype "passive"))
      (node (ref "R52") (pin "1") (pinfunction "1_1") (pintype "passive"))
      (node (ref "R66") (pin "1") (pinfunction "1_1") (pintype "passive"))
      (node (ref "R68") (pin "1") (pinfunction "1_1") (pintype "passive"))
      (node (ref "R70") (pin "1") (pinfunction "1_1") (pintype "passive"))
      (node (ref "R84") (pin "1") (pinfunction "1_1") (pintype "passive"))
      (node (ref "R86") (pin "1") (pinfunction "1_1") (pintype "passive"))
      (node (ref "R88") (pin "1") (pinfunction "1_1") (pintype "passive"))
      (node (ref "R9") (pin "1") (pinfunction "1_1") (pintype "passive"))
      (node (ref "U10") (pin "6") (pinfunction "VS-_6") (pintype "power_in"))
      (node (ref "U13") (pin "6") (pinfunction "VS-_6") (pintype "power_in"))
      (node (ref "U15") (pin "6") (pinfunction "VS-_6") (pintype "power_in"))
      (node (ref "U17") (pin "6") (pinfunction "VS-_6") (pintype "power_in"))
      (node (ref "U19") (pin "32") (pinfunction "VREFLOC_32") (pintype "input"))
      (node (ref "U19") (pin "33") (pinfunction "VREFLOA_33") (pintype "input"))
      (node (ref "U19") (pin "34") (pinfunction "VSSA_34") (pintype "power_in"))
      (node (ref "U19") (pin "50") (pinfunction "VREFLOB_50") (pintype "input"))
      (node (ref "U19") (pin "51") (pinfunction "VREFLOD_51") (pintype "input"))
      (node (ref "U19") (pin "52") (pinfunction "VSSA_52") (pintype "power_in"))
      (node (ref "U2") (pin "10") (pinfunction "GND_10") (pintype "power_in"))
      (node (ref "U2") (pin "13") (pinfunction "PAD_13") (pintype "power_in"))
      (node (ref "U2") (pin "9") (pinfunction "GND_9") (pintype "power_in"))
      (node (ref "U21") (pin "1") (pinfunction "GND_1") (pintype "power_in"))
      (node (ref "U22") (pin "1") (pinfunction "GND_1") (pintype "power_in"))
      (node (ref "U24") (pin "1") (pinfunction "GND_1") (pintype "power_in"))
      (node (ref "U25") (pin "3") (pinfunction "IN1+_3") (pintype "input"))
      (node (ref "U25") (pin "5") (pinfunction "IN2+_5") (pintype "input"))
      (node (ref "U3") (pin "4") (pinfunction "V-_4") (pintype "power_in"))
      (node (ref "U4") (pin "4") (pinfunction "GND_4") (pintype "power_in"))
      (node (ref "U5") (pin "4") (pinfunction "V-_4") (pintype "power_in"))
      (node (ref "U6") (pin "6") (pinfunction "VS-_6") (pintype "power_in"))
      (node (ref "U8") (pin "6") (pinfunction "VS-_6") (pintype "power_in"))
    )
    (net (code "78") (name "DGND") (class "Default")
      (node (ref "C1") (pin "2") (pinfunction "2_2") (pintype "passive"))
      (node (ref "C10") (pin "2") (pinfunction "2_2") (pintype "passive"))
      (node (ref "C103") (pin "2") (pinfunction "2_2") (pintype "passive"))
      (node (ref "C11") (pin "2") (pinfunction "2_2") (pintype "passive"))
      (node (ref "C12") (pin "2") (pinfunction "2_2") (pintype "passive"))
      (node (ref "C13") (pin "2") (pinfunction "2_2") (pintype "passive"))
      (node (ref "C134") (pin "1") (pinfunction "1_1") (pintype "passive"))
      (node (ref "C14") (pin "2") (pinfunction "2_2") (pintype "passive"))
      (node (ref "C15") (pin "2") (pinfunction "2_2") (pintype "passive"))
      (node (ref "C17") (pin "2") (pinfunction "2_2") (pintype "passive"))
      (node (ref "C18") (pin "2") (pinfunction "2_2") (pintype "passive"))
      (node (ref "C19") (pin "2") (pinfunction "2_2") (pintype "passive"))
      (node (ref "C2") (pin "2") (pinfunction "2_2") (pintype "passive"))
      (node (ref "C20") (pin "2") (pinfunction "2_2") (pintype "passive"))
      (node (ref "C21") (pin "2") (pinfunction "2_2") (pintype "passive"))
      (node (ref "C22") (pin "2") (pinfunction "2_2") (pintype "passive"))
      (node (ref "C23") (pin "2") (pinfunction "2_2") (pintype "passive"))
      (node (ref "C24") (pin "2") (pinfunction "2_2") (pintype "passive"))
      (node (ref "C26") (pin "2") (pinfunction "2_2") (pintype "passive"))
      (node (ref "C27") (pin "2") (pinfunction "2_2") (pintype "passive"))
      (node (ref "C28") (pin "2") (pinfunction "2_2") (pintype "passive"))
      (node (ref "C29") (pin "2") (pinfunction "2_2") (pintype "passive"))
      (node (ref "C3") (pin "2") (pinfunction "2_2") (pintype "passive"))
      (node (ref "C30") (pin "2") (pinfunction "2_2") (pintype "passive"))
      (node (ref "C31") (pin "2") (pinfunction "2_2") (pintype "passive"))
      (node (ref "C32") (pin "2") (pinfunction "2_2") (pintype "passive"))
      (node (ref "C33") (pin "2") (pinfunction "2_2") (pintype "passive"))
      (node (ref "C34") (pin "2") (pinfunction "2_2") (pintype "passive"))
      (node (ref "C35") (pin "2") (pinfunction "2_2") (pintype "passive"))
      (node (ref "C36") (pin "2") (pinfunction "2_2") (pintype "passive"))
      (node (ref "C4") (pin "2") (pinfunction "2_2") (pintype "passive"))
      (node (ref "C5") (pin "2") (pinfunction "2_2") (pintype "passive"))
      (node (ref "C57") (pin "1") (pinfunction "1_1") (pintype "passive"))
      (node (ref "C6") (pin "2") (pinfunction "2_2") (pintype "passive"))
      (node (ref "C7") (pin "2") (pinfunction "2_2") (pintype "passive"))
      (node (ref "C8") (pin "2") (pinfunction "2_2") (pintype "passive"))
      (node (ref "C9") (pin "2") (pinfunction "2_2") (pintype "passive"))
      (node (ref "C98") (pin "2") (pinfunction "2_2") (pintype "passive"))
      (node (ref "CU1") (pin "2") (pinfunction "2_2") (pintype "passive"))
      (node (ref "CU2") (pin "2") (pinfunction "2_2") (pintype "passive"))
      (node (ref "CU3") (pin "2") (pinfunction "2_2") (pintype "passive"))
      (node (ref "D2") (pin "2") (pinfunction "K_2") (pintype "passive"))
      (node (ref "D4") (pin "1") (pinfunction "A_1") (pintype "passive"))
      (node (ref "D_TCK") (pin "2") (pinfunction "K_2") (pintype "passive"))
      (node (ref "D_TDO") (pin "2") (pinfunction "K_2") (pintype "passive"))
      (node (ref "Ethernet Port") (pin "9") (pinfunction "SHIELD_9") (pintype "power_in"))
      (node (ref "FTDI USB UART") (pin "18") (pinfunction "GND_18") (pintype "input"))
      (node (ref "FTDI USB UART") (pin "7") (pinfunction "GND_7") (pintype "input"))
      (node (ref "JTAG") (pin "10") (pinfunction "10_10") (pintype "passive"))
      (node (ref "JTAG") (pin "12") (pinfunction "12_12") (pintype "passive"))
      (node (ref "JTAG") (pin "4") (pinfunction "4_4") (pintype "passive"))
      (node (ref "JTAG") (pin "8") (pinfunction "8_8") (pintype "passive"))
      (node (ref "MINI USB") (pin "5") (pinfunction "GND_5") (pintype "passive"))
      (node (ref "R130") (pin "1") (pinfunction "1_1") (pintype "passive"))
      (node (ref "R147") (pin "1") (pinfunction "1_1") (pintype "passive"))
      (node (ref "R148") (pin "1") (pinfunction "1_1") (pintype "passive"))
      (node (ref "RESET") (pin "1") (pinfunction "3_1") (pintype "passive"))
      (node (ref "RESET") (pin "3") (pinfunction "3_3") (pintype "passive"))
      (node (ref "RESET") (pin "4") (pinfunction "4_4") (pintype "passive"))
      (node (ref "Transceiver Out") (pin "10") (pinfunction "GND_10") (pintype "power_in"))
      (node (ref "Transceiver Out") (pin "2") (pinfunction "GND_2") (pintype "power_in"))
      (node (ref "Transceiver Out") (pin "6") (pinfunction "GND_6") (pintype "power_in"))
      (node (ref "U19") (pin "177") (pinfunction "PWRPAD_177") (pintype "power_in"))
    )
    (net (code "79") (name "Net-(C44-Pad1)") (class "Default")
      (node (ref "C44") (pin "1") (pinfunction "1_1") (pintype "passive"))
      (node (ref "R6") (pin "2") (pinfunction "2_2") (pintype "passive"))
    )
    (net (code "80") (name "Net-(C46-Pad1)") (class "Default")
      (node (ref "C46") (pin "1") (pinfunction "1_1") (pintype "passive"))
      (node (ref "R7") (pin "2") (pinfunction "2_2") (pintype "passive"))
    )
    (net (code "81") (name "Net-(C54-Pad1)") (class "Default")
      (node (ref "C54") (pin "1") (pinfunction "1_1") (pintype "passive"))
      (node (ref "R21") (pin "2") (pinfunction "2_2") (pintype "passive"))
      (node (ref "R22") (pin "1") (pinfunction "1_1") (pintype "passive"))
    )
    (net (code "82") (name "Net-(C55-Pad1)") (class "Default")
      (node (ref "C55") (pin "1") (pinfunction "1_1") (pintype "passive"))
      (node (ref "R19") (pin "2") (pinfunction "2_2") (pintype "passive"))
      (node (ref "R20") (pin "1") (pinfunction "1_1") (pintype "passive"))
    )
    (net (code "83") (name "Net-(C74-Pad1)") (class "Default")
      (node (ref "C74") (pin "1") (pinfunction "1_1") (pintype "passive"))
      (node (ref "R41") (pin "2") (pinfunction "2_2") (pintype "passive"))
      (node (ref "R42") (pin "1") (pinfunction "1_1") (pintype "passive"))
    )
    (net (code "84") (name "Net-(C75-Pad1)") (class "Default")
      (node (ref "C75") (pin "1") (pinfunction "1_1") (pintype "passive"))
      (node (ref "R39") (pin "2") (pinfunction "2_2") (pintype "passive"))
      (node (ref "R40") (pin "1") (pinfunction "1_1") (pintype "passive"))
    )
    (net (code "85") (name "Net-(C87-Pad1)") (class "Default")
      (node (ref "C87") (pin "1") (pinfunction "1_1") (pintype "passive"))
      (node (ref "R59") (pin "2") (pinfunction "2_2") (pintype "passive"))
      (node (ref "R60") (pin "1") (pinfunction "1_1") (pintype "passive"))
    )
    (net (code "86") (name "Net-(C88-Pad1)") (class "Default")
      (node (ref "C88") (pin "1") (pinfunction "1_1") (pintype "passive"))
      (node (ref "R57") (pin "2") (pinfunction "2_2") (pintype "passive"))
      (node (ref "R58") (pin "1") (pinfunction "1_1") (pintype "passive"))
    )
    (net (code "87") (name "Net-(C100-Pad1)") (class "Default")
      (node (ref "C100") (pin "1") (pinfunction "1_1") (pintype "passive"))
      (node (ref "R77") (pin "2") (pinfunction "2_2") (pintype "passive"))
      (node (ref "R78") (pin "1") (pinfunction "1_1") (pintype "passive"))
    )
    (net (code "88") (name "Net-(C101-Pad1)") (class "Default")
      (node (ref "C101") (pin "1") (pinfunction "1_1") (pintype "passive"))
      (node (ref "R75") (pin "2") (pinfunction "2_2") (pintype "passive"))
      (node (ref "R76") (pin "1") (pinfunction "1_1") (pintype "passive"))
    )
    (net (code "89") (name "Net-(C113-Pad1)") (class "Default")
      (node (ref "C113") (pin "1") (pinfunction "1_1") (pintype "passive"))
      (node (ref "R95") (pin "2") (pinfunction "2_2") (pintype "passive"))
      (node (ref "R96") (pin "1") (pinfunction "1_1") (pintype "passive"))
    )
    (net (code "90") (name "Net-(C114-Pad1)") (class "Default")
      (node (ref "C114") (pin "1") (pinfunction "1_1") (pintype "passive"))
      (node (ref "R93") (pin "2") (pinfunction "2_2") (pintype "passive"))
      (node (ref "R94") (pin "1") (pinfunction "1_1") (pintype "passive"))
    )
    (net (code "91") (name "Net-(C126-Pad1)") (class "Default")
      (node (ref "C126") (pin "1") (pinfunction "1_1") (pintype "passive"))
      (node (ref "R113") (pin "2") (pinfunction "2_2") (pintype "passive"))
      (node (ref "R114") (pin "1") (pinfunction "1_1") (pintype "passive"))
    )
    (net (code "92") (name "Net-(C127-Pad1)") (class "Default")
      (node (ref "C127") (pin "1") (pinfunction "1_1") (pintype "passive"))
      (node (ref "R111") (pin "2") (pinfunction "2_2") (pintype "passive"))
      (node (ref "R112") (pin "1") (pinfunction "1_1") (pintype "passive"))
    )
    (net (code "93") (name "Net-(C150-Pad2)") (class "Default")
      (node (ref "C150") (pin "2") (pinfunction "2_2") (pintype "passive"))
      (node (ref "R10") (pin "1") (pinfunction "1_1") (pintype "passive"))
    )
    (net (code "94") (name "Net-(C151-Pad2)") (class "Default")
      (node (ref "C151") (pin "2") (pinfunction "2_2") (pintype "passive"))
      (node (ref "R134") (pin "1") (pinfunction "1_1") (pintype "passive"))
    )
    (net (code "95") (name "Net-(C153-Pad2)") (class "Default")
      (node (ref "C153") (pin "2") (pinfunction "2_2") (pintype "passive"))
      (node (ref "R135") (pin "1") (pinfunction "1_1") (pintype "passive"))
    )
    (net (code "96") (name "Net-(C155-Pad2)") (class "Default")
      (node (ref "C155") (pin "2") (pinfunction "2_2") (pintype "passive"))
      (node (ref "R137") (pin "1") (pinfunction "1_1") (pintype "passive"))
    )
    (net (code "97") (name "Net-(C157-Pad2)") (class "Default")
      (node (ref "C157") (pin "2") (pinfunction "2_2") (pintype "passive"))
      (node (ref "R138") (pin "1") (pinfunction "1_1") (pintype "passive"))
    )
    (net (code "98") (name "Net-(C158-Pad2)") (class "Default")
      (node (ref "C158") (pin "2") (pinfunction "2_2") (pintype "passive"))
      (node (ref "R139") (pin "1") (pinfunction "1_1") (pintype "passive"))
    )
    (net (code "99") (name "Net-(D_Power-A)") (class "Default")
      (node (ref "D_Power") (pin "1") (pinfunction "A_1") (pintype "passive"))
      (node (ref "R131") (pin "1") (pinfunction "1_1") (pintype "passive"))
    )
    (net (code "100") (name "Net-(D_TCK-A)") (class "Default")
      (node (ref "D_TCK") (pin "1") (pinfunction "A_1") (pintype "passive"))
      (node (ref "R142") (pin "1") (pinfunction "1_1") (pintype "passive"))
    )
    (net (code "101") (name "Net-(D_TDO-A)") (class "Default")
      (node (ref "D_TDO") (pin "1") (pinfunction "A_1") (pintype "passive"))
      (node (ref "R143") (pin "1") (pinfunction "1_1") (pintype "passive"))
    )
    (net (code "102") (name "Net-(D_USB_RX-K)") (class "Default")
      (node (ref "D_USB_RX") (pin "2") (pinfunction "K_2") (pintype "passive"))
      (node (ref "R141") (pin "2") (pinfunction "2_2") (pintype "passive"))
    )
    (net (code "103") (name "Net-(D_USB_TX-K)") (class "Default")
      (node (ref "D_USB_TX") (pin "2") (pinfunction "K_2") (pintype "passive"))
      (node (ref "R132") (pin "2") (pinfunction "2_2") (pintype "passive"))
    )
    (net (code "104") (name "Net-(FTDI USB UART-USBDM)") (class "Default")
      (node (ref "FTDI USB UART") (pin "16") (pinfunction "USBDM_16") (pintype "input"))
      (node (ref "MINI USB") (pin "2") (pinfunction "D-_2") (pintype "passive"))
    )
    (net (code "105") (name "Net-(FTDI USB UART-USBDP)") (class "Default")
      (node (ref "FTDI USB UART") (pin "15") (pinfunction "USBDP_15") (pintype "input"))
      (node (ref "MINI USB") (pin "3") (pinfunction "D+_3") (pintype "passive"))
    )
    (net (code "106") (name "Net-(Foot Switch-Input)") (class "Default")
      (node (ref "12V Input") (pin "1") (pinfunction "1_1") (pintype "passive"))
      (node (ref "Foot Switch") (pin "1") (pinfunction "Input_1") (pintype "passive"))
      (node (ref "TP26") (pin "TP") (pinfunction "Test_Point_TP") (pintype "passive"))
    )
    (net (code "107") (name "Net-(JTAG-Pad5)") (class "Default")
      (node (ref "JTAG") (pin "5") (pinfunction "5_5") (pintype "passive"))
      (node (ref "R122") (pin "2") (pinfunction "2_2") (pintype "passive"))
    )
    (net (code "108") (name "Net-(JTAG-Pad13)") (class "Default")
      (node (ref "JTAG") (pin "13") (pinfunction "13_13") (pintype "passive"))
      (node (ref "R123") (pin "2") (pinfunction "2_2") (pintype "passive"))
    )
    (net (code "109") (name "Net-(JTAG-Pad14)") (class "Default")
      (node (ref "JTAG") (pin "14") (pinfunction "14_14") (pintype "passive"))
      (node (ref "R124") (pin "2") (pinfunction "2_2") (pintype "passive"))
    )
    (net (code "110") (name "Net-(MINI USB-VCC)") (class "Default")
      (node (ref "CU1") (pin "1") (pinfunction "1_1") (pintype "passive"))
      (node (ref "FB1") (pin "1") (pinfunction "1_1") (pintype "passive"))
      (node (ref "MINI USB") (pin "1") (pinfunction "VCC_1") (pintype "passive"))
    )
    (net (code "111") (name "Net-(R1-Pad1)") (class "Default")
      (node (ref "R1") (pin "1") (pinfunction "1_1") (pintype "passive"))
      (node (ref "R15") (pin "2") (pinfunction "2_2") (pintype "passive"))
      (node (ref "R16") (pin "1") (pinfunction "1_1") (pintype "passive"))
    )
    (net (code "112") (name "Net-(R1-Pad2)") (class "Default")
      (node (ref "R1") (pin "2") (pinfunction "2_2") (pintype "passive"))
      (node (ref "R17") (pin "1") (pinfunction "1_1") (pintype "passive"))
      (node (ref "R18") (pin "2") (pinfunction "2_2") (pintype "passive"))
    )
    (net (code "113") (name "Net-(R23-Pad2)") (class "Default")
      (node (ref "R23") (pin "2") (pinfunction "2_2") (pintype "passive"))
      (node (ref "R24") (pin "1") (pinfunction "1_1") (pintype "passive"))
      (node (ref "R27") (pin "2") (pinfunction "2_2") (pintype "passive"))
    )
    (net (code "114") (name "Net-(R25-Pad2)") (class "Default")
      (node (ref "R25") (pin "2") (pinfunction "2_2") (pintype "passive"))
      (node (ref "R26") (pin "1") (pinfunction "1_1") (pintype "passive"))
      (node (ref "R27") (pin "1") (pinfunction "1_1") (pintype "passive"))
    )
    (net (code "115") (name "Net-(R30-Pad2)") (class "Default")
      (node (ref "R30") (pin "2") (pinfunction "2_2") (pintype "passive"))
      (node (ref "R31") (pin "1") (pinfunction "1_1") (pintype "passive"))
      (node (ref "R36") (pin "1") (pinfunction "1_1") (pintype "passive"))
    )
    (net (code "116") (name "Net-(R31-Pad2)") (class "Default")
      (node (ref "R31") (pin "2") (pinfunction "2_2") (pintype "passive"))
      (node (ref "R37") (pin "1") (pinfunction "1_1") (pintype "passive"))
      (node (ref "R38") (pin "2") (pinfunction "2_2") (pintype "passive"))
    )
    (net (code "117") (name "Net-(R43-Pad2)") (class "Default")
      (node (ref "R43") (pin "2") (pinfunction "2_2") (pintype "passive"))
      (node (ref "R44") (pin "1") (pinfunction "1_1") (pintype "passive"))
      (node (ref "R47") (pin "2") (pinfunction "2_2") (pintype "passive"))
    )
    (net (code "118") (name "Net-(R45-Pad2)") (class "Default")
      (node (ref "R45") (pin "2") (pinfunction "2_2") (pintype "passive"))
      (node (ref "R46") (pin "1") (pinfunction "1_1") (pintype "passive"))
      (node (ref "R47") (pin "1") (pinfunction "1_1") (pintype "passive"))
    )
    (net (code "119") (name "Net-(R48-Pad2)") (class "Default")
      (node (ref "R48") (pin "2") (pinfunction "2_2") (pintype "passive"))
      (node (ref "R49") (pin "1") (pinfunction "1_1") (pintype "passive"))
      (node (ref "R54") (pin "1") (pinfunction "1_1") (pintype "passive"))
    )
    (net (code "120") (name "Net-(R49-Pad2)") (class "Default")
      (node (ref "R49") (pin "2") (pinfunction "2_2") (pintype "passive"))
      (node (ref "R55") (pin "1") (pinfunction "1_1") (pintype "passive"))
      (node (ref "R56") (pin "2") (pinfunction "2_2") (pintype "passive"))
    )
    (net (code "121") (name "Net-(R61-Pad2)") (class "Default")
      (node (ref "R61") (pin "2") (pinfunction "2_2") (pintype "passive"))
      (node (ref "R62") (pin "1") (pinfunction "1_1") (pintype "passive"))
      (node (ref "R65") (pin "2") (pinfunction "2_2") (pintype "passive"))
    )
    (net (code "122") (name "Net-(R63-Pad2)") (class "Default")
      (node (ref "R63") (pin "2") (pinfunction "2_2") (pintype "passive"))
      (node (ref "R64") (pin "1") (pinfunction "1_1") (pintype "passive"))
      (node (ref "R65") (pin "1") (pinfunction "1_1") (pintype "passive"))
    )
    (net (code "123") (name "Net-(R66-Pad2)") (class "Default")
      (node (ref "R66") (pin "2") (pinfunction "2_2") (pintype "passive"))
      (node (ref "R67") (pin "1") (pinfunction "1_1") (pintype "passive"))
      (node (ref "R72") (pin "1") (pinfunction "1_1") (pintype "passive"))
    )
    (net (code "124") (name "Net-(R67-Pad2)") (class "Default")
      (node (ref "R67") (pin "2") (pinfunction "2_2") (pintype "passive"))
      (node (ref "R73") (pin "1") (pinfunction "1_1") (pintype "passive"))
      (node (ref "R74") (pin "2") (pinfunction "2_2") (pintype "passive"))
    )
    (net (code "125") (name "Net-(R79-Pad2)") (class "Default")
      (node (ref "R79") (pin "2") (pinfunction "2_2") (pintype "passive"))
      (node (ref "R80") (pin "1") (pinfunction "1_1") (pintype "passive"))
      (node (ref "R83") (pin "2") (pinfunction "2_2") (pintype "passive"))
    )
    (net (code "126") (name "Net-(R81-Pad2)") (class "Default")
      (node (ref "R81") (pin "2") (pinfunction "2_2") (pintype "passive"))
      (node (ref "R82") (pin "1") (pinfunction "1_1") (pintype "passive"))
      (node (ref "R83") (pin "1") (pinfunction "1_1") (pintype "passive"))
    )
    (net (code "127") (name "Net-(R84-Pad2)") (class "Default")
      (node (ref "R84") (pin "2") (pinfunction "2_2") (pintype "passive"))
      (node (ref "R85") (pin "1") (pinfunction "1_1") (pintype "passive"))
      (node (ref "R90") (pin "1") (pinfunction "1_1") (pintype "passive"))
    )
    (net (code "128") (name "Net-(R85-Pad2)") (class "Default")
      (node (ref "R85") (pin "2") (pinfunction "2_2") (pintype "passive"))
      (node (ref "R91") (pin "1") (pinfunction "1_1") (pintype "passive"))
      (node (ref "R92") (pin "2") (pinfunction "2_2") (pintype "passive"))
    )
    (net (code "129") (name "Net-(R100-Pad1)") (class "Default")
      (node (ref "R100") (pin "1") (pinfunction "1_1") (pintype "passive"))
      (node (ref "R101") (pin "1") (pinfunction "1_1") (pintype "passive"))
      (node (ref "R99") (pin "2") (pinfunction "2_2") (pintype "passive"))
    )
    (net (code "130") (name "Net-(R101-Pad2)") (class "Default")
      (node (ref "R101") (pin "2") (pinfunction "2_2") (pintype "passive"))
      (node (ref "R97") (pin "2") (pinfunction "2_2") (pintype "passive"))
      (node (ref "R98") (pin "1") (pinfunction "1_1") (pintype "passive"))
    )
    (net (code "131") (name "Net-(R102-Pad2)") (class "Default")
      (node (ref "R102") (pin "2") (pinfunction "2_2") (pintype "passive"))
      (node (ref "R103") (pin "1") (pinfunction "1_1") (pintype "passive"))
      (node (ref "R108") (pin "1") (pinfunction "1_1") (pintype "passive"))
    )
    (net (code "132") (name "Net-(R103-Pad2)") (class "Default")
      (node (ref "R103") (pin "2") (pinfunction "2_2") (pintype "passive"))
      (node (ref "R109") (pin "1") (pinfunction "1_1") (pintype "passive"))
      (node (ref "R110") (pin "2") (pinfunction "2_2") (pintype "passive"))
    )
    (net (code "133") (name "Net-(R115-Pad2)") (class "Default")
      (node (ref "R115") (pin "2") (pinfunction "2_2") (pintype "passive"))
      (node (ref "R116") (pin "1") (pinfunction "1_1") (pintype "passive"))
      (node (ref "R119") (pin "2") (pinfunction "2_2") (pintype "passive"))
    )
    (net (code "134") (name "Net-(R117-Pad2)") (class "Default")
      (node (ref "R117") (pin "2") (pinfunction "2_2") (pintype "passive"))
      (node (ref "R118") (pin "1") (pinfunction "1_1") (pintype "passive"))
      (node (ref "R119") (pin "1") (pinfunction "1_1") (pintype "passive"))
    )
    (net (code "135") (name "Net-(S1-A1)") (class "Default")
      (node (ref "R121") (pin "1") (pinfunction "1_1") (pintype "passive"))
      (node (ref "S1") (pin "1") (pinfunction "A1_1") (pintype "passive"))
    )
    (net (code "136") (name "Net-(S1-A2)") (class "Default")
      (node (ref "R129") (pin "1") (pinfunction "1_1") (pintype "passive"))
      (node (ref "S1") (pin "2") (pinfunction "A2_2") (pintype "passive"))
    )
    (net (code "137") (name "Net-(TP1-Test_Point)") (class "Default")
      (node (ref "+5J") (pin "1") (pinfunction "1_1") (pintype "passive"))
      (node (ref "C162") (pin "2") (pinfunction "2_2") (pintype "passive"))
      (node (ref "C163") (pin "2") (pinfunction "2_2") (pintype "passive"))
      (node (ref "L1") (pin "2") (pinfunction "2_2") (pintype "passive"))
      (node (ref "R128") (pin "2") (pinfunction "2_2") (pintype "passive"))
      (node (ref "TP1") (pin "TP") (pinfunction "Test_Point_TP") (pintype "passive"))
    )
    (net (code "138") (name "Net-(TP12-Test_Point)") (class "Default")
      (node (ref "C75") (pin "2") (pinfunction "2_2") (pintype "passive"))
      (node (ref "R35") (pin "2") (pinfunction "2_2") (pintype "passive"))
      (node (ref "R45") (pin "1") (pinfunction "1_1") (pintype "passive"))
      (node (ref "TP12") (pin "TP") (pinfunction "Test_Point_TP") (pintype "passive"))
      (node (ref "U9") (pin "7") (pinfunction "OUT2_7") (pintype "output"))
    )
    (net (code "139") (name "Net-(TP13-Test_Point)") (class "Default")
      (node (ref "C114") (pin "2") (pinfunction "2_2") (pintype "passive"))
      (node (ref "R89") (pin "2") (pinfunction "2_2") (pintype "passive"))
      (node (ref "R99") (pin "1") (pinfunction "1_1") (pintype "passive"))
      (node (ref "TP13") (pin "TP") (pinfunction "Test_Point_TP") (pintype "passive"))
      (node (ref "U12") (pin "7") (pinfunction "OUT2_7") (pintype "output"))
    )
    (net (code "140") (name "Net-(TP21-Test_Point)") (class "Default")
      (node (ref "C88") (pin "2") (pinfunction "2_2") (pintype "passive"))
      (node (ref "R53") (pin "2") (pinfunction "2_2") (pintype "passive"))
      (node (ref "R63") (pin "1") (pinfunction "1_1") (pintype "passive"))
      (node (ref "TP21") (pin "TP") (pinfunction "Test_Point_TP") (pintype "passive"))
      (node (ref "U7") (pin "7") (pinfunction "OUT2_7") (pintype "output"))
    )
    (net (code "141") (name "Net-(TP22-Test_Point)") (class "Default")
      (node (ref "C127") (pin "2") (pinfunction "2_2") (pintype "passive"))
      (node (ref "R107") (pin "2") (pinfunction "2_2") (pintype "passive"))
      (node (ref "R117") (pin "1") (pinfunction "1_1") (pintype "passive"))
      (node (ref "TP22") (pin "TP") (pinfunction "Test_Point_TP") (pintype "passive"))
      (node (ref "U11") (pin "7") (pinfunction "OUT2_7") (pintype "output"))
    )
    (net (code "142") (name "Net-(TP28-Test_Point)") (class "Default")
      (node (ref "+3V3J") (pin "1") (pinfunction "1_1") (pintype "passive"))
      (node (ref "C159") (pin "2") (pinfunction "2_2") (pintype "passive"))
      (node (ref "C160") (pin "2") (pinfunction "2_2") (pintype "passive"))
      (node (ref "L7") (pin "2") (pinfunction "2_2") (pintype "passive"))
      (node (ref "R125") (pin "2") (pinfunction "2_2") (pintype "passive"))
      (node (ref "TP28") (pin "TP") (pinfunction "Test_Point_TP") (pintype "passive"))
    )
    (net (code "143") (name "Net-(TP33-Test_Point)") (class "Default")
      (node (ref "-5VJ") (pin "1") (pinfunction "1_1") (pintype "passive"))
      (node (ref "C169") (pin "2") (pinfunction "2_2") (pintype "passive"))
      (node (ref "C170") (pin "2") (pinfunction "2_2") (pintype "passive"))
      (node (ref "C171") (pin "2") (pinfunction "2_2") (pintype "passive"))
      (node (ref "L4") (pin "2") (pinfunction "2_2") (pintype "passive"))
      (node (ref "TP33") (pin "TP") (pinfunction "Test_Point_TP") (pintype "passive"))
      (node (ref "U2") (pin "7") (pinfunction "VOUT_7") (pintype "input"))
    )
    (net (code "144") (name "Net-(TP34-Test_Point)") (class "Default")
      (node (ref "+1V2J") (pin "1") (pinfunction "1_1") (pintype "passive"))
      (node (ref "C165") (pin "2") (pinfunction "2_2") (pintype "passive"))
      (node (ref "C166") (pin "2") (pinfunction "2_2") (pintype "passive"))
      (node (ref "L6") (pin "2") (pinfunction "2_2") (pintype "passive"))
      (node (ref "R8") (pin "2") (pinfunction "2_2") (pintype "passive"))
      (node (ref "TP34") (pin "TP") (pinfunction "Test_Point_TP") (pintype "passive"))
    )
    (net (code "145") (name "Net-(TP35-Test_Point)") (class "Default")
      (node (ref "C55") (pin "2") (pinfunction "2_2") (pintype "passive"))
      (node (ref "R14") (pin "2") (pinfunction "2_2") (pintype "passive"))
      (node (ref "R25") (pin "1") (pinfunction "1_1") (pintype "passive"))
      (node (ref "TP35") (pin "TP") (pinfunction "Test_Point_TP") (pintype "passive"))
      (node (ref "U1") (pin "7") (pinfunction "OUT2_7") (pintype "output"))
    )
    (net (code "146") (name "Net-(TP36-Test_Point)") (class "Default")
      (node (ref "C101") (pin "2") (pinfunction "2_2") (pintype "passive"))
      (node (ref "R71") (pin "2") (pinfunction "2_2") (pintype "passive"))
      (node (ref "R81") (pin "1") (pinfunction "1_1") (pintype "passive"))
      (node (ref "TP36") (pin "TP") (pinfunction "Test_Point_TP") (pintype "passive"))
      (node (ref "U14") (pin "7") (pinfunction "OUT2_7") (pintype "output"))
    )
    (net (code "147") (name "Net-(TP40-Test_Point)") (class "Default")
      (node (ref "Audio Out") (pin "TB") (pinfunction "TB_TB") (pintype "passive"))
      (node (ref "TP40") (pin "TP") (pinfunction "Test_Point_TP") (pintype "passive"))
    )
    (net (code "148") (name "Net-(U1A-IN1+)") (class "Default")
      (node (ref "C53") (pin "1") (pinfunction "1_1") (pintype "passive"))
      (node (ref "R22") (pin "2") (pinfunction "2_2") (pintype "passive"))
      (node (ref "U1") (pin "3") (pinfunction "IN1+_3") (pintype "input"))
    )
    (net (code "149") (name "Net-(U1A-IN1-)") (class "Default")
      (node (ref "R11") (pin "2") (pinfunction "2_2") (pintype "passive"))
      (node (ref "R12") (pin "1") (pinfunction "1_1") (pintype "passive"))
      (node (ref "U1") (pin "2") (pinfunction "IN1-_2") (pintype "input"))
    )
    (net (code "150") (name "Net-(U1A-OUT1)") (class "Default")
      (node (ref "C54") (pin "2") (pinfunction "2_2") (pintype "passive"))
      (node (ref "R12") (pin "2") (pinfunction "2_2") (pintype "passive"))
      (node (ref "R19") (pin "1") (pinfunction "1_1") (pintype "passive"))
      (node (ref "U1") (pin "1") (pinfunction "OUT1_1") (pintype "output"))
    )
    (net (code "151") (name "Net-(U1B-IN2+)") (class "Default")
      (node (ref "C52") (pin "1") (pinfunction "1_1") (pintype "passive"))
      (node (ref "R20") (pin "2") (pinfunction "2_2") (pintype "passive"))
      (node (ref "U1") (pin "5") (pinfunction "IN2+_5") (pintype "input"))
    )
    (net (code "152") (name "Net-(U1B-IN2-)") (class "Default")
      (node (ref "R13") (pin "2") (pinfunction "2_2") (pintype "passive"))
      (node (ref "R14") (pin "1") (pinfunction "1_1") (pintype "passive"))
      (node (ref "U1") (pin "6") (pinfunction "IN2-_6") (pintype "input"))
    )
    (net (code "153") (name "Net-(U2-CAP)") (class "Default")
      (node (ref "C145") (pin "2") (pinfunction "2_2") (pintype "passive"))
      (node (ref "U2") (pin "6") (pinfunction "CAP_6") (pintype "passive"))
    )
    (net (code "154") (name "Net-(U2-CP)") (class "Default")
      (node (ref "C25") (pin "2") (pinfunction "2_2") (pintype "passive"))
      (node (ref "C47") (pin "2") (pinfunction "2_2") (pintype "passive"))
      (node (ref "C48") (pin "2") (pinfunction "2_2") (pintype "passive"))
      (node (ref "U2") (pin "11") (pinfunction "CP_11") (pintype "passive"))
    )
    (net (code "155") (name "Net-(U2-FB)") (class "Default")
      (node (ref "R2") (pin "1") (pinfunction "1_1") (pintype "passive"))
      (node (ref "R4") (pin "2") (pinfunction "2_2") (pintype "passive"))
      (node (ref "U2") (pin "5") (pinfunction "FB_5") (pintype "input"))
    )
    (net (code "156") (name "Net-(U2-PG)") (class "Default")
      (node (ref "R3") (pin "1") (pinfunction "1_1") (pintype "passive"))
      (node (ref "U2") (pin "3") (pinfunction "PG_3") (pintype "open_collector"))
    )
    (net (code "157") (name "Net-(U2-SW)") (class "Default")
      (node (ref "C25") (pin "1") (pinfunction "1_1") (pintype "passive"))
      (node (ref "C47") (pin "1") (pinfunction "1_1") (pintype "passive"))
      (node (ref "C48") (pin "1") (pinfunction "1_1") (pintype "passive"))
      (node (ref "L4") (pin "1") (pinfunction "1_1") (pintype "passive"))
      (node (ref "U2") (pin "8") (pinfunction "SW_8") (pintype "power_in"))
    )
    (net (code "158") (name "Net-(U2-VAUX)") (class "Default")
      (node (ref "C172") (pin "2") (pinfunction "2_2") (pintype "passive"))
      (node (ref "U2") (pin "1") (pinfunction "VAUX_1") (pintype "input"))
    )
    (net (code "159") (name "Net-(U2-VREF)") (class "Default")
      (node (ref "R2") (pin "2") (pinfunction "2_2") (pintype "passive"))
      (node (ref "U2") (pin "4") (pinfunction "VREF_4") (pintype "output"))
    )
    (net (code "160") (name "Net-(U3A-IN+)") (class "Default")
      (node (ref "C41") (pin "1") (pinfunction "1_1") (pintype "passive"))
      (node (ref "C42") (pin "1") (pinfunction "1_1") (pintype "passive"))
      (node (ref "R5") (pin "1") (pinfunction "1_1") (pintype "passive"))
      (node (ref "U3") (pin "3") (pinfunction "IN+_3") (pintype "input"))
      (node (ref "U5") (pin "3") (pinfunction "IN+_3") (pintype "input"))
    )
    (net (code "161") (name "Net-(U4A-TRIM{slash}NR)") (class "Default")
      (node (ref "C43") (pin "1") (pinfunction "1_1") (pintype "passive"))
      (node (ref "U4") (pin "5") (pinfunction "TRIM/NR_5") (pintype "input"))
    )
    (net (code "162") (name "Net-(U6-VIN+)") (class "Default")
      (node (ref "C50") (pin "2") (pinfunction "2_2") (pintype "passive"))
      (node (ref "R26") (pin "2") (pinfunction "2_2") (pintype "passive"))
      (node (ref "U6") (pin "8") (pinfunction "VIN+_8") (pintype "input"))
    )
    (net (code "163") (name "Net-(U6-VIN-)") (class "Default")
      (node (ref "C50") (pin "1") (pinfunction "1_1") (pintype "passive"))
      (node (ref "R16") (pin "2") (pinfunction "2_2") (pintype "passive"))
      (node (ref "U6") (pin "1") (pinfunction "VIN-_1") (pintype "input"))
    )
    (net (code "164") (name "Net-(U6-VOUT+)") (class "Default")
      (node (ref "R18") (pin "1") (pinfunction "1_1") (pintype "passive"))
      (node (ref "U6") (pin "4") (pinfunction "VOUT+_4") (pintype "output"))
    )
    (net (code "165") (name "Net-(U6-VOUT-)") (class "Default")
      (node (ref "R23") (pin "1") (pinfunction "1_1") (pintype "passive"))
      (node (ref "U6") (pin "5") (pinfunction "VOUT-_5") (pintype "output"))
    )
    (net (code "166") (name "Net-(U7A-IN1+)") (class "Default")
      (node (ref "C83") (pin "1") (pinfunction "1_1") (pintype "passive"))
      (node (ref "R60") (pin "2") (pinfunction "2_2") (pintype "passive"))
      (node (ref "U7") (pin "3") (pinfunction "IN1+_3") (pintype "input"))
    )
    (net (code "167") (name "Net-(U7A-IN1-)") (class "Default")
      (node (ref "R50") (pin "2") (pinfunction "2_2") (pintype "passive"))
      (node (ref "R51") (pin "1") (pinfunction "1_1") (pintype "passive"))
      (node (ref "U7") (pin "2") (pinfunction "IN1-_2") (pintype "input"))
    )
    (net (code "168") (name "Net-(U7A-OUT1)") (class "Default")
      (node (ref "C87") (pin "2") (pinfunction "2_2") (pintype "passive"))
      (node (ref "R51") (pin "2") (pinfunction "2_2") (pintype "passive"))
      (node (ref "R57") (pin "1") (pinfunction "1_1") (pintype "passive"))
      (node (ref "U7") (pin "1") (pinfunction "OUT1_1") (pintype "output"))
    )
    (net (code "169") (name "Net-(U7B-IN2+)") (class "Default")
      (node (ref "C82") (pin "1") (pinfunction "1_1") (pintype "passive"))
      (node (ref "R58") (pin "2") (pinfunction "2_2") (pintype "passive"))
      (node (ref "U7") (pin "5") (pinfunction "IN2+_5") (pintype "input"))
    )
    (net (code "170") (name "Net-(U7B-IN2-)") (class "Default")
      (node (ref "R52") (pin "2") (pinfunction "2_2") (pintype "passive"))
      (node (ref "R53") (pin "1") (pinfunction "1_1") (pintype "passive"))
      (node (ref "U7") (pin "6") (pinfunction "IN2-_6") (pintype "input"))
    )
    (net (code "171") (name "Net-(U8-VIN+)") (class "Default")
      (node (ref "C67") (pin "2") (pinfunction "2_2") (pintype "passive"))
      (node (ref "R46") (pin "2") (pinfunction "2_2") (pintype "passive"))
      (node (ref "U8") (pin "8") (pinfunction "VIN+_8") (pintype "input"))
    )
    (net (code "172") (name "Net-(U8-VIN-)") (class "Default")
      (node (ref "C67") (pin "1") (pinfunction "1_1") (pintype "passive"))
      (node (ref "R36") (pin "2") (pinfunction "2_2") (pintype "passive"))
      (node (ref "U8") (pin "1") (pinfunction "VIN-_1") (pintype "input"))
    )
    (net (code "173") (name "Net-(U8-VOUT+)") (class "Default")
      (node (ref "R38") (pin "1") (pinfunction "1_1") (pintype "passive"))
      (node (ref "U8") (pin "4") (pinfunction "VOUT+_4") (pintype "output"))
    )
    (net (code "174") (name "Net-(U8-VOUT-)") (class "Default")
      (node (ref "R43") (pin "1") (pinfunction "1_1") (pintype "passive"))
      (node (ref "U8") (pin "5") (pinfunction "VOUT-_5") (pintype "output"))
    )
    (net (code "175") (name "Net-(U9A-IN1+)") (class "Default")
      (node (ref "C70") (pin "1") (pinfunction "1_1") (pintype "passive"))
      (node (ref "R42") (pin "2") (pinfunction "2_2") (pintype "passive"))
      (node (ref "U9") (pin "3") (pinfunction "IN1+_3") (pintype "input"))
    )
    (net (code "176") (name "Net-(U9A-IN1-)") (class "Default")
      (node (ref "R32") (pin "2") (pinfunction "2_2") (pintype "passive"))
      (node (ref "R33") (pin "1") (pinfunction "1_1") (pintype "passive"))
      (node (ref "U9") (pin "2") (pinfunction "IN1-_2") (pintype "input"))
    )
    (net (code "177") (name "Net-(U9A-OUT1)") (class "Default")
      (node (ref "C74") (pin "2") (pinfunction "2_2") (pintype "passive"))
      (node (ref "R33") (pin "2") (pinfunction "2_2") (pintype "passive"))
      (node (ref "R39") (pin "1") (pinfunction "1_1") (pintype "passive"))
      (node (ref "U9") (pin "1") (pinfunction "OUT1_1") (pintype "output"))
    )
    (net (code "178") (name "Net-(U9B-IN2+)") (class "Default")
      (node (ref "C69") (pin "1") (pinfunction "1_1") (pintype "passive"))
      (node (ref "R40") (pin "2") (pinfunction "2_2") (pintype "passive"))
      (node (ref "U9") (pin "5") (pinfunction "IN2+_5") (pintype "input"))
    )
    (net (code "179") (name "Net-(U9B-IN2-)") (class "Default")
      (node (ref "R34") (pin "2") (pinfunction "2_2") (pintype "passive"))
      (node (ref "R35") (pin "1") (pinfunction "1_1") (pintype "passive"))
      (node (ref "U9") (pin "6") (pinfunction "IN2-_6") (pintype "input"))
    )
    (net (code "180") (name "Net-(U10-VIN+)") (class "Default")
      (node (ref "C80") (pin "2") (pinfunction "2_2") (pintype "passive"))
      (node (ref "R64") (pin "2") (pinfunction "2_2") (pintype "passive"))
      (node (ref "U10") (pin "8") (pinfunction "VIN+_8") (pintype "input"))
    )
    (net (code "181") (name "Net-(U10-VIN-)") (class "Default")
      (node (ref "C80") (pin "1") (pinfunction "1_1") (pintype "passive"))
      (node (ref "R54") (pin "2") (pinfunction "2_2") (pintype "passive"))
      (node (ref "U10") (pin "1") (pinfunction "VIN-_1") (pintype "input"))
    )
    (net (code "182") (name "Net-(U10-VOUT+)") (class "Default")
      (node (ref "R56") (pin "1") (pinfunction "1_1") (pintype "passive"))
      (node (ref "U10") (pin "4") (pinfunction "VOUT+_4") (pintype "output"))
    )
    (net (code "183") (name "Net-(U10-VOUT-)") (class "Default")
      (node (ref "R61") (pin "1") (pinfunction "1_1") (pintype "passive"))
      (node (ref "U10") (pin "5") (pinfunction "VOUT-_5") (pintype "output"))
    )
    (net (code "184") (name "Net-(U11A-IN1+)") (class "Default")
      (node (ref "C122") (pin "1") (pinfunction "1_1") (pintype "passive"))
      (node (ref "R114") (pin "2") (pinfunction "2_2") (pintype "passive"))
      (node (ref "U11") (pin "3") (pinfunction "IN1+_3") (pintype "input"))
    )
    (net (code "185") (name "Net-(U11A-IN1-)") (class "Default")
      (node (ref "R104") (pin "2") (pinfunction "2_2") (pintype "passive"))
      (node (ref "R105") (pin "1") (pinfunction "1_1") (pintype "passive"))
      (node (ref "U11") (pin "2") (pinfunction "IN1-_2") (pintype "input"))
    )
    (net (code "186") (name "Net-(U11A-OUT1)") (class "Default")
      (node (ref "C126") (pin "2") (pinfunction "2_2") (pintype "passive"))
      (node (ref "R105") (pin "2") (pinfunction "2_2") (pintype "passive"))
      (node (ref "R111") (pin "1") (pinfunction "1_1") (pintype "passive"))
      (node (ref "U11") (pin "1") (pinfunction "OUT1_1") (pintype "output"))
    )
    (net (code "187") (name "Net-(U11B-IN2+)") (class "Default")
      (node (ref "C121") (pin "1") (pinfunction "1_1") (pintype "passive"))
      (node (ref "R112") (pin "2") (pinfunction "2_2") (pintype "passive"))
      (node (ref "U11") (pin "5") (pinfunction "IN2+_5") (pintype "input"))
    )
    (net (code "188") (name "Net-(U11B-IN2-)") (class "Default")
      (node (ref "R106") (pin "2") (pinfunction "2_2") (pintype "passive"))
      (node (ref "R107") (pin "1") (pinfunction "1_1") (pintype "passive"))
      (node (ref "U11") (pin "6") (pinfunction "IN2-_6") (pintype "input"))
    )
    (net (code "189") (name "Net-(U12A-IN1+)") (class "Default")
      (node (ref "C109") (pin "1") (pinfunction "1_1") (pintype "passive"))
      (node (ref "R96") (pin "2") (pinfunction "2_2") (pintype "passive"))
      (node (ref "U12") (pin "3") (pinfunction "IN1+_3") (pintype "input"))
    )
    (net (code "190") (name "Net-(U12A-IN1-)") (class "Default")
      (node (ref "R86") (pin "2") (pinfunction "2_2") (pintype "passive"))
      (node (ref "R87") (pin "1") (pinfunction "1_1") (pintype "passive"))
      (node (ref "U12") (pin "2") (pinfunction "IN1-_2") (pintype "input"))
    )
    (net (code "191") (name "Net-(U12A-OUT1)") (class "Default")
      (node (ref "C113") (pin "2") (pinfunction "2_2") (pintype "passive"))
      (node (ref "R87") (pin "2") (pinfunction "2_2") (pintype "passive"))
      (node (ref "R93") (pin "1") (pinfunction "1_1") (pintype "passive"))
      (node (ref "U12") (pin "1") (pinfunction "OUT1_1") (pintype "output"))
    )
    (net (code "192") (name "Net-(U12B-IN2+)") (class "Default")
      (node (ref "C108") (pin "1") (pinfunction "1_1") (pintype "passive"))
      (node (ref "R94") (pin "2") (pinfunction "2_2") (pintype "passive"))
      (node (ref "U12") (pin "5") (pinfunction "IN2+_5") (pintype "input"))
    )
    (net (code "193") (name "Net-(U12B-IN2-)") (class "Default")
      (node (ref "R88") (pin "2") (pinfunction "2_2") (pintype "passive"))
      (node (ref "R89") (pin "1") (pinfunction "1_1") (pintype "passive"))
      (node (ref "U12") (pin "6") (pinfunction "IN2-_6") (pintype "input"))
    )
    (net (code "194") (name "Net-(U13-VIN+)") (class "Default")
      (node (ref "C93") (pin "2") (pinfunction "2_2") (pintype "passive"))
      (node (ref "R82") (pin "2") (pinfunction "2_2") (pintype "passive"))
      (node (ref "U13") (pin "8") (pinfunction "VIN+_8") (pintype "input"))
    )
    (net (code "195") (name "Net-(U13-VIN-)") (class "Default")
      (node (ref "C93") (pin "1") (pinfunction "1_1") (pintype "passive"))
      (node (ref "R72") (pin "2") (pinfunction "2_2") (pintype "passive"))
      (node (ref "U13") (pin "1") (pinfunction "VIN-_1") (pintype "input"))
    )
    (net (code "196") (name "Net-(U13-VOUT+)") (class "Default")
      (node (ref "R74") (pin "1") (pinfunction "1_1") (pintype "passive"))
      (node (ref "U13") (pin "4") (pinfunction "VOUT+_4") (pintype "output"))
    )
    (net (code "197") (name "Net-(U13-VOUT-)") (class "Default")
      (node (ref "R79") (pin "1") (pinfunction "1_1") (pintype "passive"))
      (node (ref "U13") (pin "5") (pinfunction "VOUT-_5") (pintype "output"))
    )
    (net (code "198") (name "Net-(U14A-IN1+)") (class "Default")
      (node (ref "C96") (pin "1") (pinfunction "1_1") (pintype "passive"))
      (node (ref "R78") (pin "2") (pinfunction "2_2") (pintype "passive"))
      (node (ref "U14") (pin "3") (pinfunction "IN1+_3") (pintype "input"))
    )
    (net (code "199") (name "Net-(U14A-IN1-)") (class "Default")
      (node (ref "R68") (pin "2") (pinfunction "2_2") (pintype "passive"))
      (node (ref "R69") (pin "1") (pinfunction "1_1") (pintype "passive"))
      (node (ref "U14") (pin "2") (pinfunction "IN1-_2") (pintype "input"))
    )
    (net (code "200") (name "Net-(U14A-OUT1)") (class "Default")
      (node (ref "C100") (pin "2") (pinfunction "2_2") (pintype "passive"))
      (node (ref "R69") (pin "2") (pinfunction "2_2") (pintype "passive"))
      (node (ref "R75") (pin "1") (pinfunction "1_1") (pintype "passive"))
      (node (ref "U14") (pin "1") (pinfunction "OUT1_1") (pintype "output"))
    )
    (net (code "201") (name "Net-(U14B-IN2+)") (class "Default")
      (node (ref "C95") (pin "1") (pinfunction "1_1") (pintype "passive"))
      (node (ref "R76") (pin "2") (pinfunction "2_2") (pintype "passive"))
      (node (ref "U14") (pin "5") (pinfunction "IN2+_5") (pintype "input"))
    )
    (net (code "202") (name "Net-(U14B-IN2-)") (class "Default")
      (node (ref "R70") (pin "2") (pinfunction "2_2") (pintype "passive"))
      (node (ref "R71") (pin "1") (pinfunction "1_1") (pintype "passive"))
      (node (ref "U14") (pin "6") (pinfunction "IN2-_6") (pintype "input"))
    )
    (net (code "203") (name "Net-(U15-VIN+)") (class "Default")
      (node (ref "C106") (pin "2") (pinfunction "2_2") (pintype "passive"))
      (node (ref "R100") (pin "2") (pinfunction "2_2") (pintype "passive"))
      (node (ref "U15") (pin "8") (pinfunction "VIN+_8") (pintype "input"))
    )
    (net (code "204") (name "Net-(U15-VIN-)") (class "Default")
      (node (ref "C106") (pin "1") (pinfunction "1_1") (pintype "passive"))
      (node (ref "R90") (pin "2") (pinfunction "2_2") (pintype "passive"))
      (node (ref "U15") (pin "1") (pinfunction "VIN-_1") (pintype "input"))
    )
    (net (code "205") (name "Net-(U15-VOUT+)") (class "Default")
      (node (ref "R92") (pin "1") (pinfunction "1_1") (pintype "passive"))
      (node (ref "U15") (pin "4") (pinfunction "VOUT+_4") (pintype "output"))
    )
    (net (code "206") (name "Net-(U15-VOUT-)") (class "Default")
      (node (ref "R97") (pin "1") (pinfunction "1_1") (pintype "passive"))
      (node (ref "U15") (pin "5") (pinfunction "VOUT-_5") (pintype "output"))
    )
    (net (code "207") (name "Net-(U17-VIN+)") (class "Default")
      (node (ref "C119") (pin "2") (pinfunction "2_2") (pintype "passive"))
      (node (ref "R118") (pin "2") (pinfunction "2_2") (pintype "passive"))
      (node (ref "U17") (pin "8") (pinfunction "VIN+_8") (pintype "input"))
    )
    (net (code "208") (name "Net-(U17-VIN-)") (class "Default")
      (node (ref "C119") (pin "1") (pinfunction "1_1") (pintype "passive"))
      (node (ref "R108") (pin "2") (pinfunction "2_2") (pintype "passive"))
      (node (ref "U17") (pin "1") (pinfunction "VIN-_1") (pintype "input"))
    )
    (net (code "209") (name "Net-(U17-VOUT+)") (class "Default")
      (node (ref "R110") (pin "1") (pinfunction "1_1") (pintype "passive"))
      (node (ref "U17") (pin "4") (pinfunction "VOUT+_4") (pintype "output"))
    )
    (net (code "210") (name "Net-(U17-VOUT-)") (class "Default")
      (node (ref "R115") (pin "1") (pinfunction "1_1") (pintype "passive"))
      (node (ref "U17") (pin "5") (pinfunction "VOUT-_5") (pintype "output"))
    )
    (net (code "211") (name "Net-(U21-EN)") (class "Default")
      (node (ref "R127") (pin "1") (pinfunction "1_1") (pintype "passive"))
      (node (ref "U21") (pin "5") (pinfunction "EN_5") (pintype "input"))
    )
    (net (code "212") (name "Net-(U21-SW)") (class "Default")
      (node (ref "C161") (pin "2") (pinfunction "2_2") (pintype "passive"))
      (node (ref "L1") (pin "1") (pinfunction "1_1") (pintype "passive"))
      (node (ref "U21") (pin "2") (pinfunction "SW_2") (pintype "passive"))
    )
    (net (code "213") (name "Net-(U21-VBST)") (class "Default")
      (node (ref "C161") (pin "1") (pinfunction "1_1") (pintype "passive"))
      (node (ref "U21") (pin "6") (pinfunction "VBST_6") (pintype "passive"))
    )
    (net (code "214") (name "Net-(U21-VFB)") (class "Default")
      (node (ref "R128") (pin "1") (pinfunction "1_1") (pintype "passive"))
      (node (ref "R145") (pin "2") (pinfunction "2_2") (pintype "passive"))
      (node (ref "U21") (pin "4") (pinfunction "VFB_4") (pintype "input"))
    )
    (net (code "215") (name "Net-(U22-EN)") (class "Default")
      (node (ref "R144") (pin "1") (pinfunction "1_1") (pintype "passive"))
      (node (ref "U22") (pin "5") (pinfunction "EN_5") (pintype "input"))
    )
    (net (code "216") (name "Net-(U22-SW)") (class "Default")
      (node (ref "C140") (pin "2") (pinfunction "2_2") (pintype "passive"))
      (node (ref "L7") (pin "1") (pinfunction "1_1") (pintype "passive"))
      (node (ref "U22") (pin "2") (pinfunction "SW_2") (pintype "passive"))
    )
    (net (code "217") (name "Net-(U22-VBST)") (class "Default")
      (node (ref "C140") (pin "1") (pinfunction "1_1") (pintype "passive"))
      (node (ref "U22") (pin "6") (pinfunction "VBST_6") (pintype "passive"))
    )
    (net (code "218") (name "Net-(U22-VFB)") (class "Default")
      (node (ref "R125") (pin "1") (pinfunction "1_1") (pintype "passive"))
      (node (ref "R126") (pin "2") (pinfunction "2_2") (pintype "passive"))
      (node (ref "U22") (pin "4") (pinfunction "VFB_4") (pintype "input"))
    )
    (net (code "219") (name "Net-(U24-EN)") (class "Default")
      (node (ref "R146") (pin "1") (pinfunction "1_1") (pintype "passive"))
      (node (ref "U24") (pin "5") (pinfunction "EN_5") (pintype "input"))
    )
    (net (code "220") (name "Net-(U24-SW)") (class "Default")
      (node (ref "C147") (pin "1") (pinfunction "1_1") (pintype "passive"))
      (node (ref "L6") (pin "1") (pinfunction "1_1") (pintype "passive"))
      (node (ref "U24") (pin "2") (pinfunction "SW_2") (pintype "power_in"))
    )
    (net (code "221") (name "Net-(U24-VBST)") (class "Default")
      (node (ref "C147") (pin "2") (pinfunction "2_2") (pintype "passive"))
      (node (ref "U24") (pin "6") (pinfunction "VBST_6") (pintype "power_in"))
    )
    (net (code "222") (name "Net-(U24-VFB)") (class "Default")
      (node (ref "R8") (pin "1") (pinfunction "1_1") (pintype "passive"))
      (node (ref "R9") (pin "2") (pinfunction "2_2") (pintype "passive"))
      (node (ref "U24") (pin "4") (pinfunction "VFB_4") (pintype "input"))
    )
    (net (code "223") (name "Net-(U25A-IN1-)") (class "Default")
      (node (ref "R10") (pin "2") (pinfunction "2_2") (pintype "passive"))
      (node (ref "R133") (pin "1") (pinfunction "1_1") (pintype "passive"))
      (node (ref "R134") (pin "2") (pinfunction "2_2") (pintype "passive"))
      (node (ref "R135") (pin "2") (pinfunction "2_2") (pintype "passive"))
      (node (ref "R137") (pin "2") (pinfunction "2_2") (pintype "passive"))
      (node (ref "R138") (pin "2") (pinfunction "2_2") (pintype "passive"))
      (node (ref "R139") (pin "2") (pinfunction "2_2") (pintype "passive"))
      (node (ref "U25") (pin "2") (pinfunction "IN1-_2") (pintype "input"))
    )
    (net (code "224") (name "Net-(U25A-OUT1)") (class "Default")
      (node (ref "C141") (pin "1") (pinfunction "1_1") (pintype "passive"))
      (node (ref "R133") (pin "2") (pinfunction "2_2") (pintype "passive"))
      (node (ref "U25") (pin "1") (pinfunction "OUT1_1") (pintype "output"))
    )
    (net (code "225") (name "Net-(U25B-IN2-)") (class "Default")
      (node (ref "U25") (pin "6") (pinfunction "IN2-_6") (pintype "input"))
      (node (ref "U25") (pin "7") (pinfunction "OUT2_7") (pintype "output"))
    )
    (net (code "226") (name "STARGND") (class "Default")
      (node (ref "12V Input") (pin "2") (pinfunction "2_2") (pintype "passive"))
      (node (ref "12V Input") (pin "3") (pinfunction "3_3") (pintype "passive"))
      (node (ref "C138") (pin "1") (pinfunction "1_1") (pintype "passive"))
      (node (ref "C49") (pin "2") (pinfunction "2_2") (pintype "passive"))
      (node (ref "D1") (pin "2") (pinfunction "K_2") (pintype "passive"))
      (node (ref "D2") (pin "1") (pinfunction "A_1") (pintype "passive"))
      (node (ref "D3") (pin "1") (pinfunction "A_1") (pintype "passive"))
      (node (ref "D4") (pin "2") (pinfunction "K_2") (pintype "passive"))
    )
    (net (code "227") (name "unconnected-(12V AGND-Pad4)") (class "Default")
      (node (ref "12V AGND") (pin "4") (pinfunction "4_4") (pintype "passive"))
    )
    (net (code "228") (name "unconnected-(12V AGND-Pad5)") (class "Default")
      (node (ref "12V AGND") (pin "5") (pinfunction "5_5") (pintype "passive"))
    )
    (net (code "229") (name "unconnected-(Ethernet Port-D3-Pad3)") (class "Default")
      (node (ref "Ethernet Port") (pin "3") (pinfunction "D3_3") (pintype "passive"))
    )
    (net (code "230") (name "unconnected-(Ethernet Port-D4-Pad4)") (class "Default")
      (node (ref "Ethernet Port") (pin "4") (pinfunction "D4_4") (pintype "passive"))
    )
    (net (code "231") (name "unconnected-(Ethernet Port-D5-Pad5)") (class "Default")
      (node (ref "Ethernet Port") (pin "5") (pinfunction "D5_5") (pintype "passive"))
    )
    (net (code "232") (name "unconnected-(Ethernet Port-D6-Pad6)") (class "Default")
      (node (ref "Ethernet Port") (pin "6") (pinfunction "D6_6") (pintype "passive"))
    )
    (net (code "233") (name "unconnected-(FTDI USB UART-CBUS2-Pad13)") (class "Default")
      (node (ref "FTDI USB UART") (pin "13") (pinfunction "CBUS2_13") (pintype "passive"))
    )
    (net (code "234") (name "unconnected-(FTDI USB UART-CBUS3-Pad14)") (class "Default")
      (node (ref "FTDI USB UART") (pin "14") (pinfunction "CBUS3_14") (pintype "passive"))
    )
    (net (code "235") (name "unconnected-(FTDI USB UART-CBUS4-Pad12)") (class "Default")
      (node (ref "FTDI USB UART") (pin "12") (pinfunction "CBUS4_12") (pintype "passive"))
    )
    (net (code "236") (name "unconnected-(FTDI USB UART-DCD#-Pad10)") (class "Default")
      (node (ref "FTDI USB UART") (pin "10") (pinfunction "DCD#_10") (pintype "passive"))
    )
    (net (code "237") (name "unconnected-(FTDI USB UART-DSR#-Pad9)") (class "Default")
      (node (ref "FTDI USB UART") (pin "9") (pinfunction "DSR#_9") (pintype "passive"))
    )
    (net (code "238") (name "unconnected-(FTDI USB UART-DTR#-Pad2)") (class "Default")
      (node (ref "FTDI USB UART") (pin "2") (pinfunction "DTR#_2") (pintype "passive"))
    )
    (net (code "239") (name "unconnected-(FTDI USB UART-NC-Pad8)") (class "Default")
      (node (ref "FTDI USB UART") (pin "8") (pinfunction "NC_8") (pintype "passive"))
    )
    (net (code "240") (name "unconnected-(FTDI USB UART-NC-Pad24)") (class "Default")
      (node (ref "FTDI USB UART") (pin "24") (pinfunction "NC_24") (pintype "passive"))
    )
    (net (code "241") (name "unconnected-(FTDI USB UART-OSCI-Pad27)") (class "Default")
      (node (ref "FTDI USB UART") (pin "27") (pinfunction "OSCI_27") (pintype "passive"))
    )
    (net (code "242") (name "unconnected-(FTDI USB UART-OSCO-Pad28)") (class "Default")
      (node (ref "FTDI USB UART") (pin "28") (pinfunction "OSCO_28") (pintype "passive"))
    )
    (net (code "243") (name "unconnected-(FTDI USB UART-RESET#-Pad19)") (class "Default")
      (node (ref "FTDI USB UART") (pin "19") (pinfunction "RESET#_19") (pintype "passive"))
    )
    (net (code "244") (name "unconnected-(FTDI USB UART-RI#-Pad6)") (class "Default")
      (node (ref "FTDI USB UART") (pin "6") (pinfunction "RI#_6") (pintype "passive"))
    )
    (net (code "245") (name "unconnected-(Foot Switch-Output1-Pad2)") (class "Default")
      (node (ref "Foot Switch") (pin "2") (pinfunction "Output1_2") (pintype "passive"))
    )
    (net (code "246") (name "unconnected-(GPIO Breakout-Pad22)") (class "Default")
      (node (ref "GPIO Breakout") (pin "22") (pinfunction "22_22") (pintype "passive"))
    )
    (net (code "247") (name "unconnected-(JTAG-Pad6)") (class "Default")
      (node (ref "JTAG") (pin "6") (pinfunction "6_6") (pintype "passive"))
    )
    (net (code "248") (name "unconnected-(MINI USB-NC-Pad4)") (class "Default")
      (node (ref "MINI USB") (pin "4") (pinfunction "NC_4") (pintype "passive"))
    )
    (net (code "249") (name "unconnected-(S1-A3-Pad3)") (class "Default")
      (node (ref "S1") (pin "3") (pinfunction "A3_3") (pintype "passive"))
    )
    (net (code "250") (name "unconnected-(S1-B3-Pad4)") (class "Default")
      (node (ref "S1") (pin "4") (pinfunction "B3_4") (pintype "passive"))
    )
    (net (code "251") (name "unconnected-(Transceiver Out-2D-Pad3)") (class "Default")
      (node (ref "Transceiver Out") (pin "3") (pinfunction "2D_3") (pintype "passive"))
    )
    (net (code "252") (name "unconnected-(Transceiver Out-2Y-Pad18)") (class "Default")
      (node (ref "Transceiver Out") (pin "18") (pinfunction "2Y_18") (pintype "passive"))
    )
    (net (code "253") (name "unconnected-(Transceiver Out-2Z-Pad17)") (class "Default")
      (node (ref "Transceiver Out") (pin "17") (pinfunction "2Z_17") (pintype "passive"))
    )
    (net (code "254") (name "unconnected-(Transceiver Out-3D-Pad5)") (class "Default")
      (node (ref "Transceiver Out") (pin "5") (pinfunction "3D_5") (pintype "passive"))
    )
    (net (code "255") (name "unconnected-(Transceiver Out-3Y-Pad16)") (class "Default")
      (node (ref "Transceiver Out") (pin "16") (pinfunction "3Y_16") (pintype "passive"))
    )
    (net (code "256") (name "unconnected-(Transceiver Out-3Z-Pad15)") (class "Default")
      (node (ref "Transceiver Out") (pin "15") (pinfunction "3Z_15") (pintype "passive"))
    )
    (net (code "257") (name "unconnected-(Transceiver Out-5A-Pad12)") (class "Default")
      (node (ref "Transceiver Out") (pin "12") (pinfunction "5A_12") (pintype "passive"))
    )
    (net (code "258") (name "unconnected-(Transceiver Out-5B-Pad11)") (class "Default")
      (node (ref "Transceiver Out") (pin "11") (pinfunction "5B_11") (pintype "passive"))
    )
    (net (code "259") (name "unconnected-(Transceiver Out-5R-Pad9)") (class "Default")
      (node (ref "Transceiver Out") (pin "9") (pinfunction "5R_9") (pintype "passive"))
    )
    (net (code "260") (name "unconnected-(U3B-NC-Pad1)") (class "Default")
      (node (ref "U3") (pin "1") (pinfunction "NC_1") (pintype "passive"))
    )
    (net (code "261") (name "unconnected-(U3B-NC-Pad5)") (class "Default")
      (node (ref "U3") (pin "5") (pinfunction "NC_5") (pintype "passive"))
    )
    (net (code "262") (name "unconnected-(U3B-NC-Pad8)") (class "Default")
      (node (ref "U3") (pin "8") (pinfunction "NC_8") (pintype "passive"))
    )
    (net (code "263") (name "unconnected-(U4A-TEMP-Pad3)") (class "Default")
      (node (ref "U4") (pin "3") (pinfunction "TEMP_3") (pintype "output"))
    )
    (net (code "264") (name "unconnected-(U4B-DNC-Pad1)") (class "Default")
      (node (ref "U4") (pin "1") (pinfunction "DNC_1") (pintype "passive"))
    )
    (net (code "265") (name "unconnected-(U4B-DNC-Pad8)") (class "Default")
      (node (ref "U4") (pin "8") (pinfunction "DNC_8") (pintype "passive"))
    )
    (net (code "266") (name "unconnected-(U4B-NC-Pad7)") (class "Default")
      (node (ref "U4") (pin "7") (pinfunction "NC_7") (pintype "passive"))
    )
    (net (code "267") (name "unconnected-(U5B-NC-Pad1)") (class "Default")
      (node (ref "U5") (pin "1") (pinfunction "NC_1") (pintype "passive"))
    )
    (net (code "268") (name "unconnected-(U5B-NC-Pad5)") (class "Default")
      (node (ref "U5") (pin "5") (pinfunction "NC_5") (pintype "passive"))
    )
    (net (code "269") (name "unconnected-(U5B-NC-Pad8)") (class "Default")
      (node (ref "U5") (pin "8") (pinfunction "NC_8") (pintype "passive"))
    )
    (net (code "270") (name "unconnected-(U19A-ADCIN14-Pad44)") (class "Default")
      (node (ref "U19") (pin "44") (pinfunction "ADCIN14_44") (pintype "passive"))
    )
    (net (code "271") (name "unconnected-(U19A-ADCIN15-Pad45)") (class "Default")
      (node (ref "U19") (pin "45") (pinfunction "ADCIN15_45") (pintype "passive"))
    )
    (net (code "272") (name "unconnected-(U19A-ADCINA4-Pad39)") (class "Default")
      (node (ref "U19") (pin "39") (pinfunction "ADCINA4_39") (pintype "passive"))
    )
    (net (code "273") (name "unconnected-(U19A-ADCINA5-Pad38)") (class "Default")
      (node (ref "U19") (pin "38") (pinfunction "ADCINA5_38") (pintype "passive"))
    )
    (net (code "274") (name "unconnected-(U19A-ADCINB2-Pad48)") (class "Default")
      (node (ref "U19") (pin "48") (pinfunction "ADCINB2_48") (pintype "passive"))
    )
    (net (code "275") (name "unconnected-(U19A-ADCINB3-Pad49)") (class "Default")
      (node (ref "U19") (pin "49") (pinfunction "ADCINB3_49") (pintype "passive"))
    )
    (net (code "276") (name "unconnected-(U19A-ADCINC4-Pad29)") (class "Default")
      (node (ref "U19") (pin "29") (pinfunction "ADCINC4_29") (pintype "passive"))
    )
    (net (code "277") (name "unconnected-(U19A-ADCIND4-Pad60)") (class "Default")
      (node (ref "U19") (pin "60") (pinfunction "ADCIND4_60") (pintype "passive"))
    )
    (net (code "278") (name "unconnected-(U19B-GPIO0-Pad160)") (class "Default")
      (node (ref "U19") (pin "160") (pinfunction "GPIO0_160") (pintype "bidirectional"))
    )
    (net (code "279") (name "unconnected-(U19B-GPIO1-Pad161)") (class "Default")
      (node (ref "U19") (pin "161") (pinfunction "GPIO1_161") (pintype "bidirectional"))
    )
    (net (code "280") (name "unconnected-(U19B-GPIO2-Pad162)") (class "Default")
      (node (ref "U19") (pin "162") (pinfunction "GPIO2_162") (pintype "bidirectional"))
    )
    (net (code "281") (name "unconnected-(U19B-GPIO3-Pad163)") (class "Default")
      (node (ref "U19") (pin "163") (pinfunction "GPIO3_163") (pintype "bidirectional"))
    )
    (net (code "282") (name "unconnected-(U19B-GPIO4-Pad164)") (class "Default")
      (node (ref "U19") (pin "164") (pinfunction "GPIO4_164") (pintype "bidirectional"))
    )
    (net (code "283") (name "unconnected-(U19B-GPIO5-Pad165)") (class "Default")
      (node (ref "U19") (pin "165") (pinfunction "GPIO5_165") (pintype "bidirectional"))
    )
    (net (code "284") (name "unconnected-(U19B-GPIO6-Pad166)") (class "Default")
      (node (ref "U19") (pin "166") (pinfunction "GPIO6_166") (pintype "bidirectional"))
    )
    (net (code "285") (name "unconnected-(U19B-GPIO7-Pad167)") (class "Default")
      (node (ref "U19") (pin "167") (pinfunction "GPIO7_167") (pintype "bidirectional"))
    )
    (net (code "286") (name "unconnected-(U19B-GPIO8-Pad18)") (class "Default")
      (node (ref "U19") (pin "18") (pinfunction "GPIO8_18") (pintype "bidirectional"))
    )
    (net (code "287") (name "unconnected-(U19B-GPIO9-Pad19)") (class "Default")
      (node (ref "U19") (pin "19") (pinfunction "GPIO9_19") (pintype "bidirectional"))
    )
    (net (code "288") (name "unconnected-(U19B-GPIO10-Pad1)") (class "Default")
      (node (ref "U19") (pin "1") (pinfunction "GPIO10_1") (pintype "bidirectional"))
    )
    (net (code "289") (name "unconnected-(U19B-GPIO11-Pad2)") (class "Default")
      (node (ref "U19") (pin "2") (pinfunction "GPIO11_2") (pintype "bidirectional"))
    )
    (net (code "290") (name "unconnected-(U19B-GPIO12-Pad4)") (class "Default")
      (node (ref "U19") (pin "4") (pinfunction "GPIO12_4") (pintype "bidirectional"))
    )
    (net (code "291") (name "unconnected-(U19B-GPIO13-Pad5)") (class "Default")
      (node (ref "U19") (pin "5") (pinfunction "GPIO13_5") (pintype "bidirectional"))
    )
    (net (code "292") (name "unconnected-(U19B-GPIO14-Pad6)") (class "Default")
      (node (ref "U19") (pin "6") (pinfunction "GPIO14_6") (pintype "bidirectional"))
    )
    (net (code "293") (name "unconnected-(U19B-GPIO15-Pad7)") (class "Default")
      (node (ref "U19") (pin "7") (pinfunction "GPIO15_7") (pintype "bidirectional"))
    )
    (net (code "294") (name "unconnected-(U19B-GPIO16-Pad8)") (class "Default")
      (node (ref "U19") (pin "8") (pinfunction "GPIO16_8") (pintype "bidirectional"))
    )
    (net (code "295") (name "unconnected-(U19B-GPIO17-Pad9)") (class "Default")
      (node (ref "U19") (pin "9") (pinfunction "GPIO17_9") (pintype "bidirectional"))
    )
    (net (code "296") (name "unconnected-(U19B-GPIO18-Pad10)") (class "Default")
      (node (ref "U19") (pin "10") (pinfunction "GPIO18_10") (pintype "bidirectional"))
    )
    (net (code "297") (name "unconnected-(U19B-GPIO19-Pad12)") (class "Default")
      (node (ref "U19") (pin "12") (pinfunction "GPIO19_12") (pintype "bidirectional"))
    )
    (net (code "298") (name "unconnected-(U19B-GPIO20-Pad13)") (class "Default")
      (node (ref "U19") (pin "13") (pinfunction "GPIO20_13") (pintype "bidirectional"))
    )
    (net (code "299") (name "unconnected-(U19B-GPIO21-Pad14)") (class "Default")
      (node (ref "U19") (pin "14") (pinfunction "GPIO21_14") (pintype "bidirectional"))
    )
    (net (code "300") (name "unconnected-(U19B-GPIO22-Pad22)") (class "Default")
      (node (ref "U19") (pin "22") (pinfunction "GPIO22_22") (pintype "bidirectional"))
    )
    (net (code "301") (name "unconnected-(U19B-GPIO23-Pad23)") (class "Default")
      (node (ref "U19") (pin "23") (pinfunction "GPIO23_23") (pintype "bidirectional"))
    )
    (net (code "302") (name "unconnected-(U19B-GPIO24-Pad24)") (class "Default")
      (node (ref "U19") (pin "24") (pinfunction "GPIO24_24") (pintype "bidirectional"))
    )
    (net (code "303") (name "unconnected-(U19B-GPIO25-Pad25)") (class "Default")
      (node (ref "U19") (pin "25") (pinfunction "GPIO25_25") (pintype "bidirectional"))
    )
    (net (code "304") (name "unconnected-(U19B-GPIO26-Pad27)") (class "Default")
      (node (ref "U19") (pin "27") (pinfunction "GPIO26_27") (pintype "bidirectional"))
    )
    (net (code "305") (name "unconnected-(U19B-GPIO27-Pad28)") (class "Default")
      (node (ref "U19") (pin "28") (pinfunction "GPIO27_28") (pintype "bidirectional"))
    )
    (net (code "306") (name "unconnected-(U19B-GPIO28-Pad64)") (class "Default")
      (node (ref "U19") (pin "64") (pinfunction "GPIO28_64") (pintype "bidirectional"))
    )
    (net (code "307") (name "unconnected-(U19B-GPIO29-Pad65)") (class "Default")
      (node (ref "U19") (pin "65") (pinfunction "GPIO29_65") (pintype "bidirectional"))
    )
    (net (code "308") (name "unconnected-(U19B-GPIO30-Pad63)") (class "Default")
      (node (ref "U19") (pin "63") (pinfunction "GPIO30_63") (pintype "bidirectional"))
    )
    (net (code "309") (name "unconnected-(U19B-GPIO31-Pad66)") (class "Default")
      (node (ref "U19") (pin "66") (pinfunction "GPIO31_66") (pintype "bidirectional"))
    )
    (net (code "310") (name "unconnected-(U19B-GPIO32-Pad67)") (class "Default")
      (node (ref "U19") (pin "67") (pinfunction "GPIO32_67") (pintype "bidirectional"))
    )
    (net (code "311") (name "unconnected-(U19B-GPIO33-Pad69)") (class "Default")
      (node (ref "U19") (pin "69") (pinfunction "GPIO33_69") (pintype "bidirectional"))
    )
    (net (code "312") (name "unconnected-(U19B-GPIO34-Pad70)") (class "Default")
      (node (ref "U19") (pin "70") (pinfunction "GPIO34_70") (pintype "bidirectional"))
    )
    (net (code "313") (name "unconnected-(U19B-GPIO35-Pad71)") (class "Default")
      (node (ref "U19") (pin "71") (pinfunction "GPIO35_71") (pintype "bidirectional"))
    )
    (net (code "314") (name "unconnected-(U19B-GPIO36-Pad83)") (class "Default")
      (node (ref "U19") (pin "83") (pinfunction "GPIO36_83") (pintype "bidirectional"))
    )
    (net (code "315") (name "unconnected-(U19B-GPIO37-Pad84)") (class "Default")
      (node (ref "U19") (pin "84") (pinfunction "GPIO37_84") (pintype "bidirectional"))
    )
    (net (code "316") (name "unconnected-(U19B-GPIO38-Pad85)") (class "Default")
      (node (ref "U19") (pin "85") (pinfunction "GPIO38_85") (pintype "bidirectional"))
    )
    (net (code "317") (name "unconnected-(U19B-GPIO39-Pad86)") (class "Default")
      (node (ref "U19") (pin "86") (pinfunction "GPIO39_86") (pintype "bidirectional"))
    )
    (net (code "318") (name "unconnected-(U19B-GPIO40-Pad87)") (class "Default")
      (node (ref "U19") (pin "87") (pinfunction "GPIO40_87") (pintype "bidirectional"))
    )
    (net (code "319") (name "unconnected-(U19B-GPIO41-Pad89)") (class "Default")
      (node (ref "U19") (pin "89") (pinfunction "GPIO41_89") (pintype "bidirectional"))
    )
    (net (code "320") (name "unconnected-(U19B-GPIO42-Pad130)") (class "Default")
      (node (ref "U19") (pin "130") (pinfunction "GPIO42_130") (pintype "bidirectional"))
    )
    (net (code "321") (name "unconnected-(U19B-GPIO43-Pad131)") (class "Default")
      (node (ref "U19") (pin "131") (pinfunction "GPIO43_131") (pintype "bidirectional"))
    )
    (net (code "322") (name "unconnected-(U19B-GPIO44-Pad113)") (class "Default")
      (node (ref "U19") (pin "113") (pinfunction "GPIO44_113") (pintype "bidirectional"))
    )
    (net (code "323") (name "unconnected-(U19B-GPIO45-Pad115)") (class "Default")
      (node (ref "U19") (pin "115") (pinfunction "GPIO45_115") (pintype "bidirectional"))
    )
    (net (code "324") (name "unconnected-(U19B-GPIO46-Pad128)") (class "Default")
      (node (ref "U19") (pin "128") (pinfunction "GPIO46_128") (pintype "bidirectional"))
    )
    (net (code "325") (name "unconnected-(U19B-GPIO47-Pad129)") (class "Default")
      (node (ref "U19") (pin "129") (pinfunction "GPIO47_129") (pintype "bidirectional"))
    )
    (net (code "326") (name "unconnected-(U19B-GPIO48-Pad90)") (class "Default")
      (node (ref "U19") (pin "90") (pinfunction "GPIO48_90") (pintype "bidirectional"))
    )
    (net (code "327") (name "unconnected-(U19B-GPIO49-Pad93)") (class "Default")
      (node (ref "U19") (pin "93") (pinfunction "GPIO49_93") (pintype "bidirectional"))
    )
    (net (code "328") (name "unconnected-(U19C-GPIO50-Pad94)") (class "Default")
      (node (ref "U19") (pin "94") (pinfunction "GPIO50_94") (pintype "bidirectional"))
    )
    (net (code "329") (name "unconnected-(U19C-GPIO51-Pad95)") (class "Default")
      (node (ref "U19") (pin "95") (pinfunction "GPIO51_95") (pintype "bidirectional"))
    )
    (net (code "330") (name "unconnected-(U19C-GPIO52-Pad96)") (class "Default")
      (node (ref "U19") (pin "96") (pinfunction "GPIO52_96") (pintype "bidirectional"))
    )
    (net (code "331") (name "unconnected-(U19C-GPIO53-Pad97)") (class "Default")
      (node (ref "U19") (pin "97") (pinfunction "GPIO53_97") (pintype "bidirectional"))
    )
    (net (code "332") (name "unconnected-(U19C-GPIO54-Pad98)") (class "Default")
      (node (ref "U19") (pin "98") (pinfunction "GPIO54_98") (pintype "bidirectional"))
    )
    (net (code "333") (name "unconnected-(U19C-GPIO55-Pad100)") (class "Default")
      (node (ref "U19") (pin "100") (pinfunction "GPIO55_100") (pintype "bidirectional"))
    )
    (net (code "334") (name "unconnected-(U19C-GPIO56-Pad101)") (class "Default")
      (node (ref "U19") (pin "101") (pinfunction "GPIO56_101") (pintype "bidirectional"))
    )
    (net (code "335") (name "unconnected-(U19C-GPIO57-Pad102)") (class "Default")
      (node (ref "U19") (pin "102") (pinfunction "GPIO57_102") (pintype "bidirectional"))
    )
    (net (code "336") (name "unconnected-(U19C-GPIO59-Pad104)") (class "Default")
      (node (ref "U19") (pin "104") (pinfunction "GPIO59_104") (pintype "bidirectional"))
    )
    (net (code "337") (name "unconnected-(U19C-GPIO61-Pad107)") (class "Default")
      (node (ref "U19") (pin "107") (pinfunction "GPIO61_107") (pintype "bidirectional"))
    )
    (net (code "338") (name "unconnected-(U19C-GPIO62-Pad108)") (class "Default")
      (node (ref "U19") (pin "108") (pinfunction "GPIO62_108") (pintype "bidirectional"))
    )
    (net (code "339") (name "unconnected-(U19C-GPIO63-Pad109)") (class "Default")
      (node (ref "U19") (pin "109") (pinfunction "GPIO63_109") (pintype "bidirectional"))
    )
    (net (code "340") (name "unconnected-(U19C-GPIO64-Pad110)") (class "Default")
      (node (ref "U19") (pin "110") (pinfunction "GPIO64_110") (pintype "bidirectional"))
    )
    (net (code "341") (name "unconnected-(U19C-GPIO65-Pad111)") (class "Default")
      (node (ref "U19") (pin "111") (pinfunction "GPIO65_111") (pintype "bidirectional"))
    )
    (net (code "342") (name "unconnected-(U19C-GPIO66-Pad112)") (class "Default")
      (node (ref "U19") (pin "112") (pinfunction "GPIO66_112") (pintype "bidirectional"))
    )
    (net (code "343") (name "unconnected-(U19C-GPIO67-Pad132)") (class "Default")
      (node (ref "U19") (pin "132") (pinfunction "GPIO67_132") (pintype "bidirectional"))
    )
    (net (code "344") (name "unconnected-(U19C-GPIO99-Pad17)") (class "Default")
      (node (ref "U19") (pin "17") (pinfunction "GPIO99_17") (pintype "bidirectional"))
    )
    (net (code "345") (name "unconnected-(U19C-GPIO133-Pad118)") (class "Default")
      (node (ref "U19") (pin "118") (pinfunction "GPIO133_118") (pintype "bidirectional"))
    )
    (net (code "346") (name "unconnected-(U19D-ERRORSTS-Pad92)") (class "Default")
      (node (ref "U19") (pin "92") (pinfunction "ERRORSTS_92") (pintype "output"))
    )
    (net (code "347") (name "unconnected-(U19D-FLT1-Pad73)") (class "Default")
      (node (ref "U19") (pin "73") (pinfunction "FLT1_73") (pintype "bidirectional"))
    )
    (net (code "348") (name "unconnected-(U19D-FLT2-Pad74)") (class "Default")
      (node (ref "U19") (pin "74") (pinfunction "FLT2_74") (pintype "bidirectional"))
    )
  )
)
